# 1-Schematic_miniCoffee.net
KiCad netlist of a schematic drawn in EasyEDA
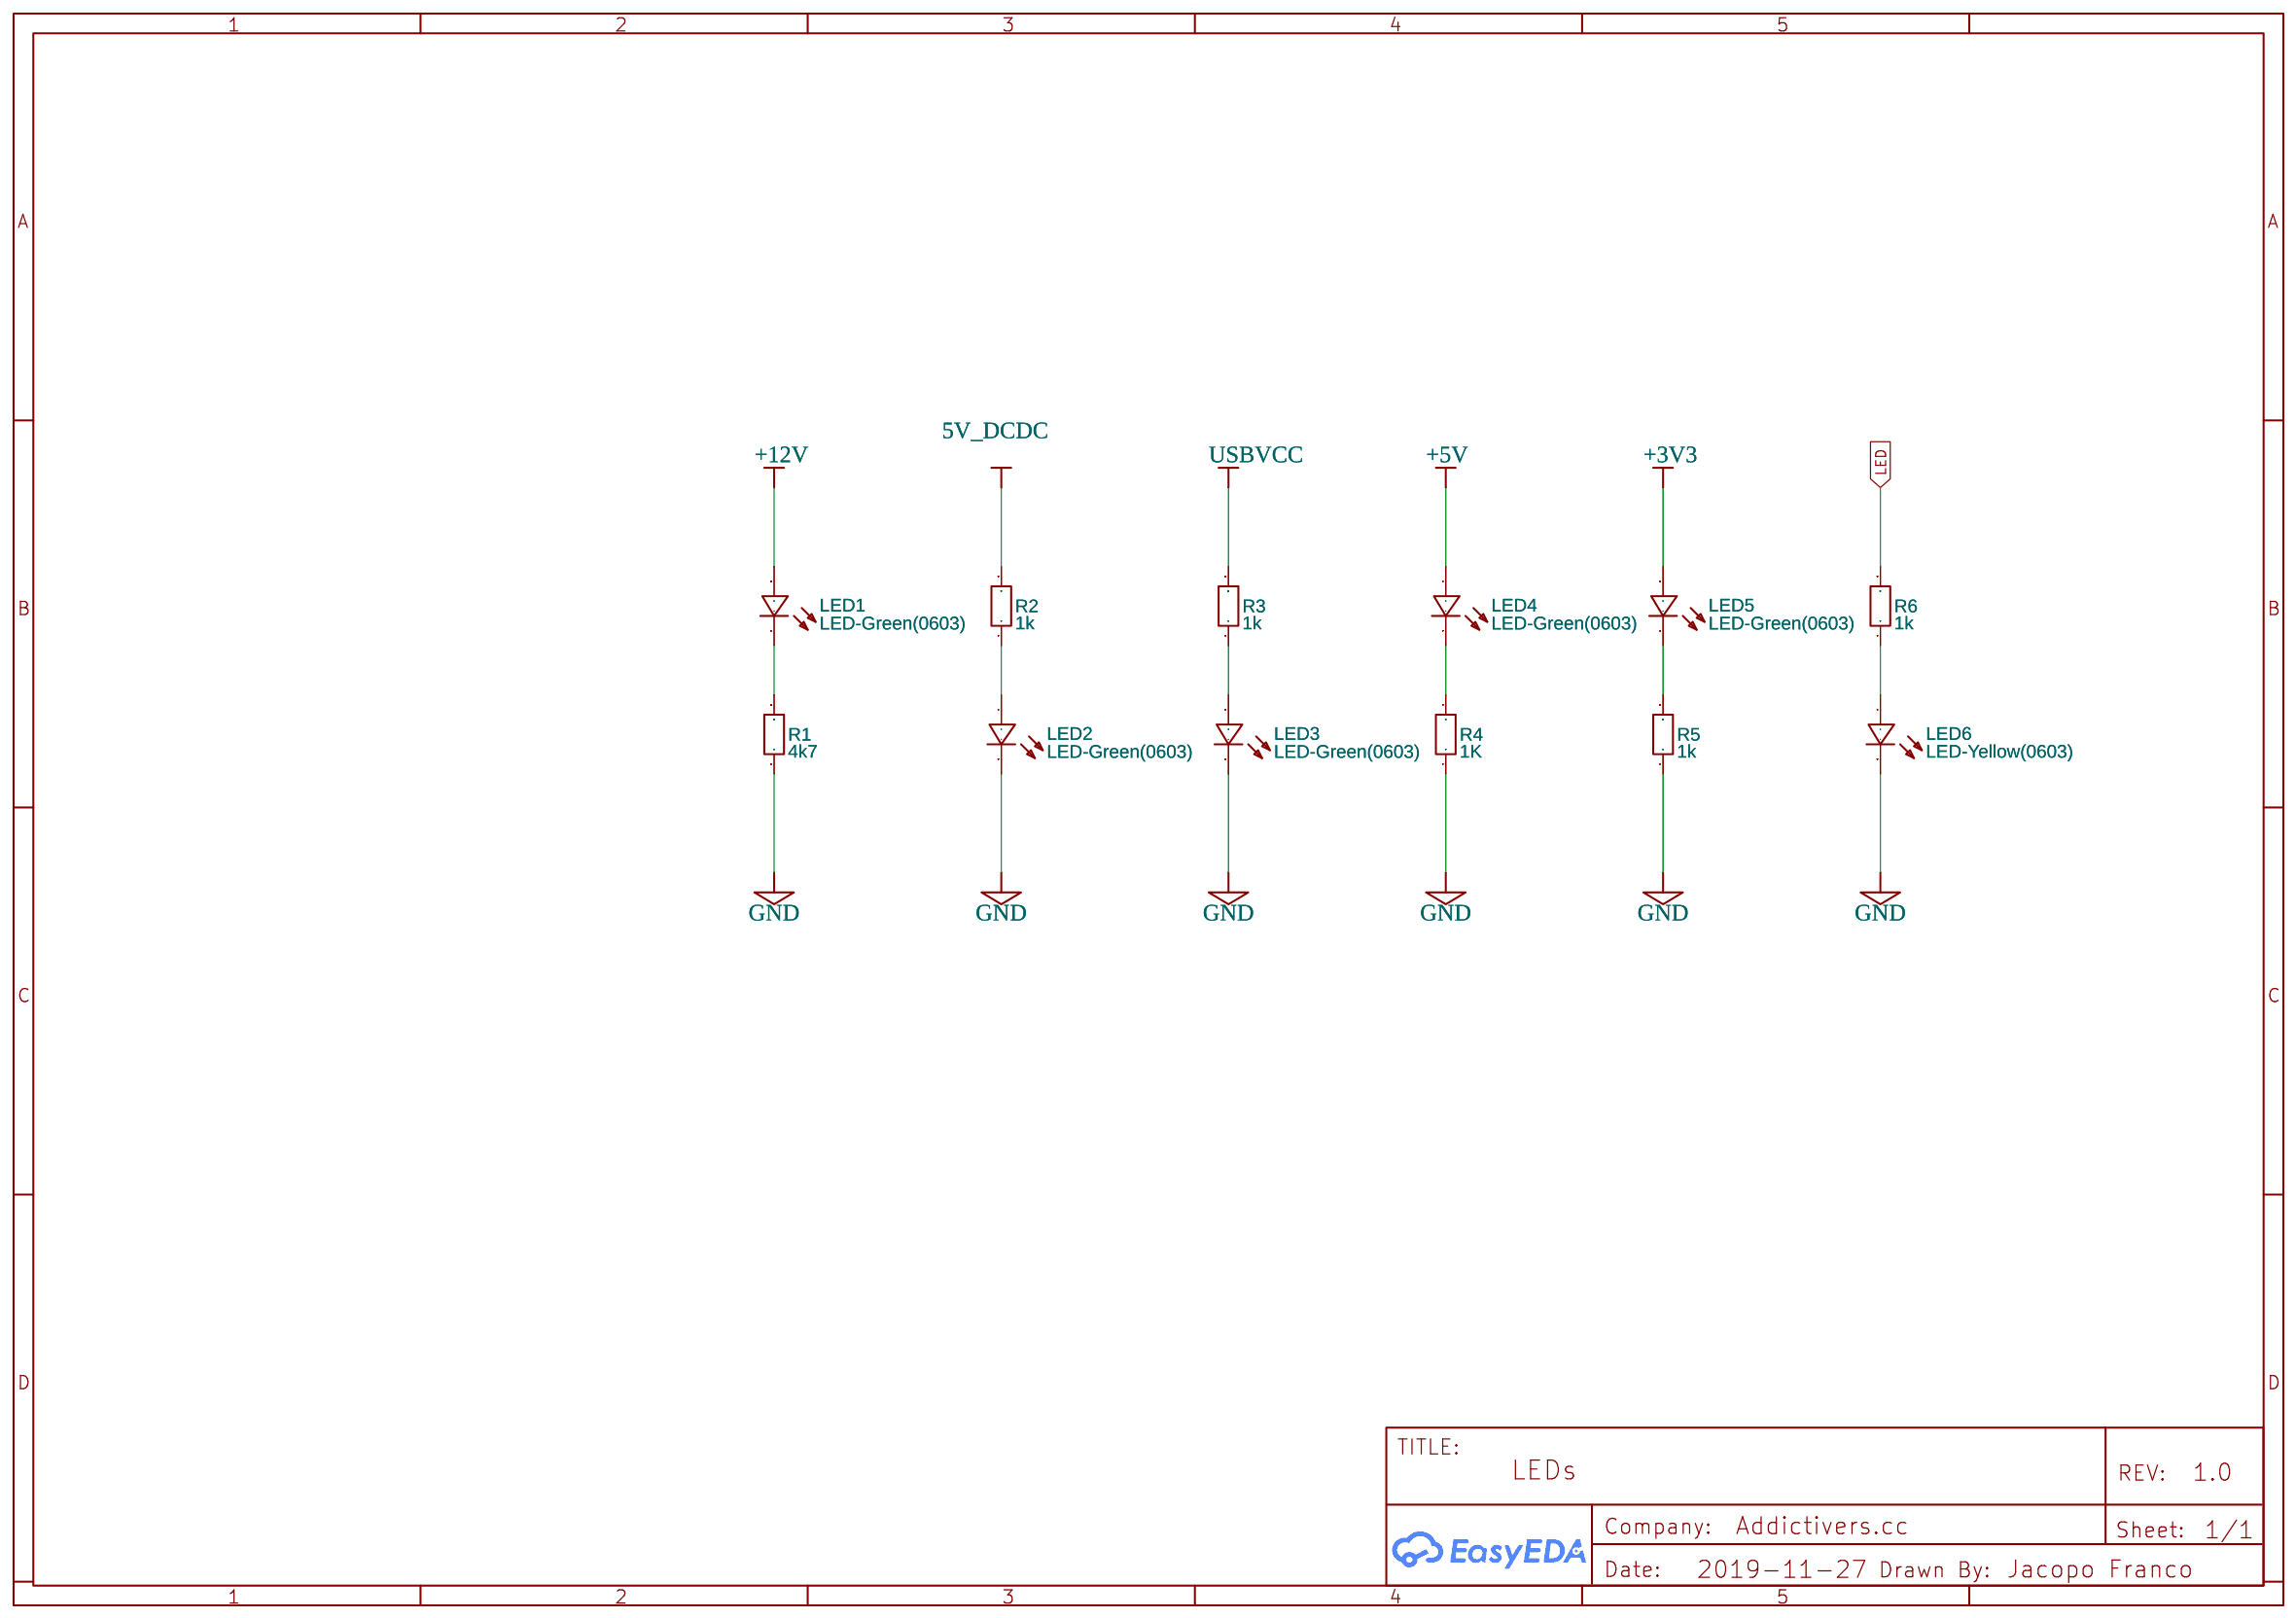
[diagram p0: LEDs]
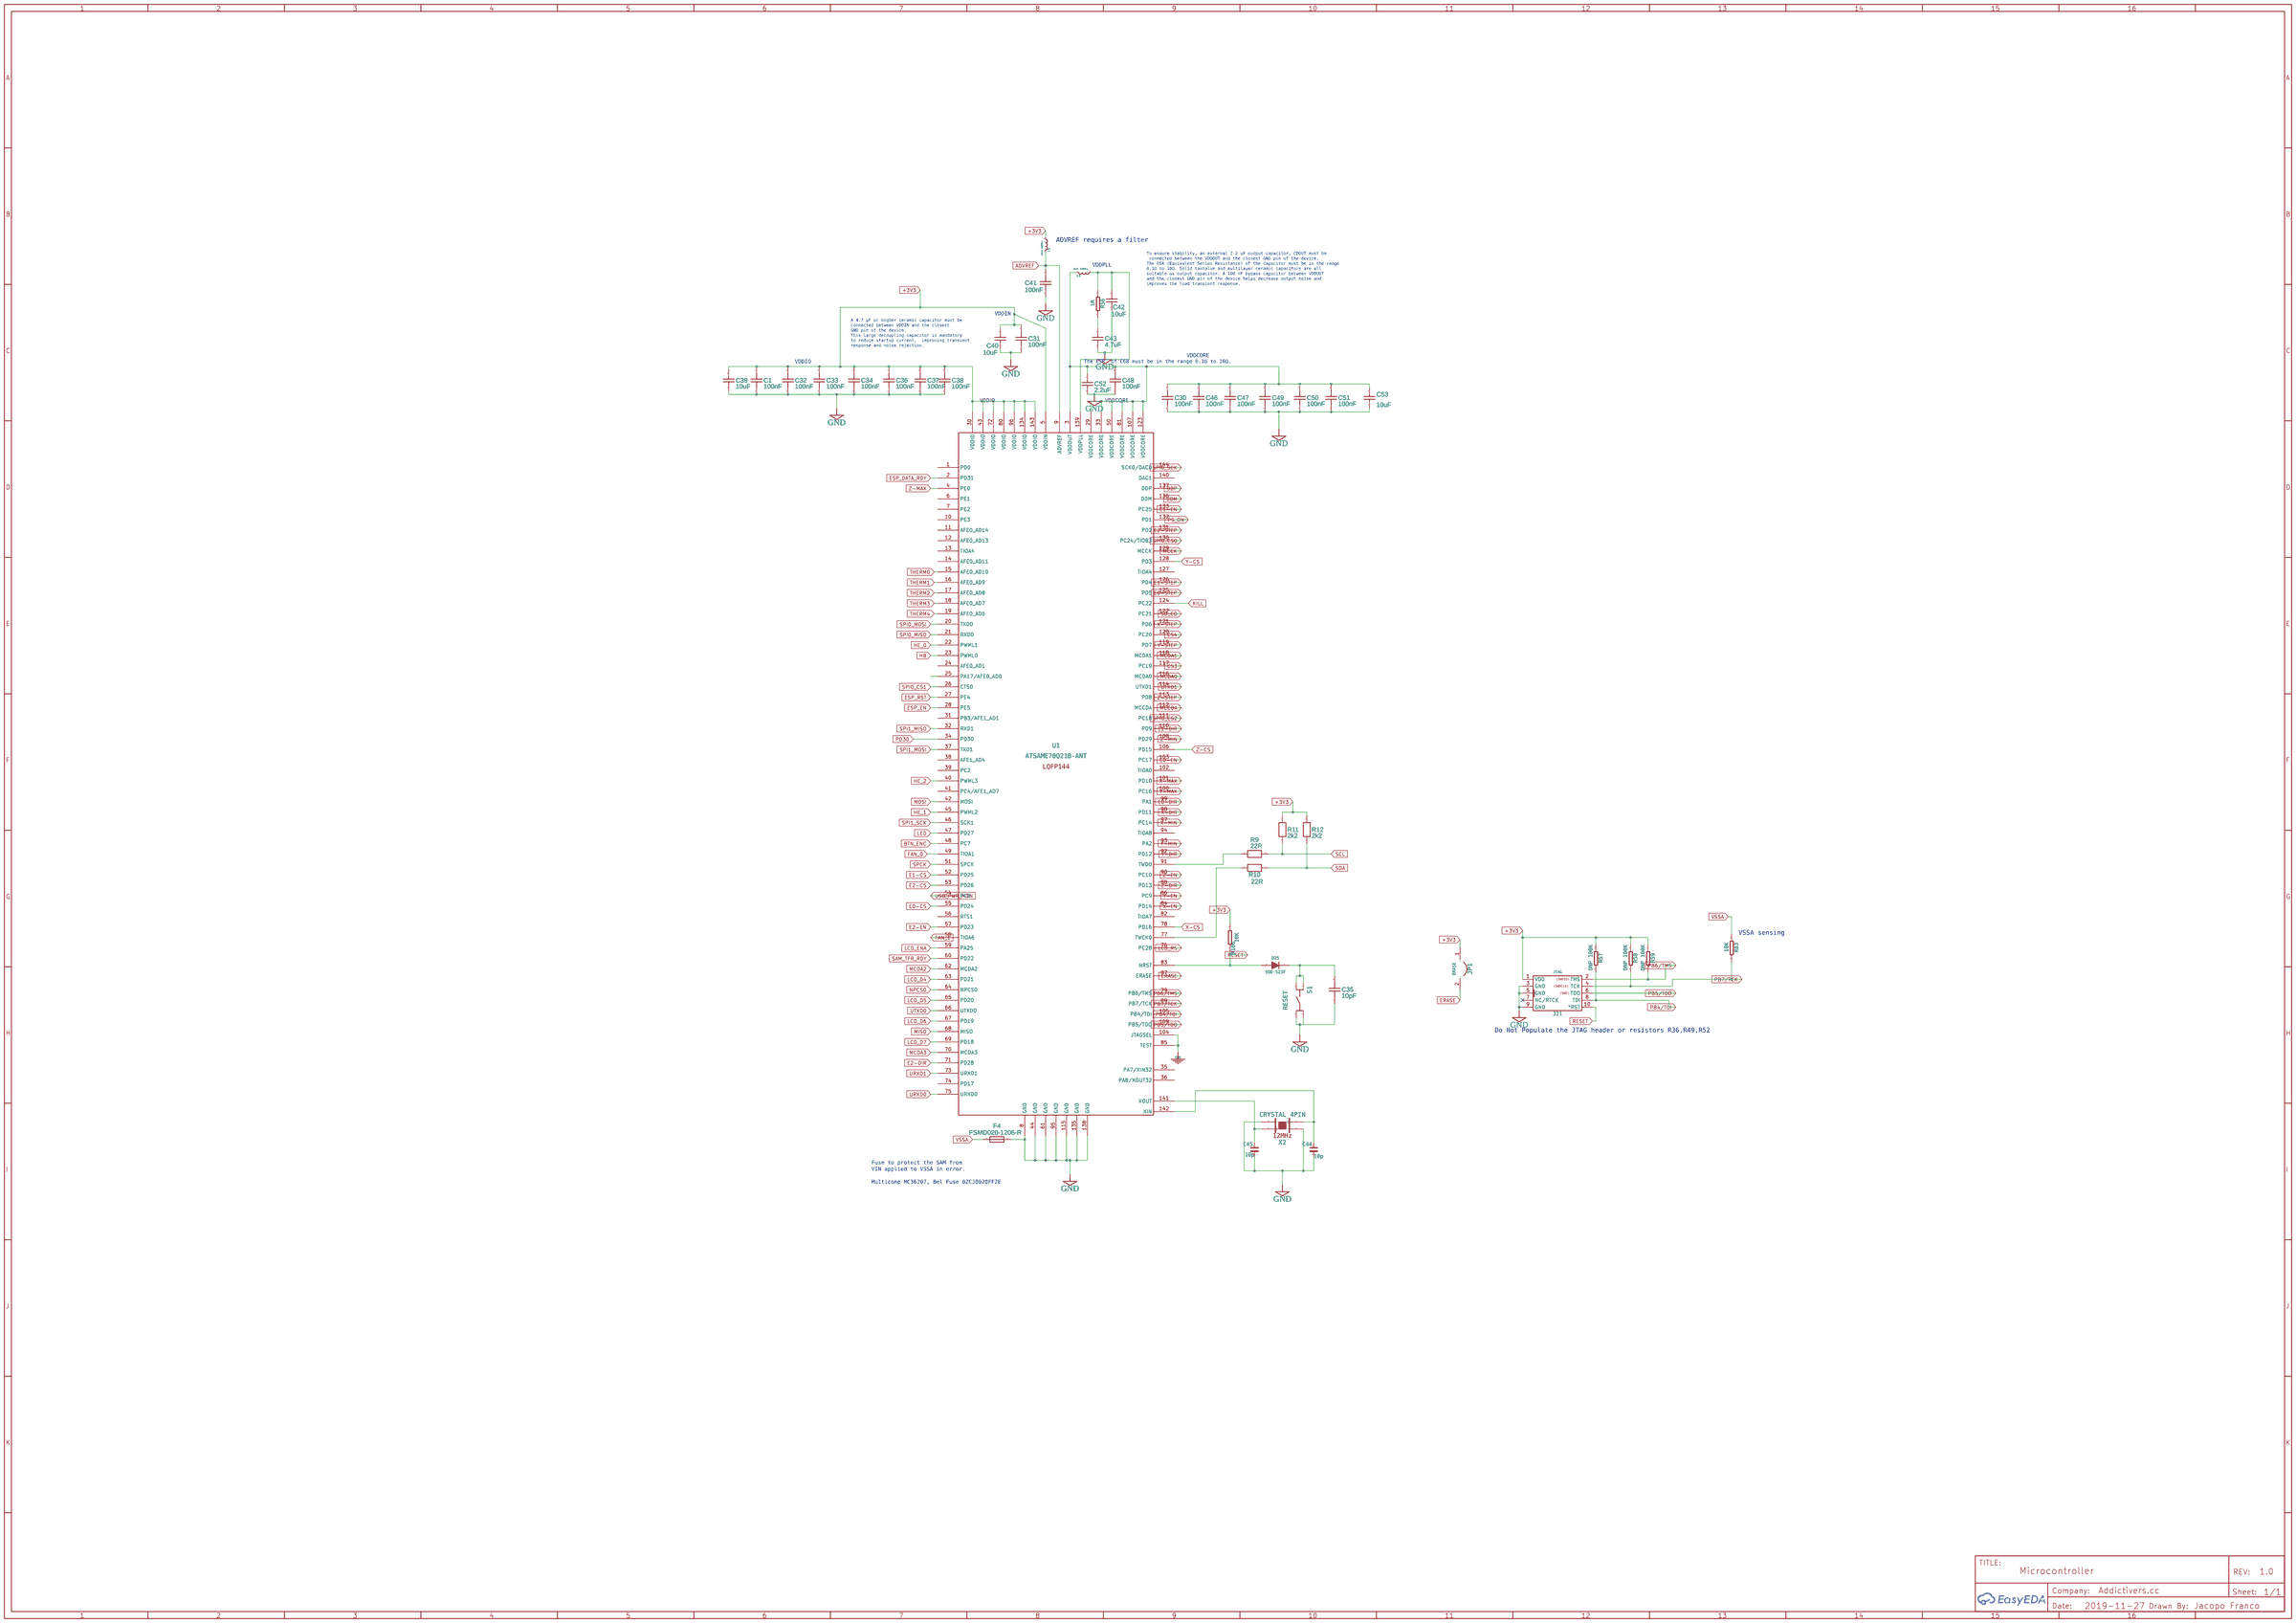
[diagram p1: Microcontroller]
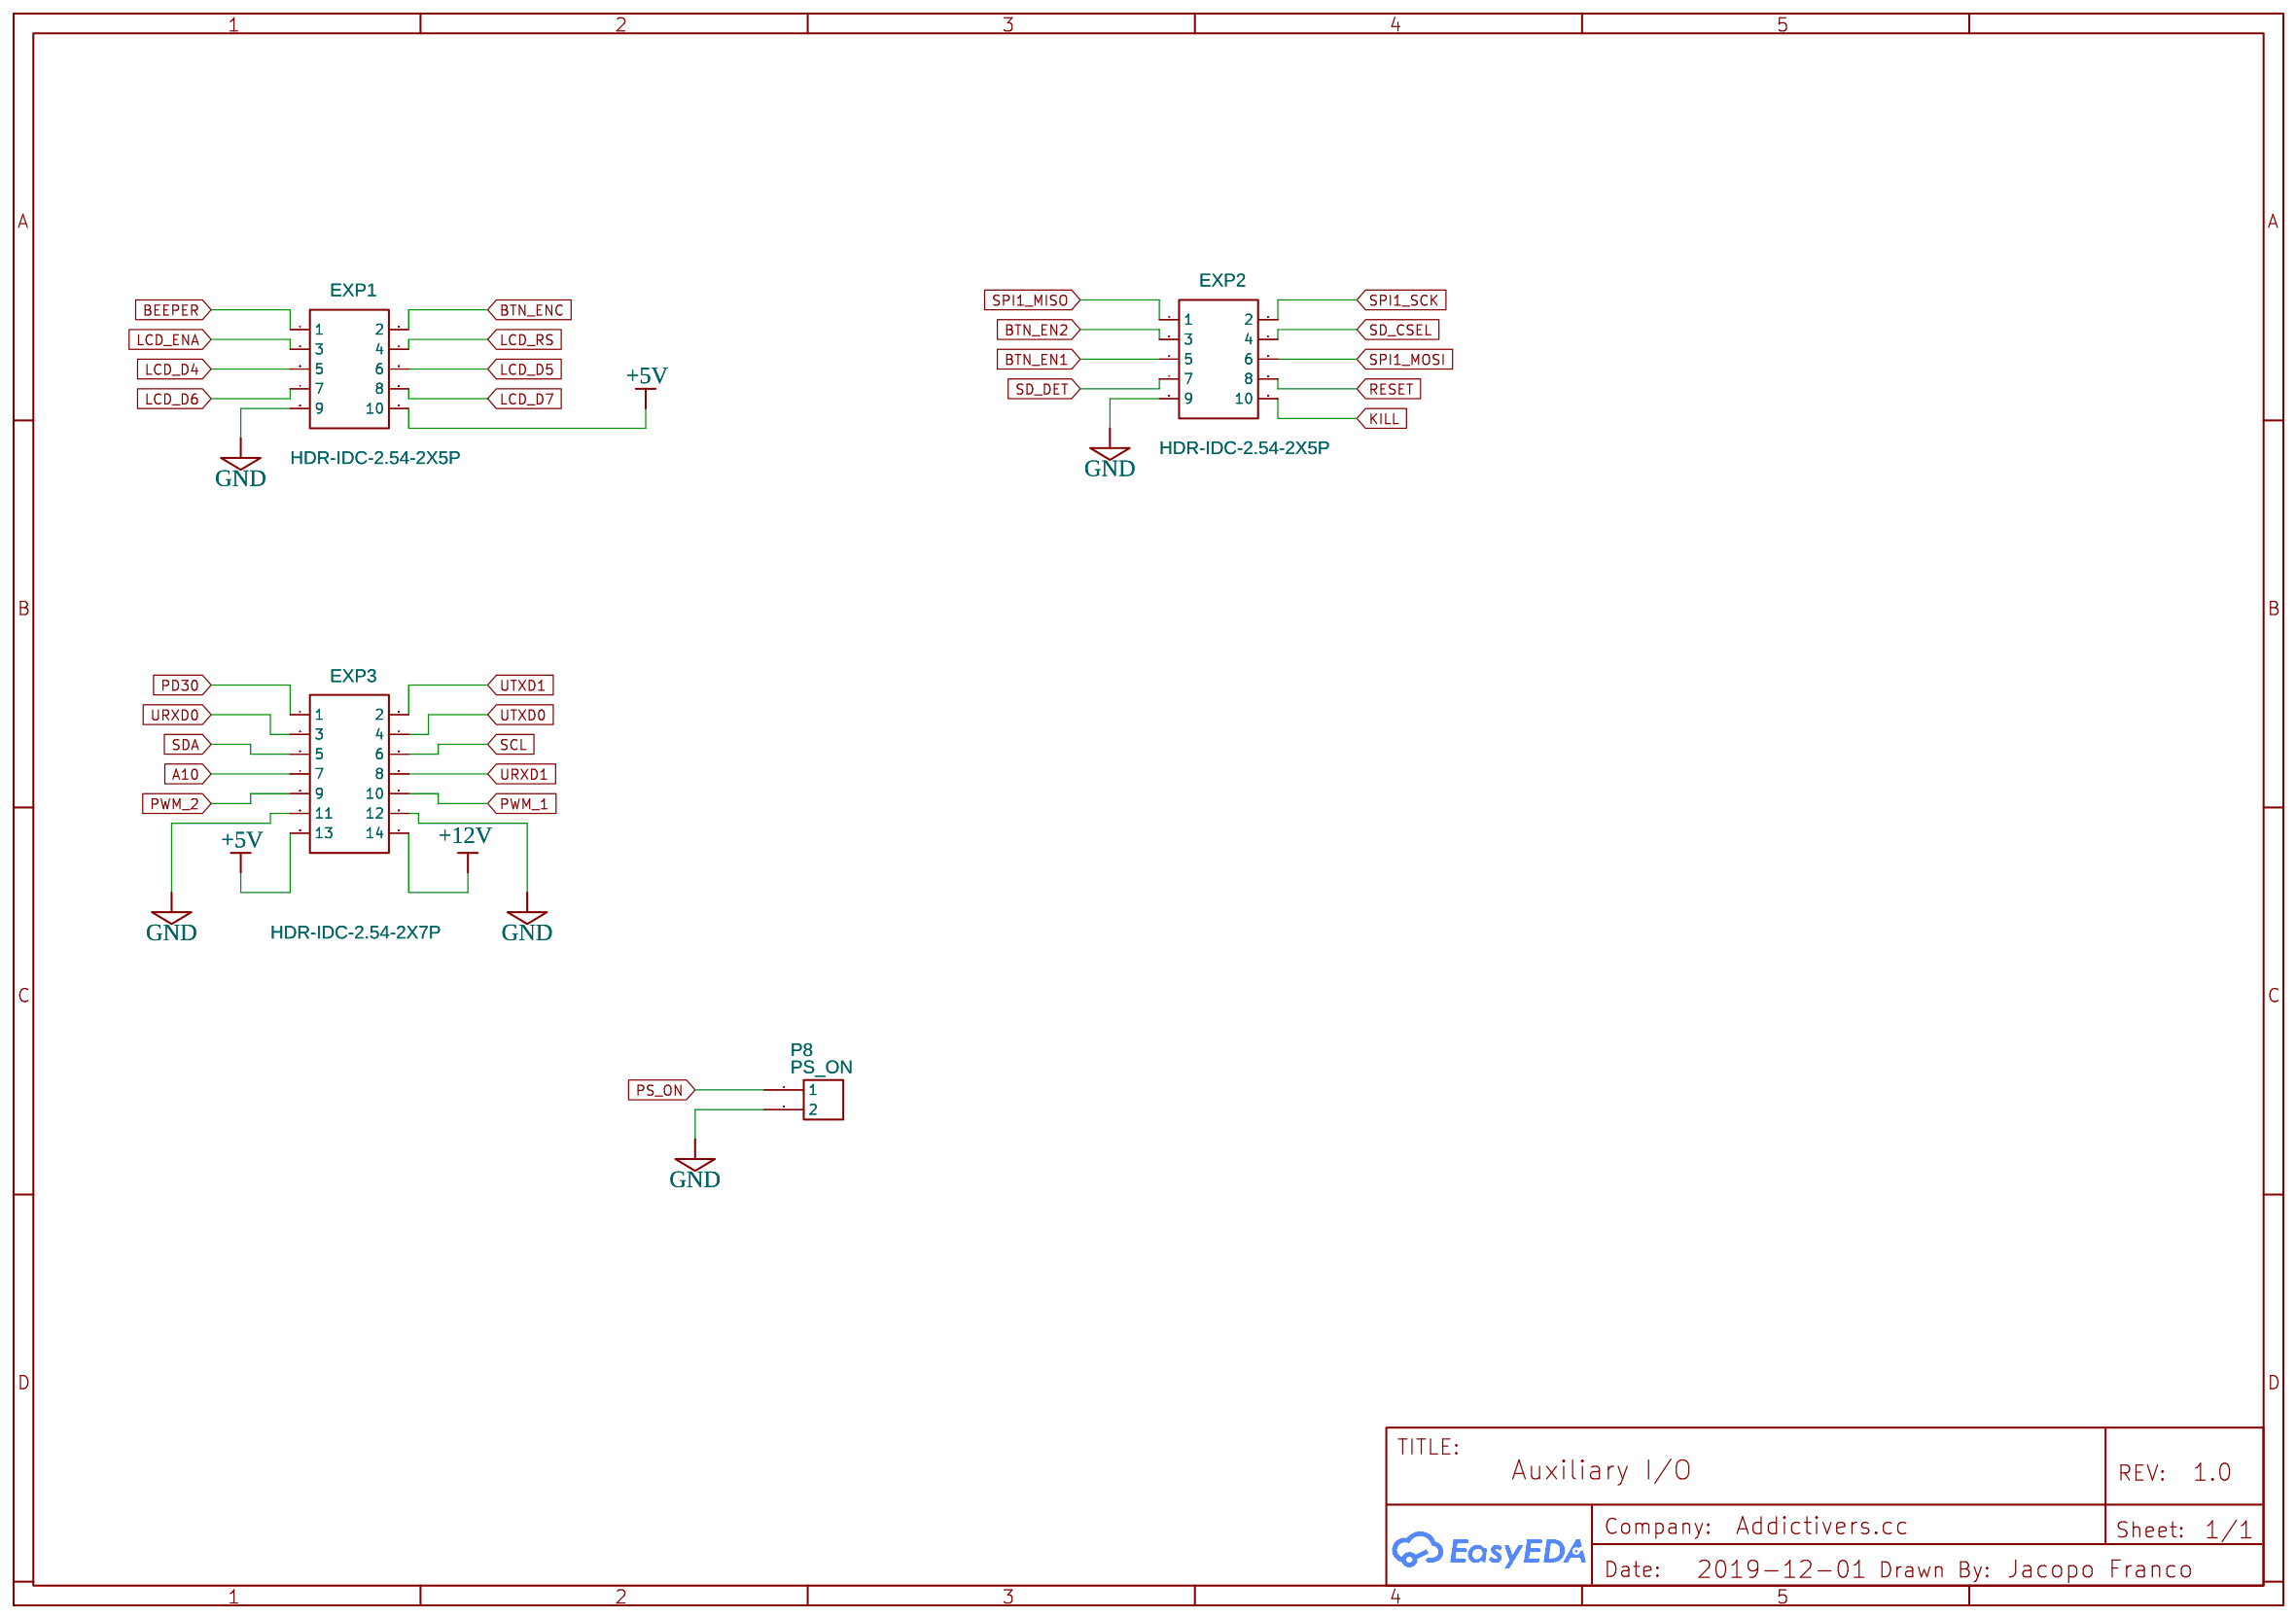
[diagram p2: Auxiliary IO]
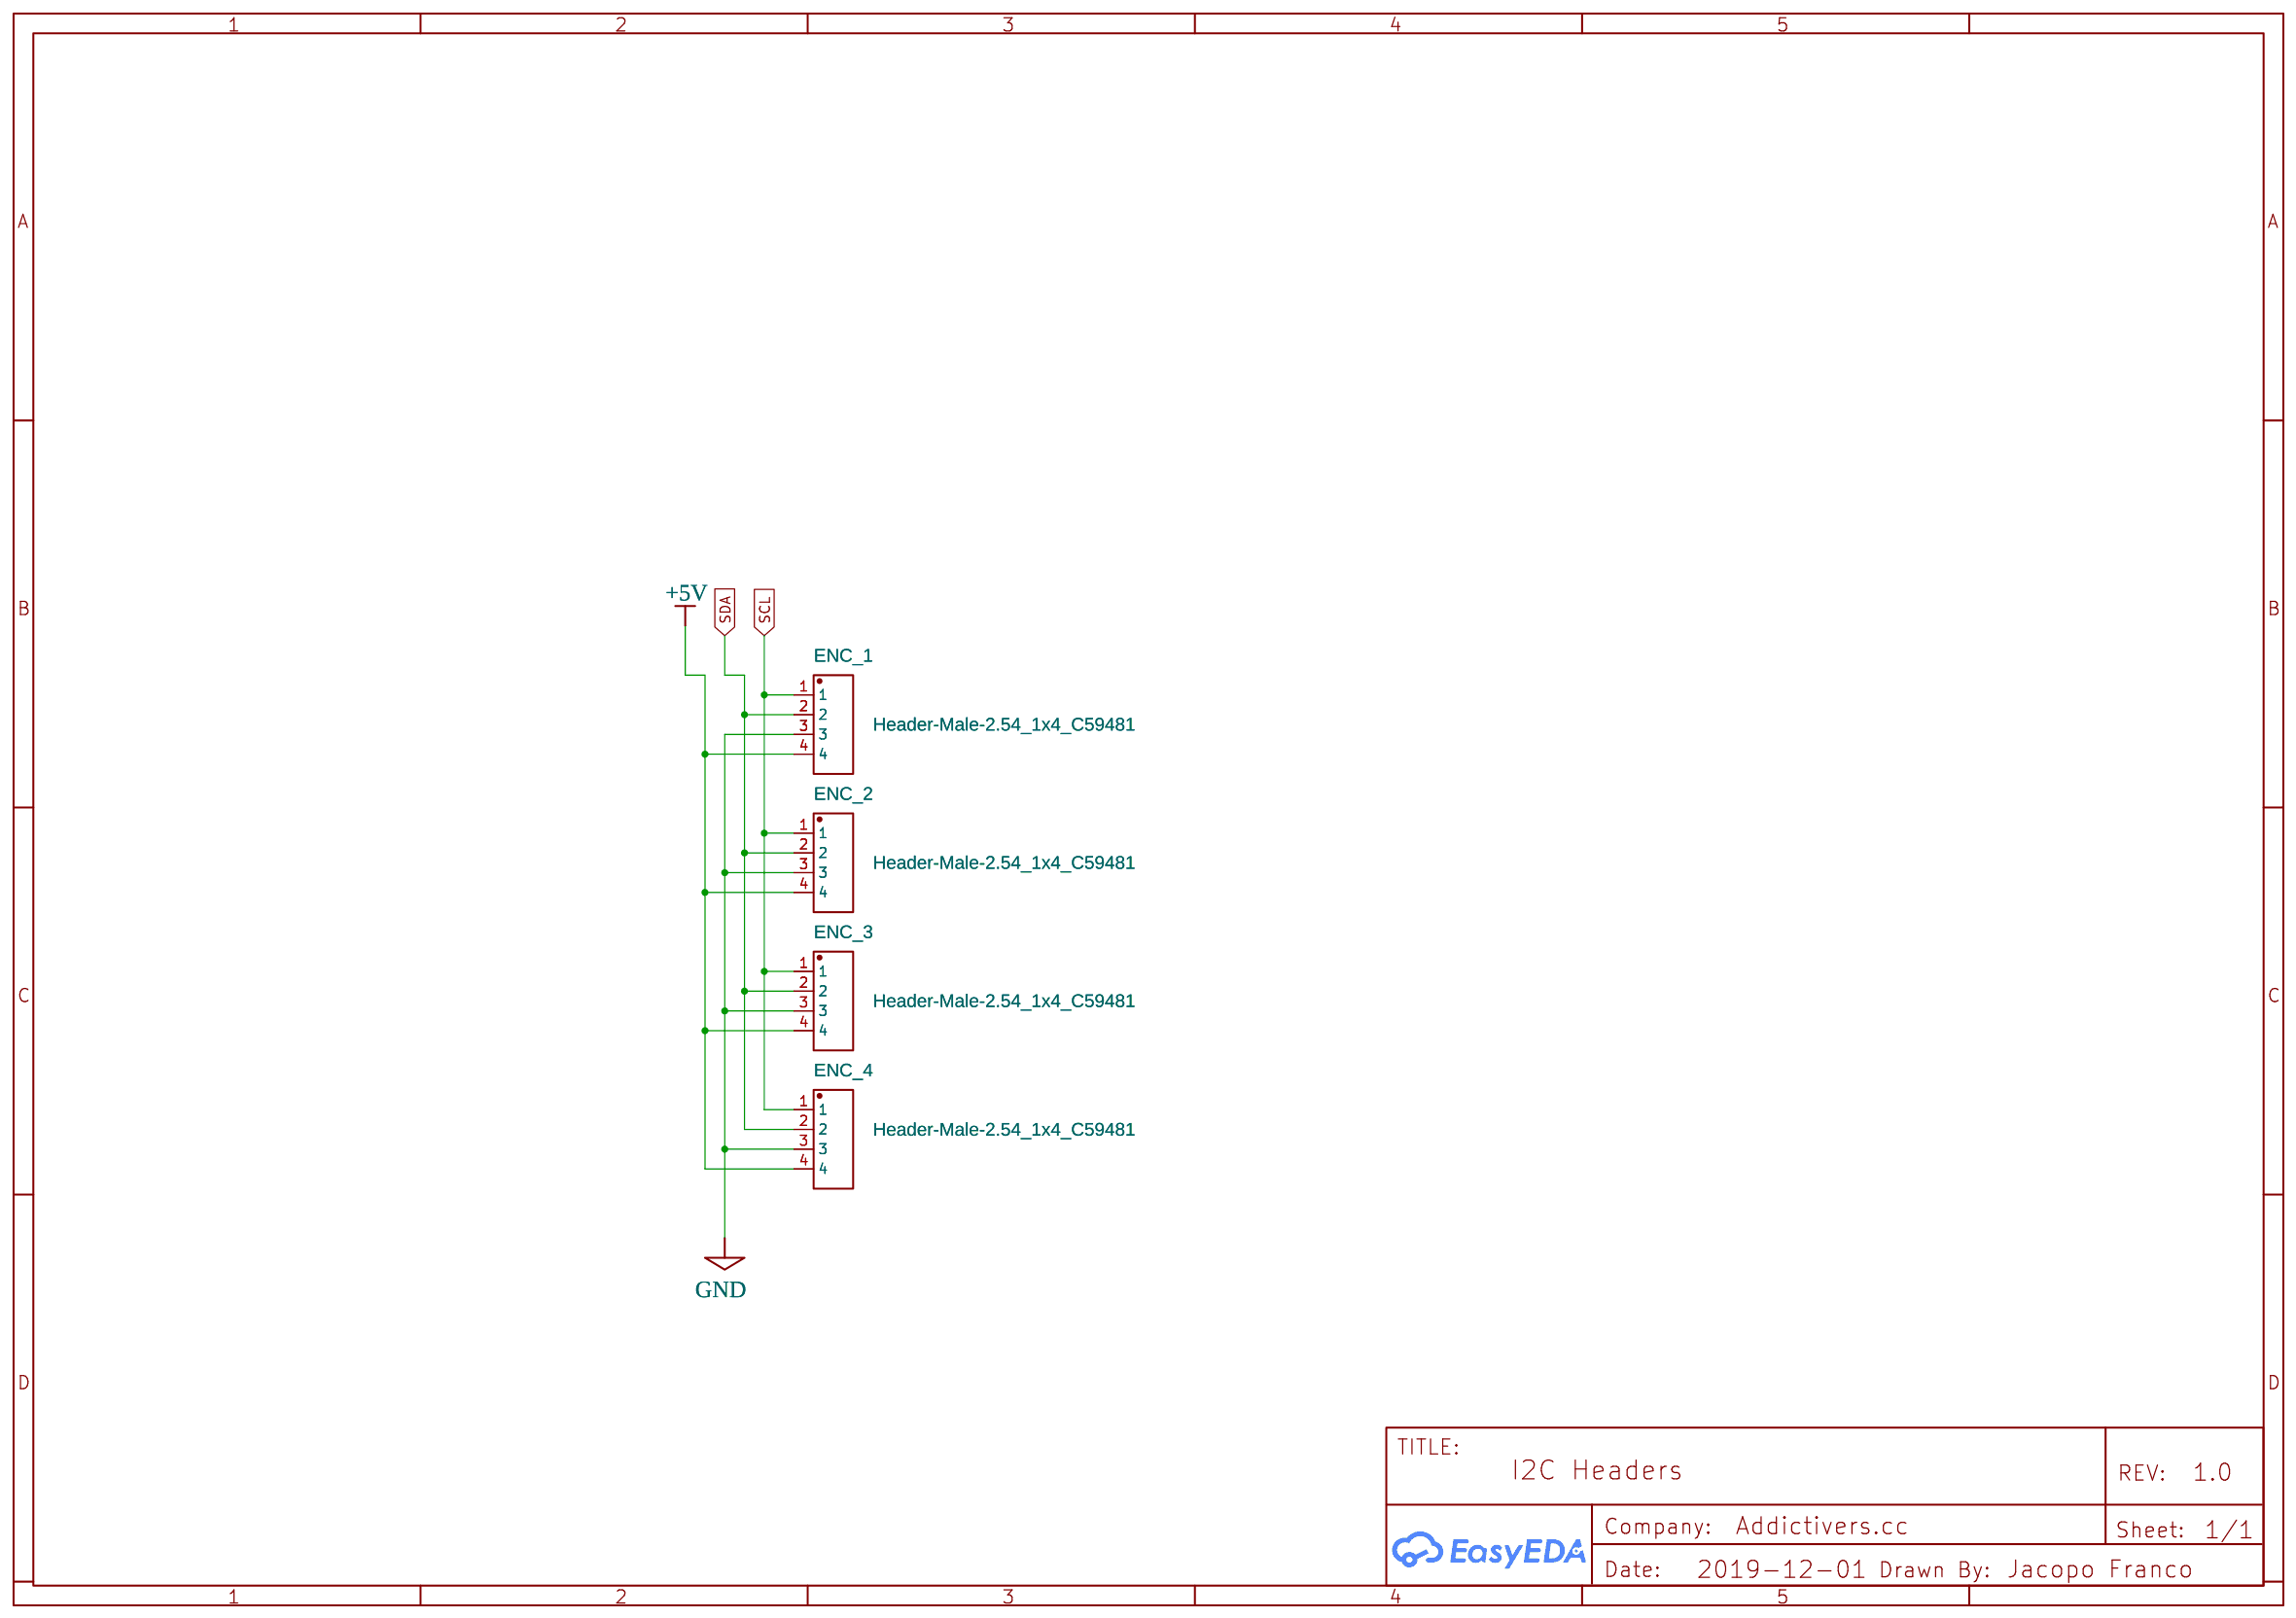
[diagram p3: I2C Headers]
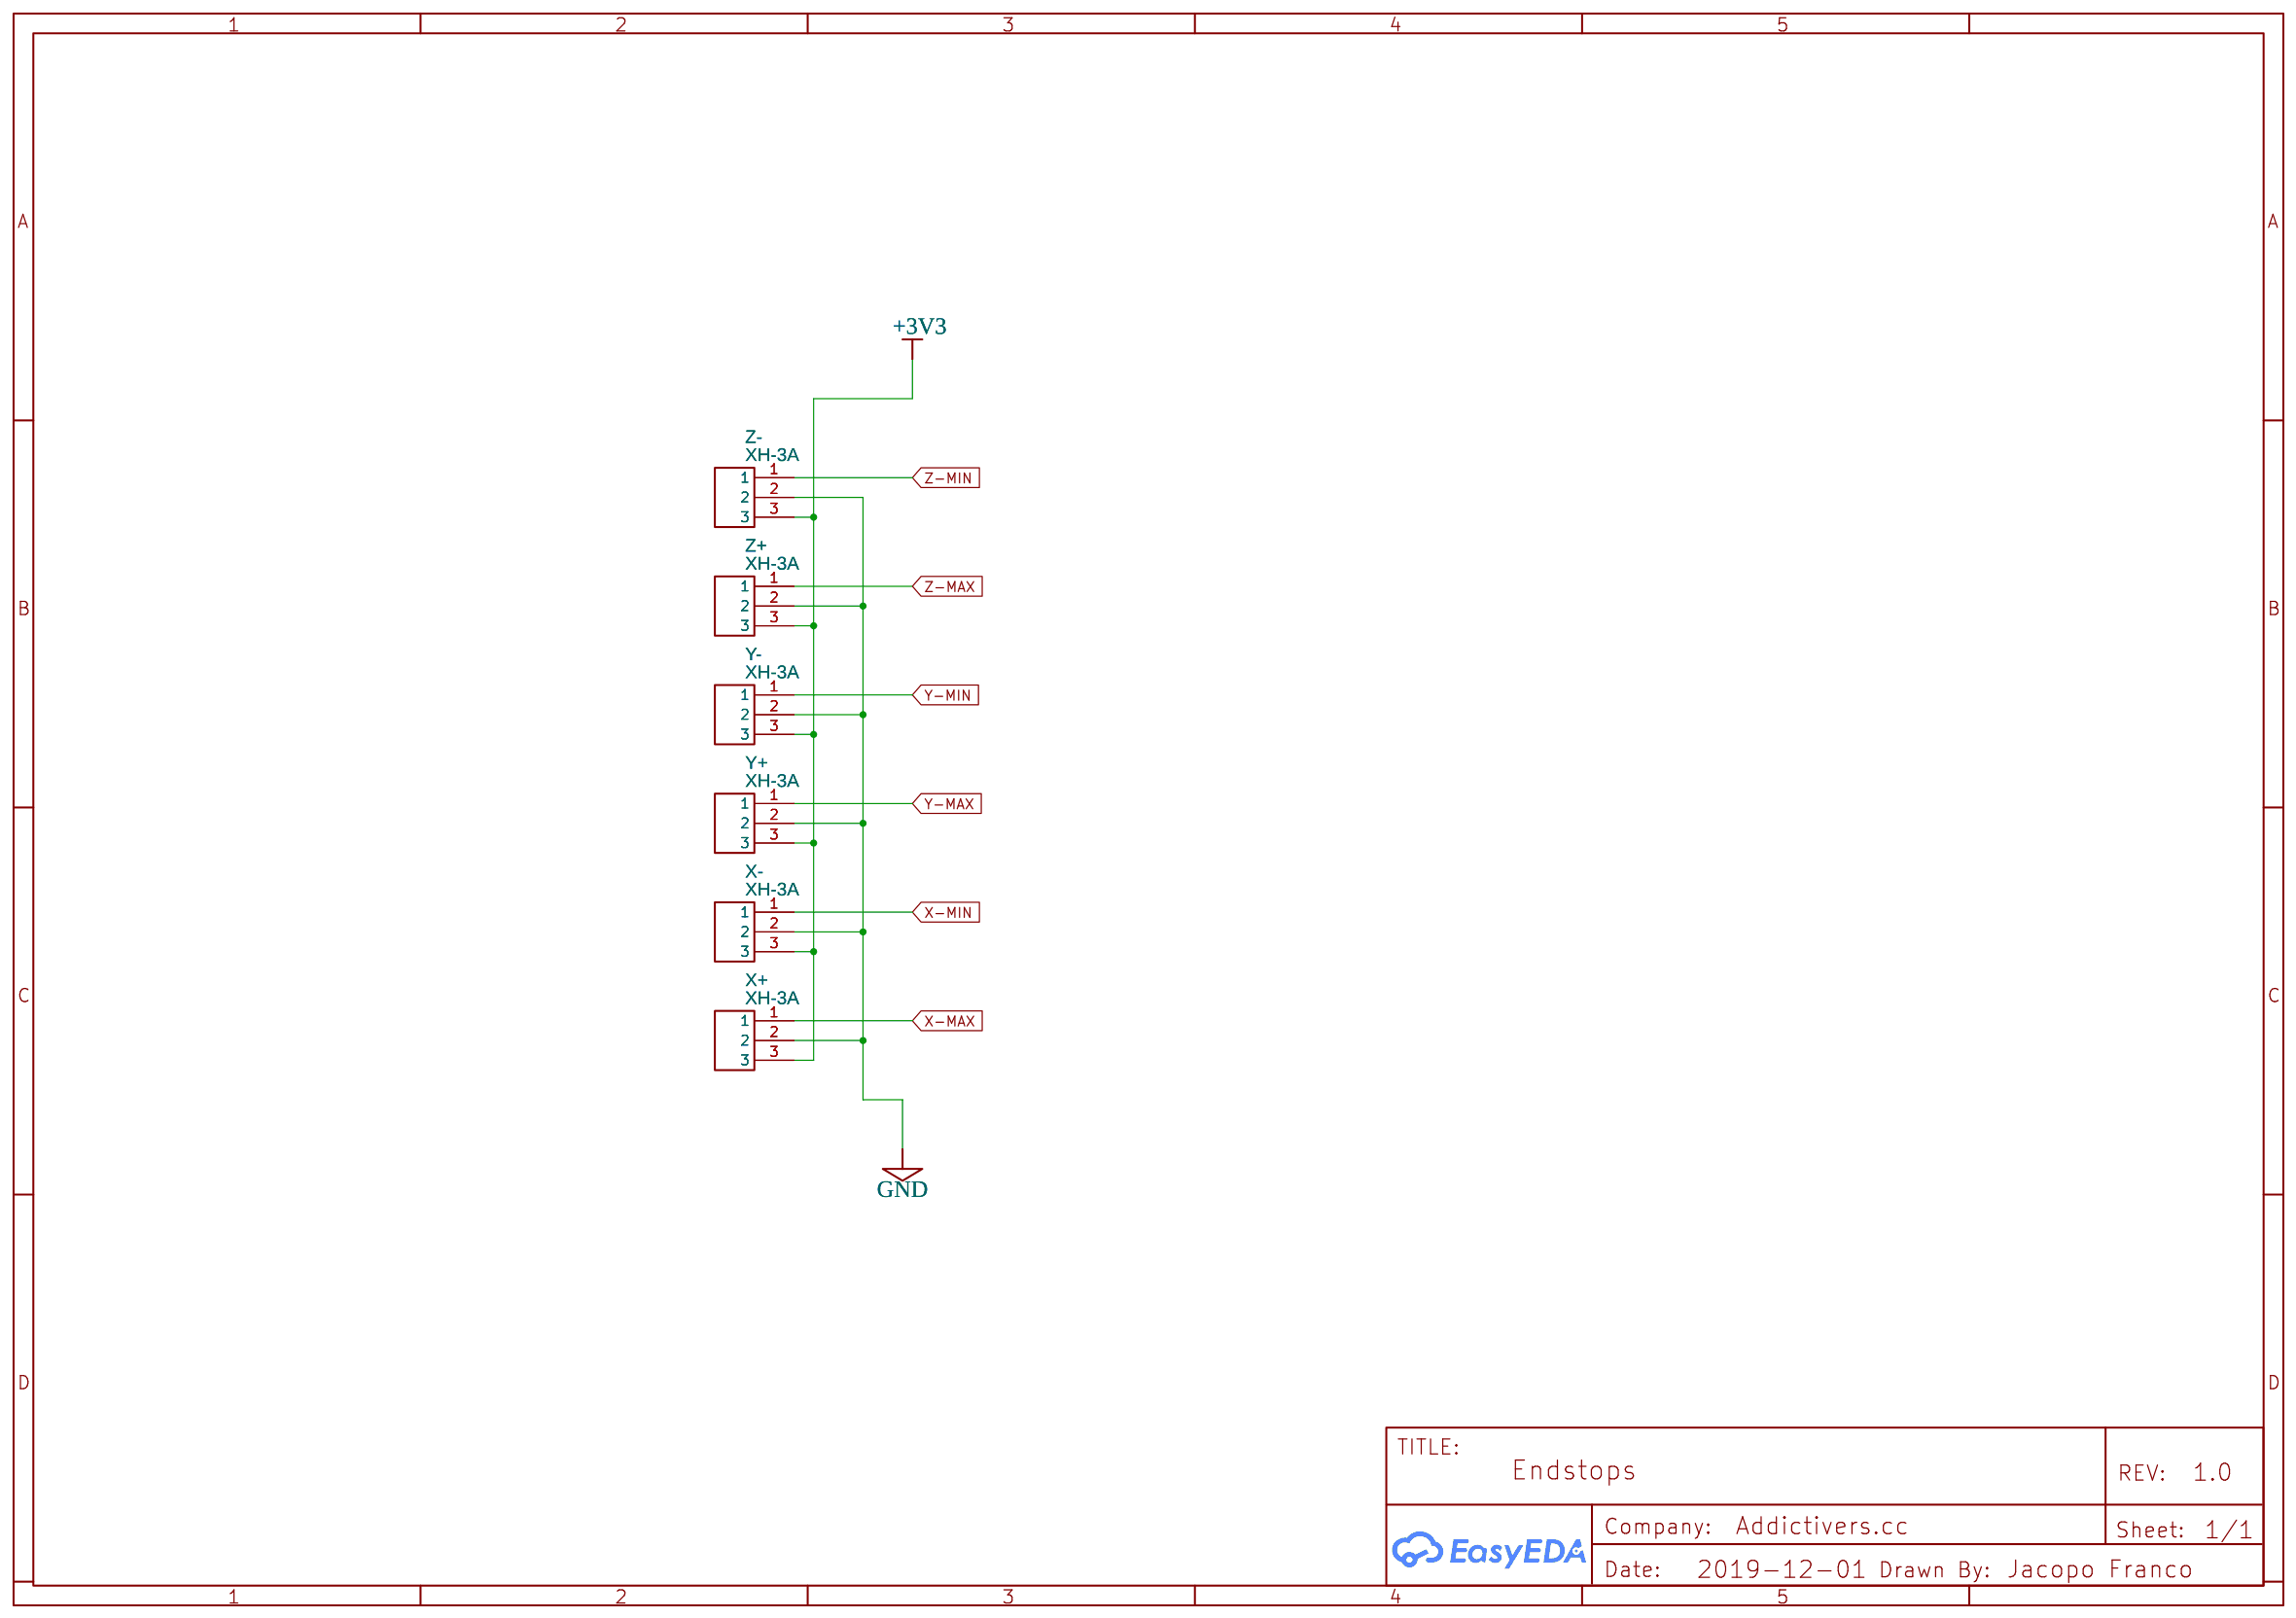
[diagram p4: Endstops]
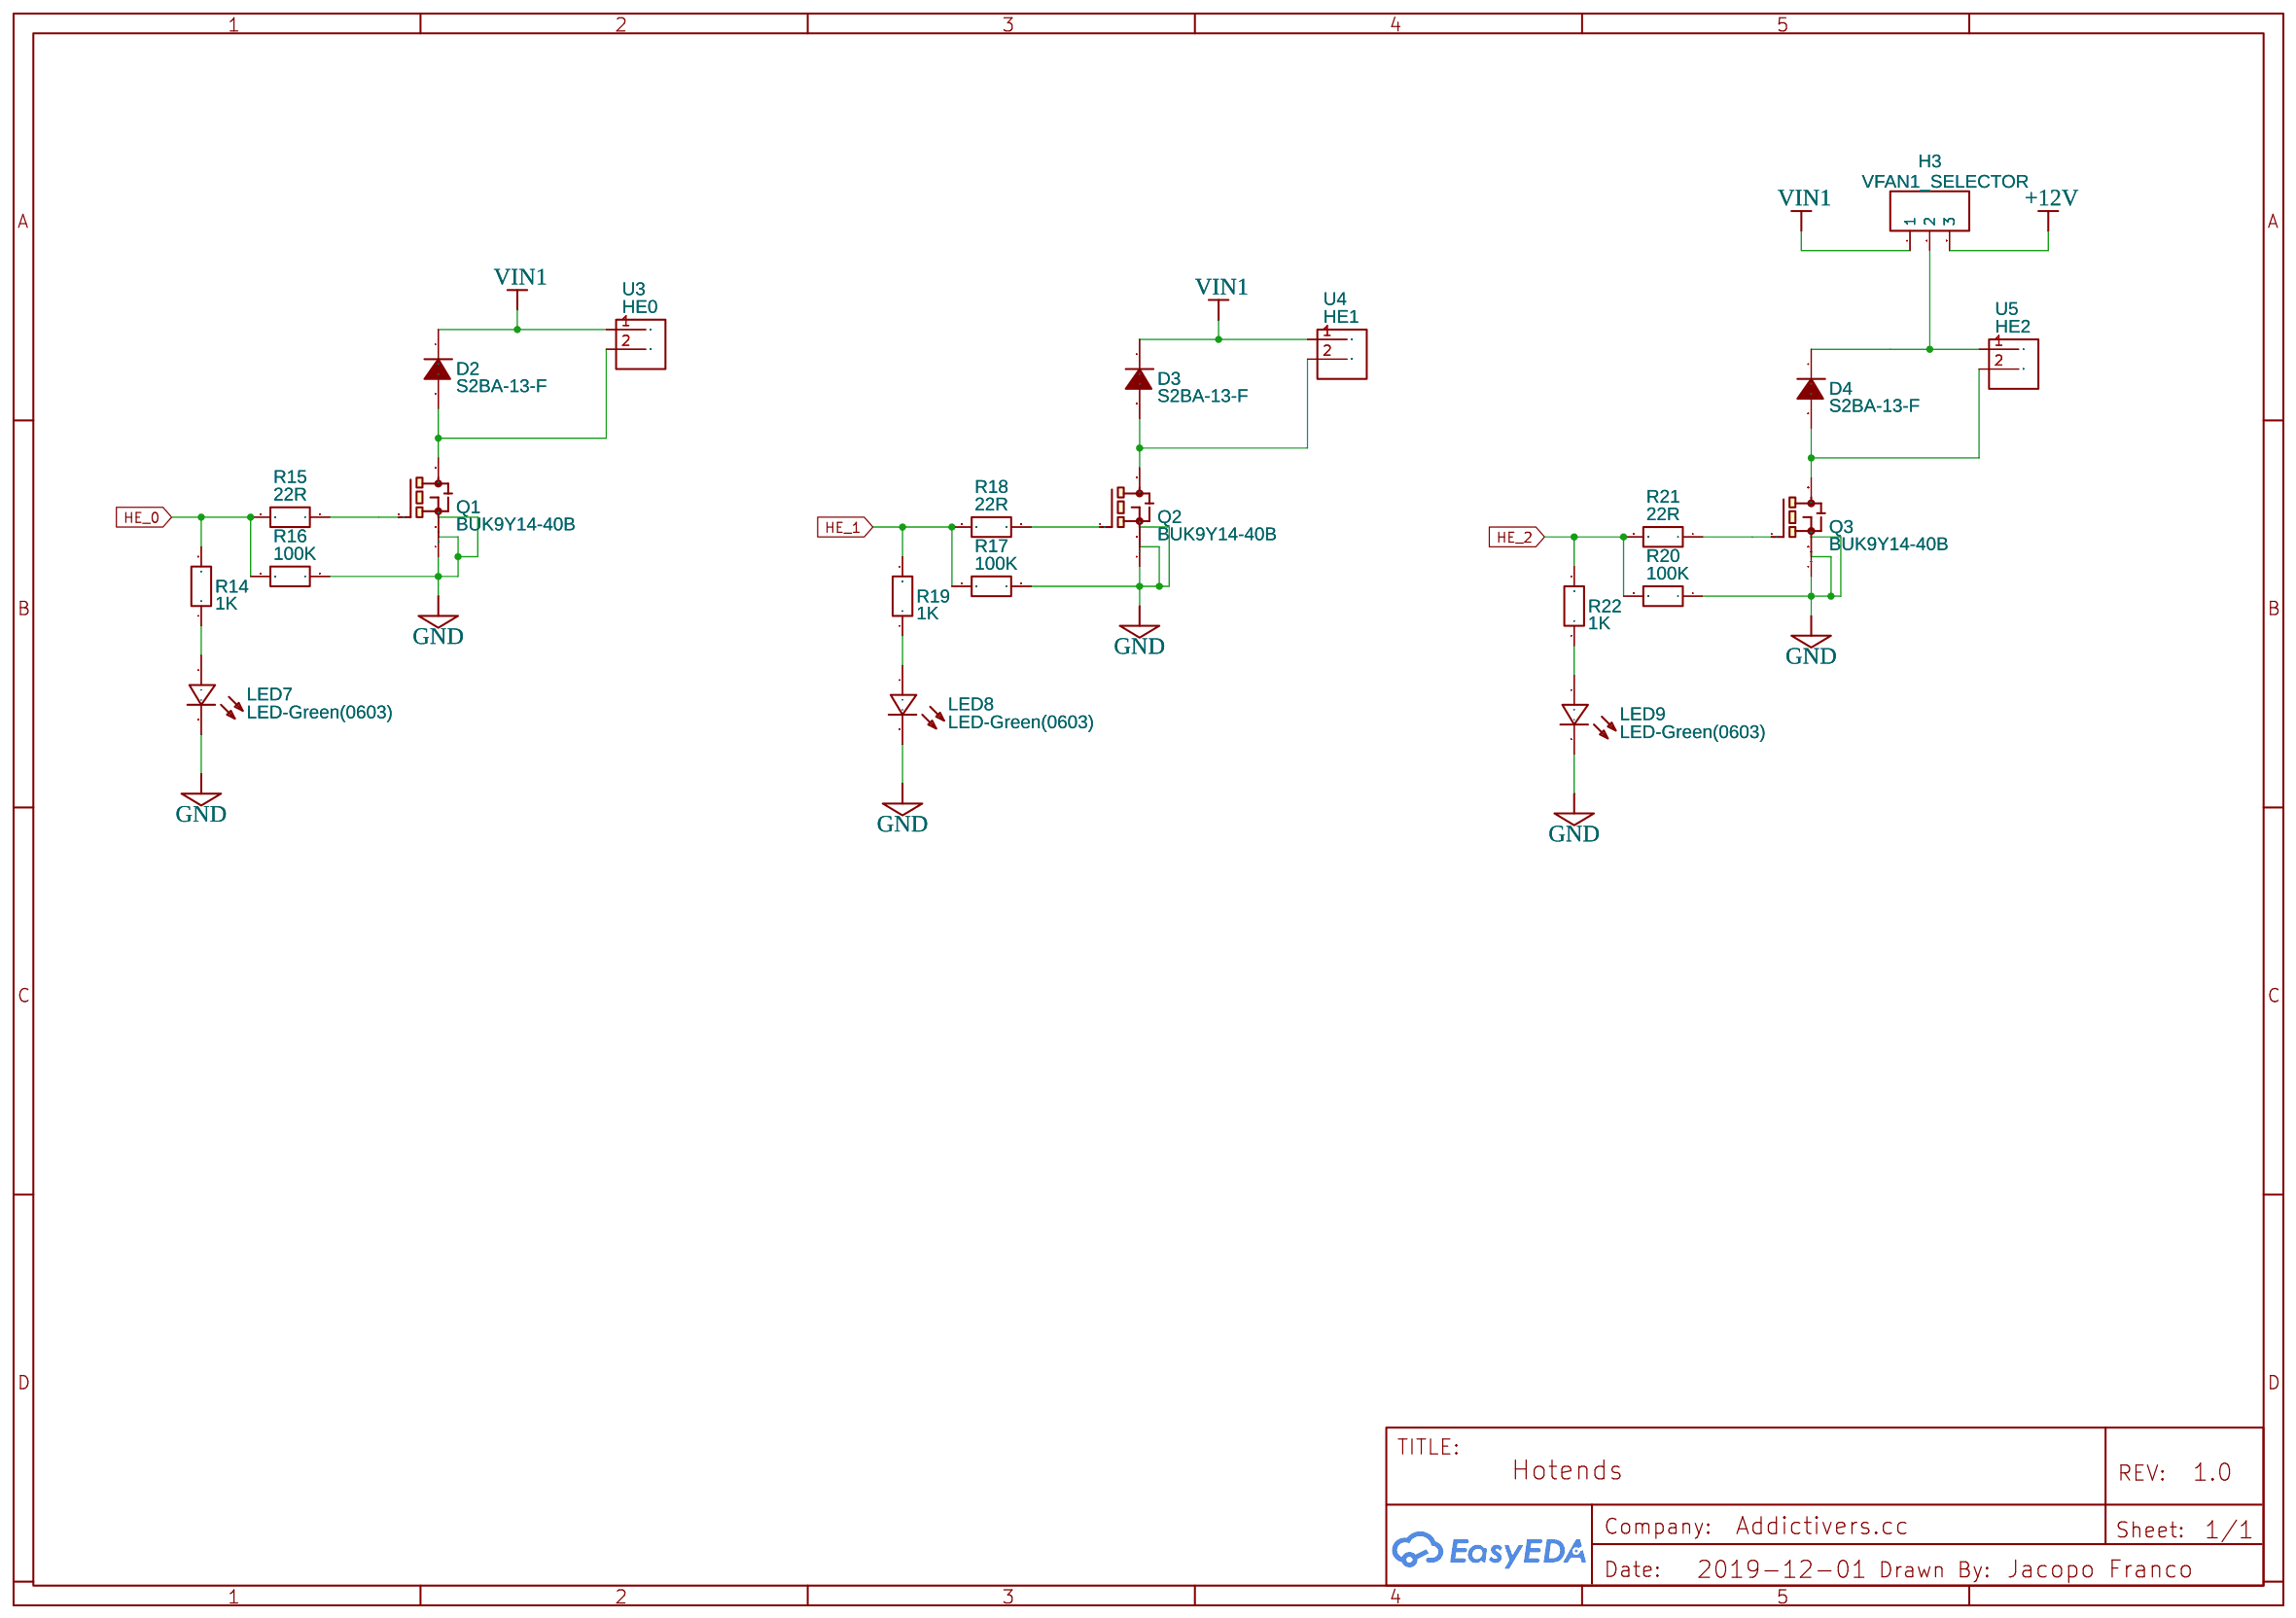
[diagram p5: Hotends]
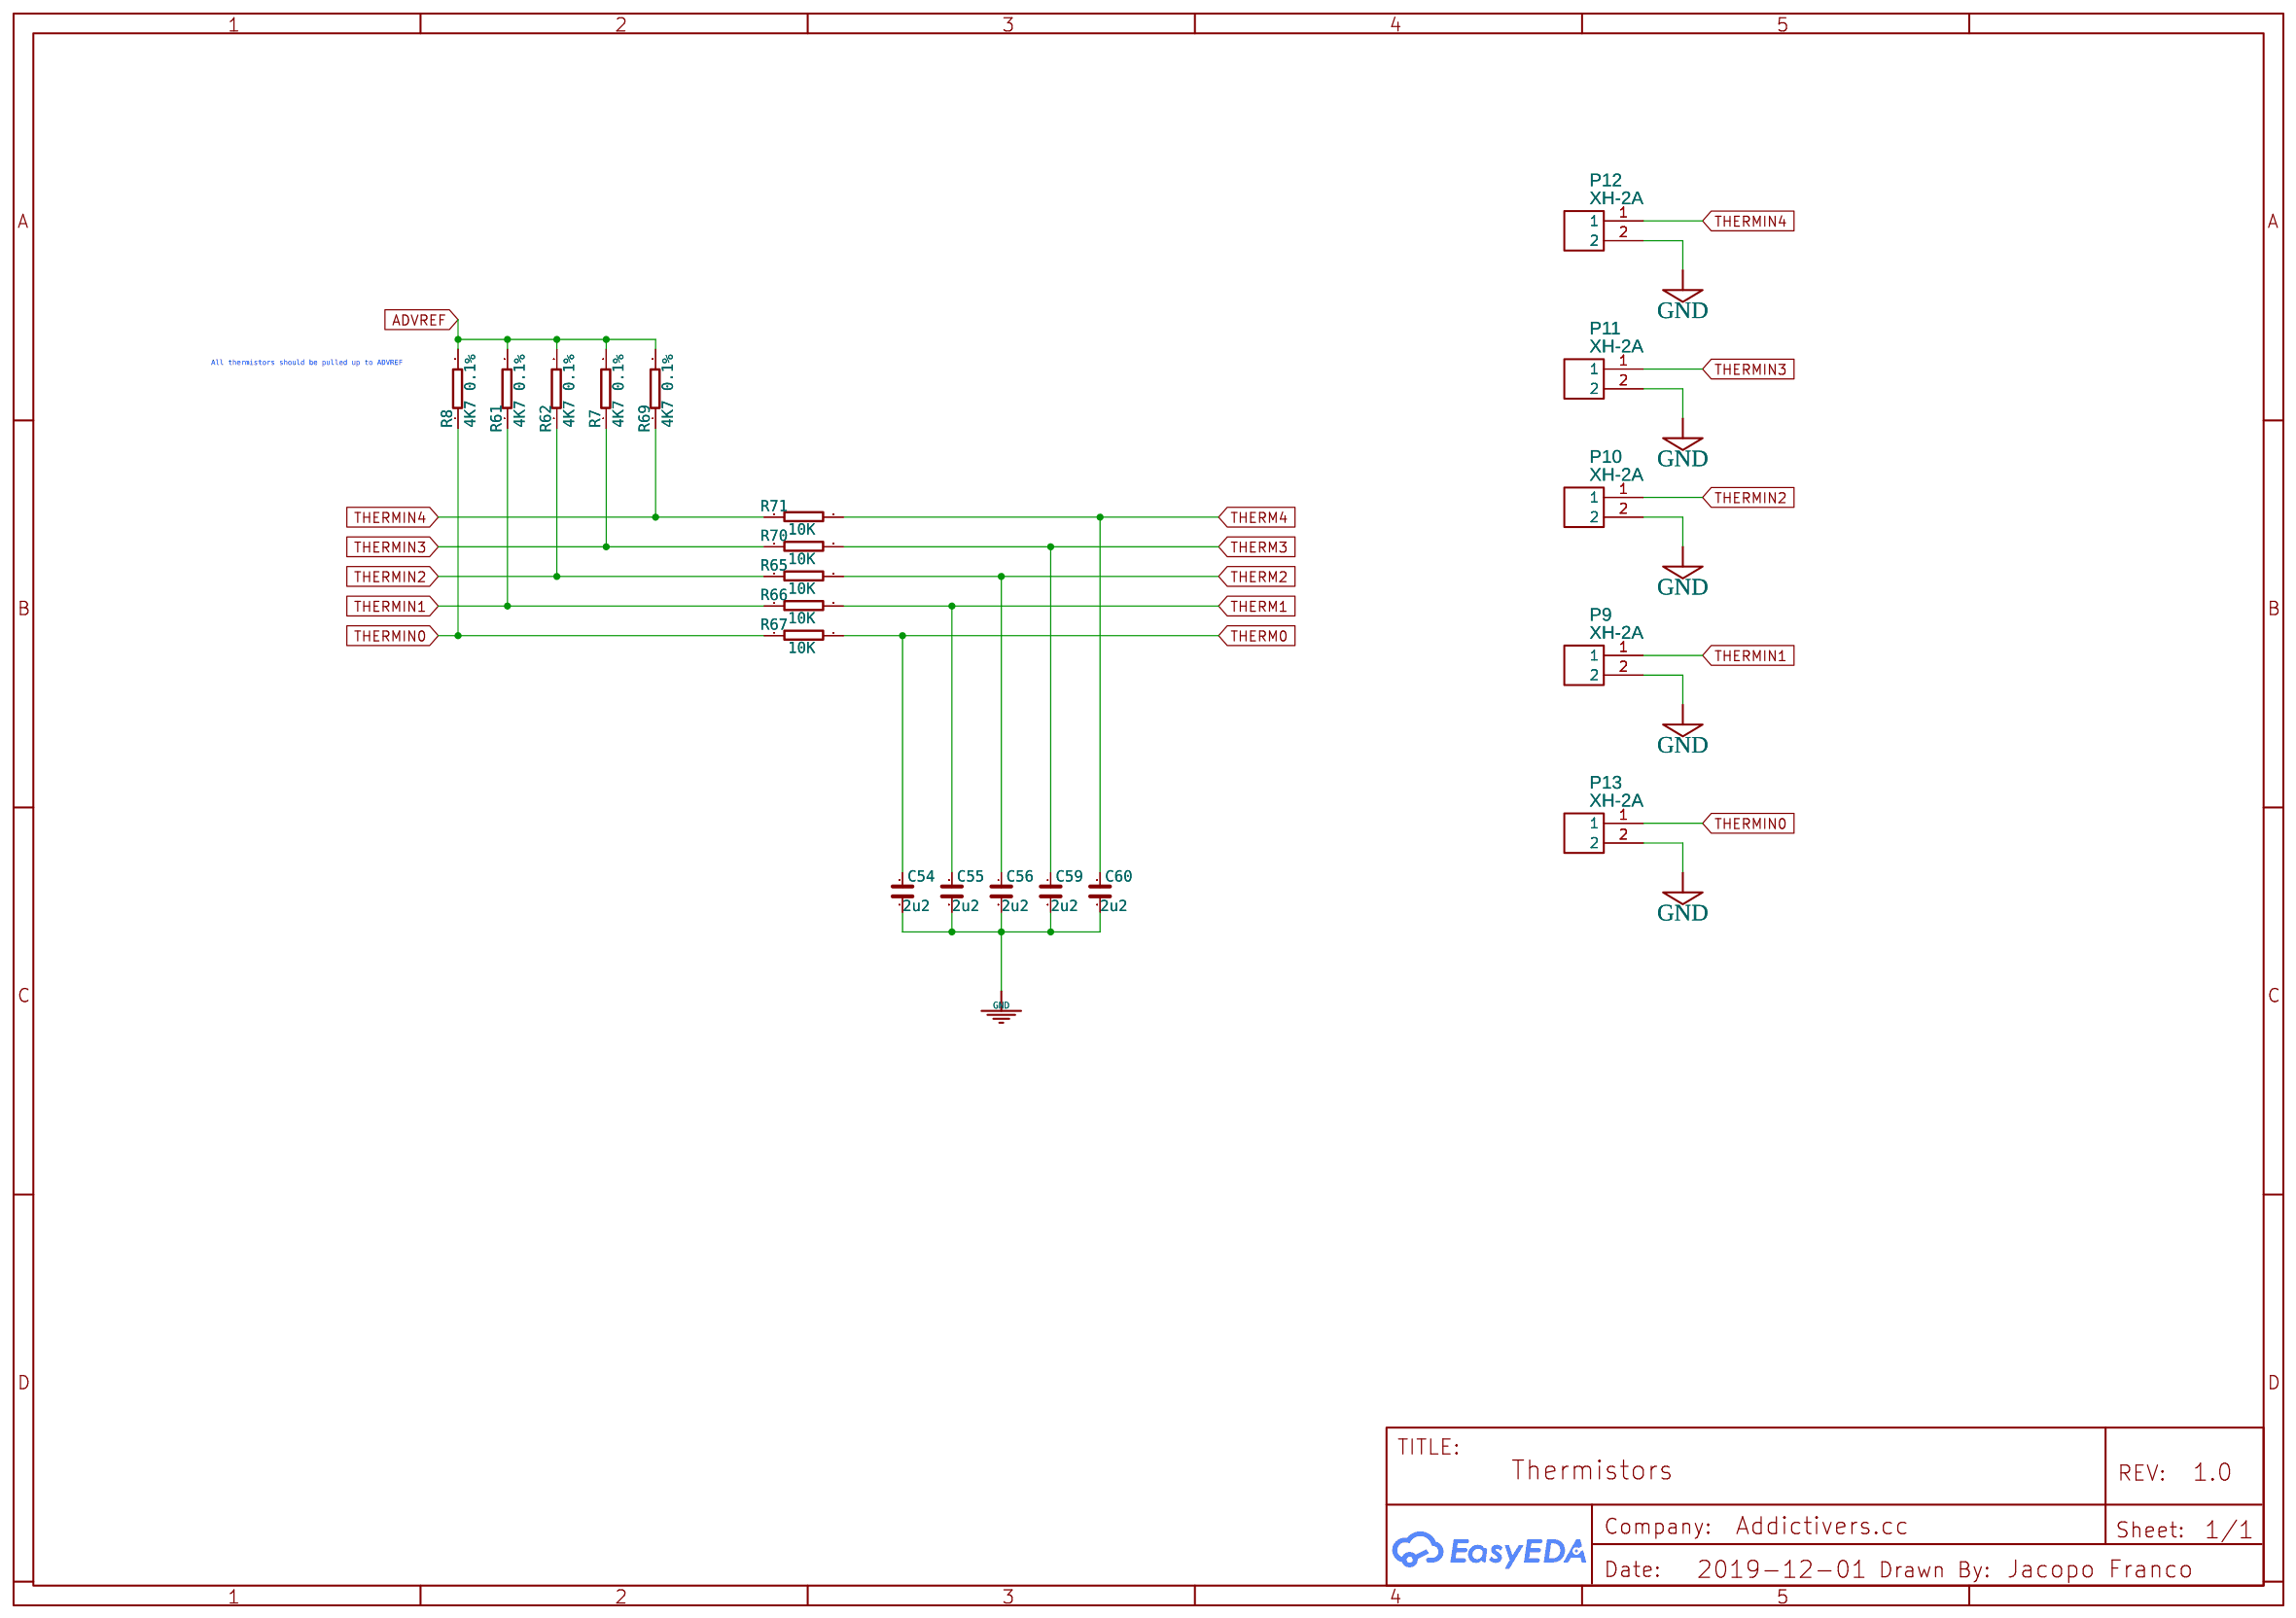
[diagram p6: Thermistors]
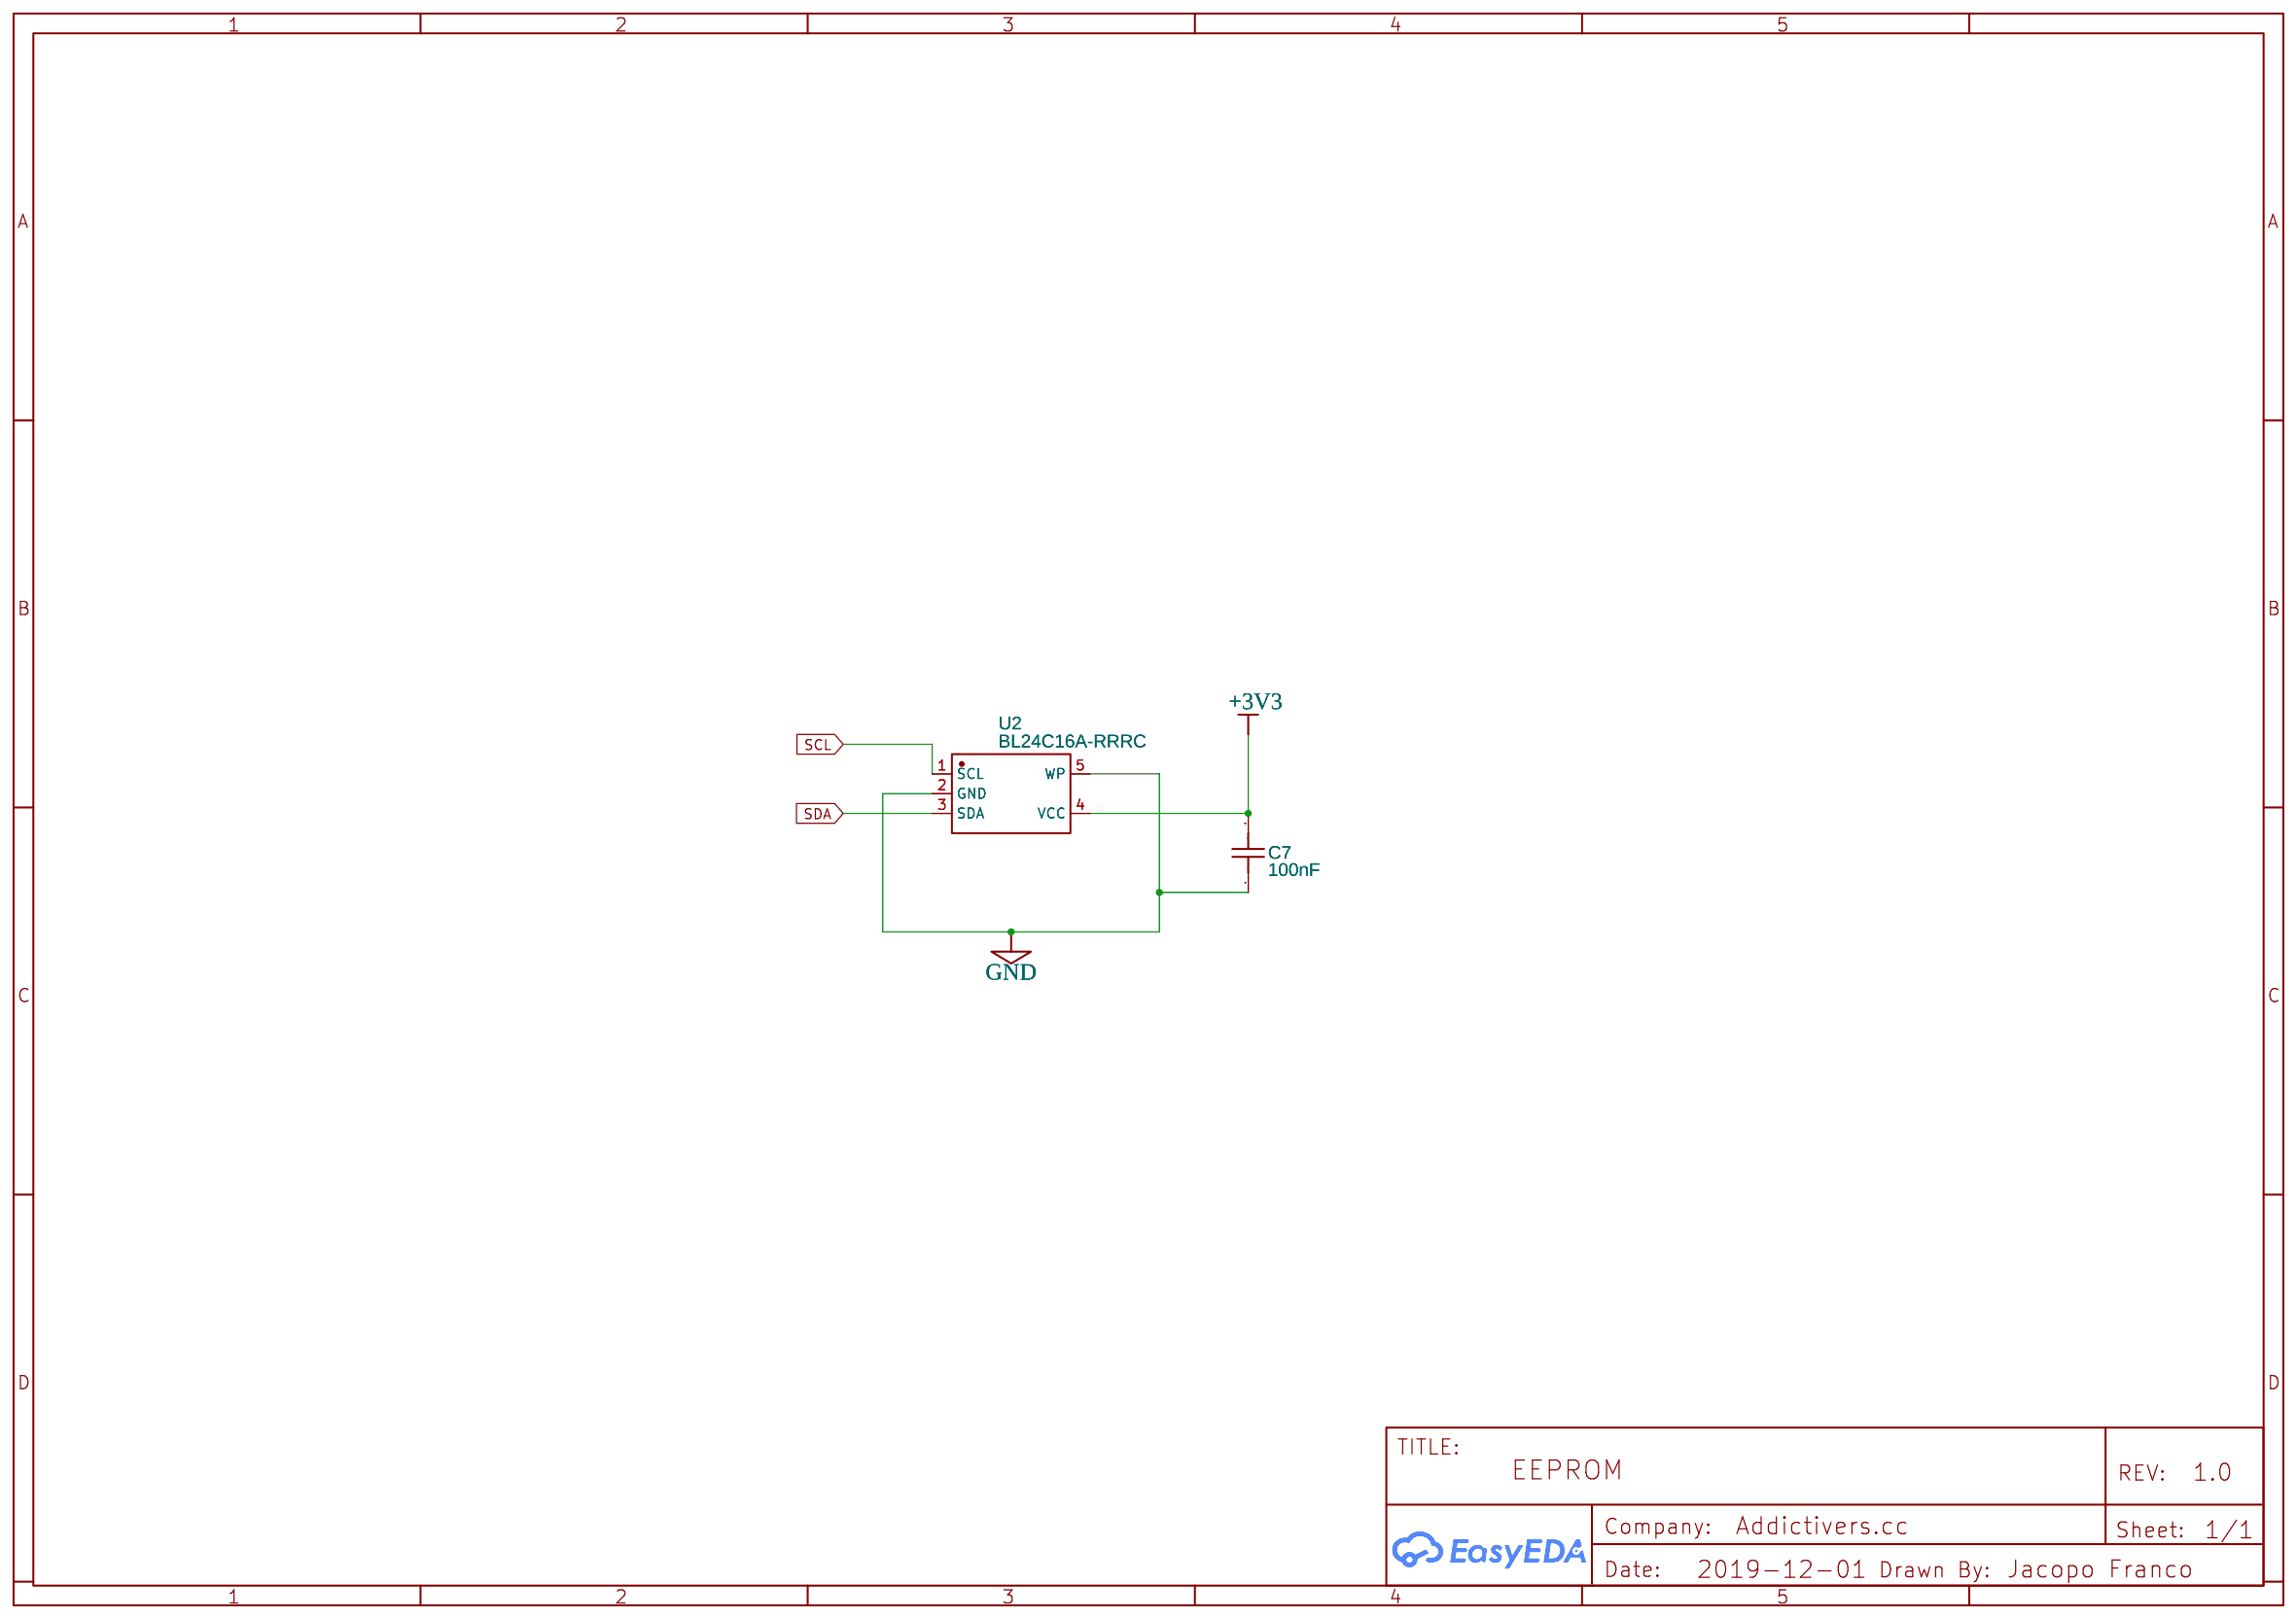
[diagram p7: EEPROM]
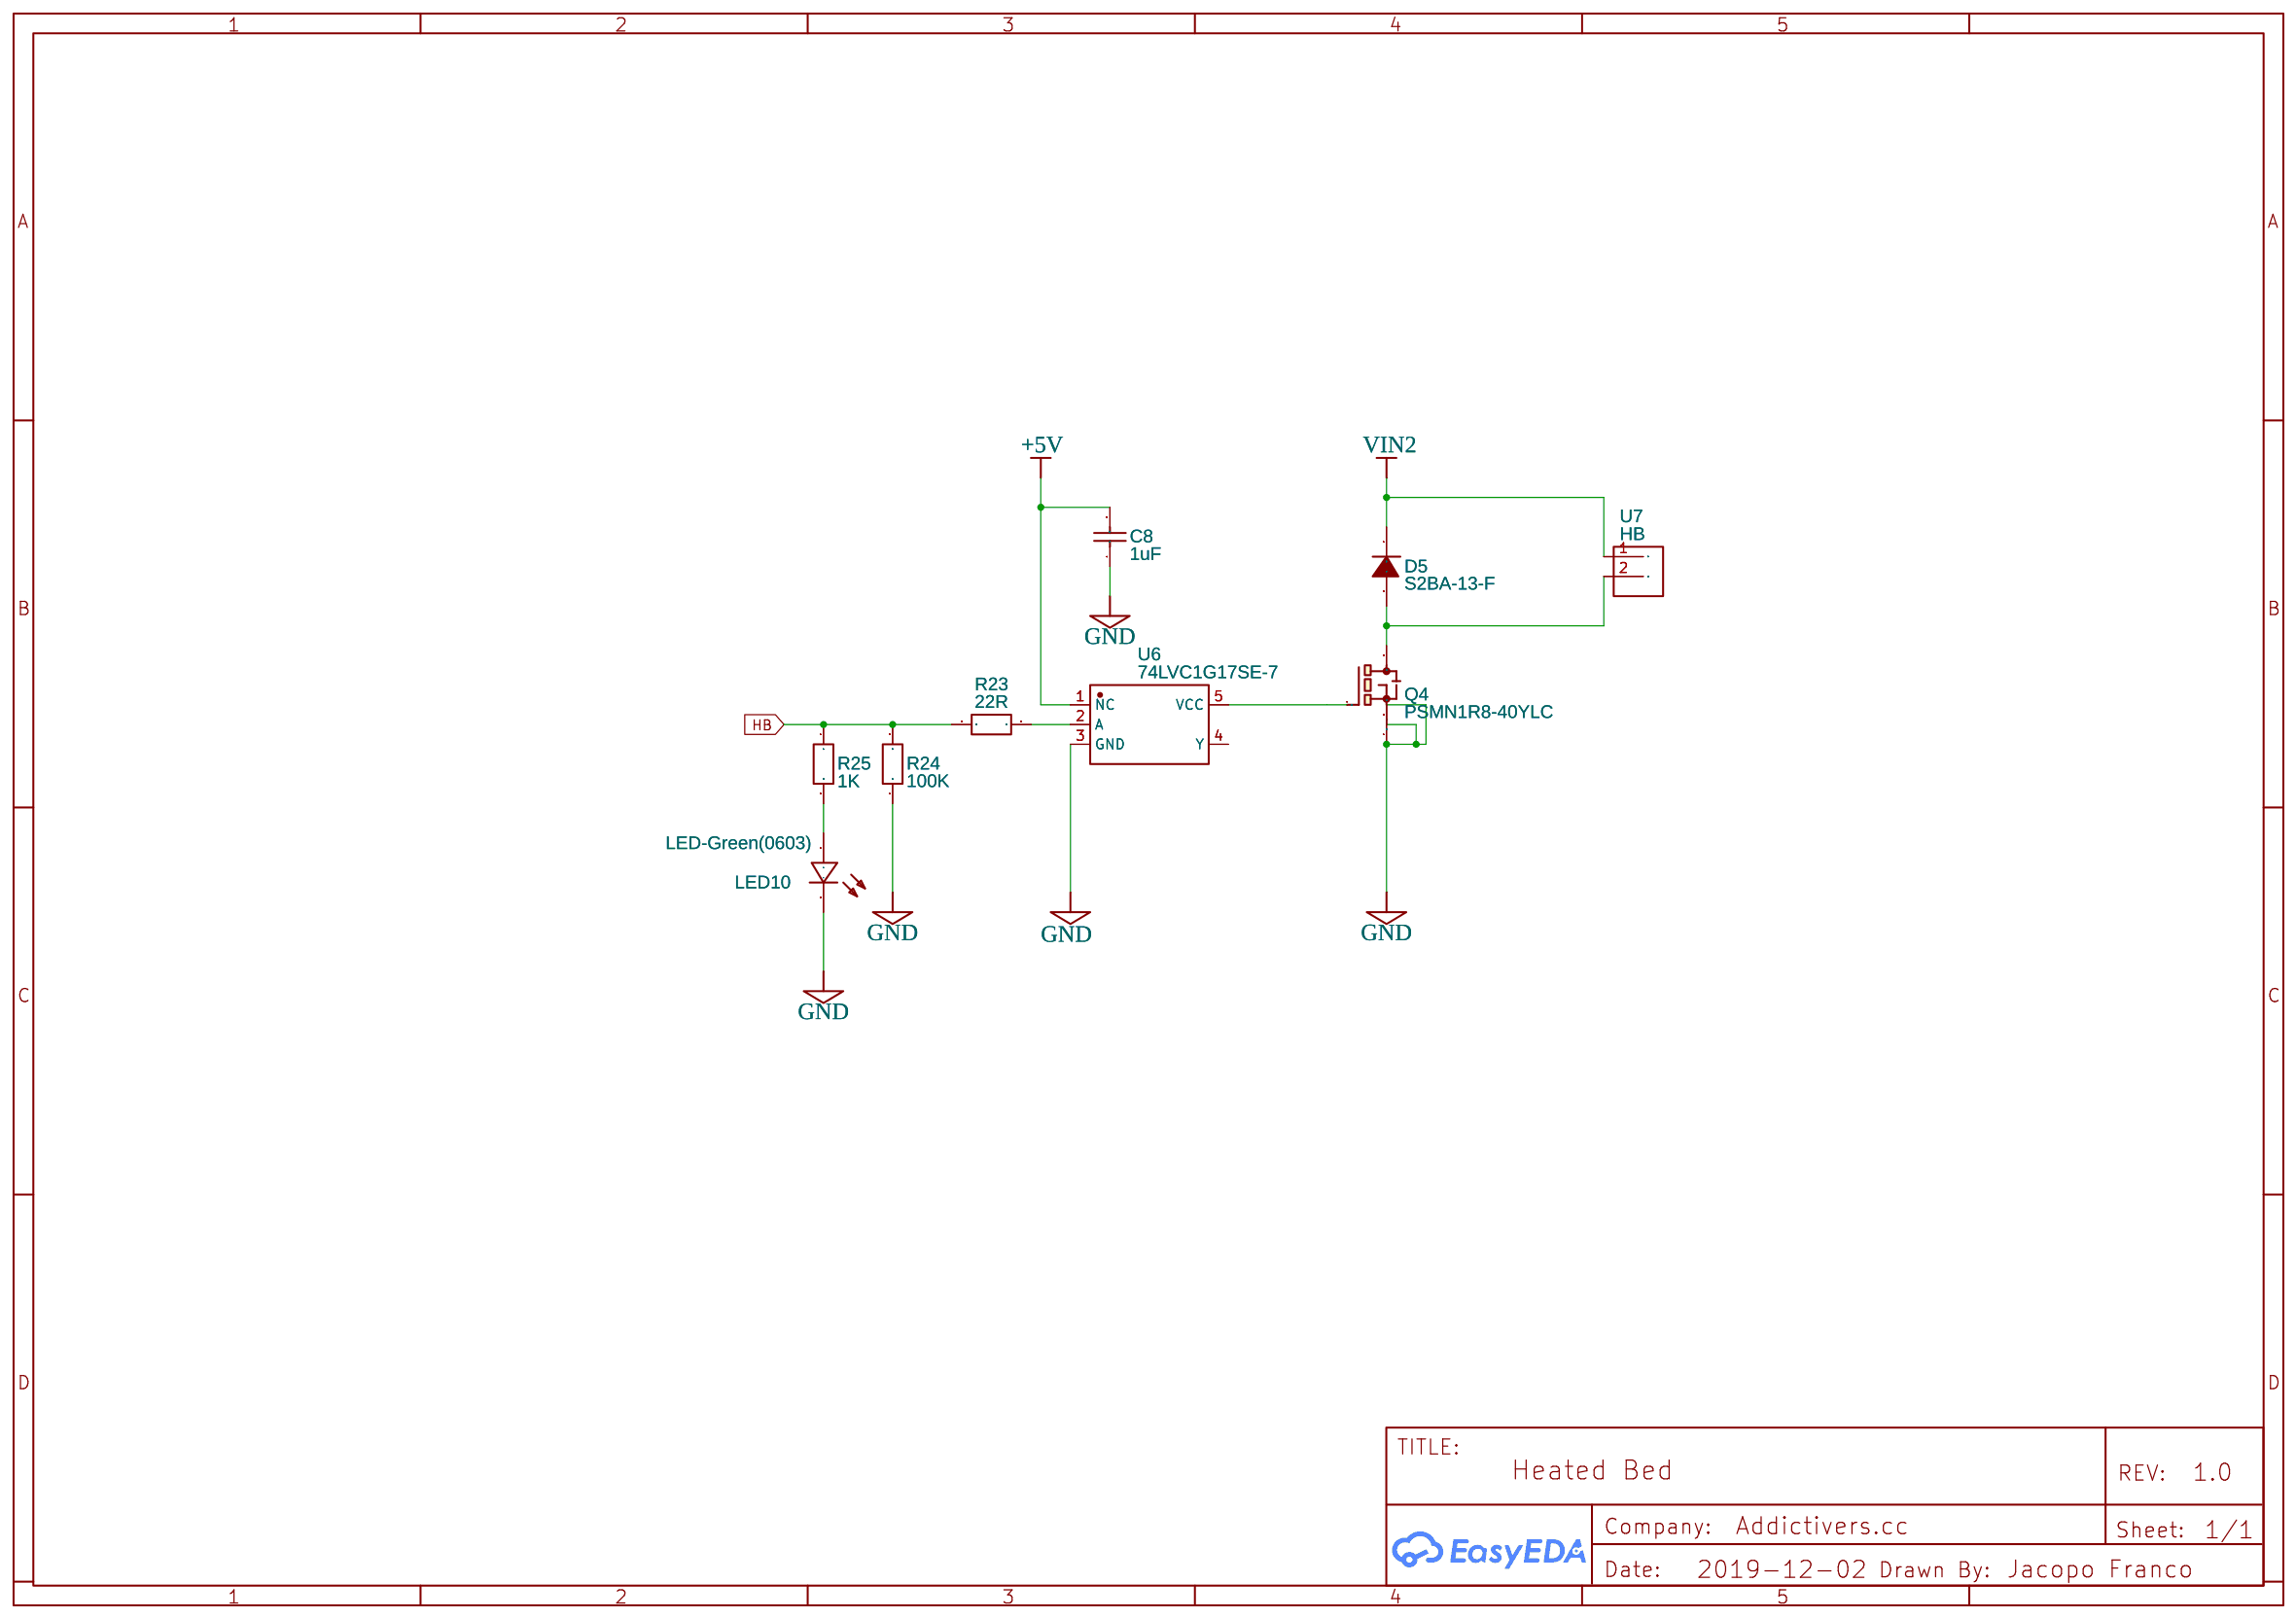
[diagram p8: Heated Bed]
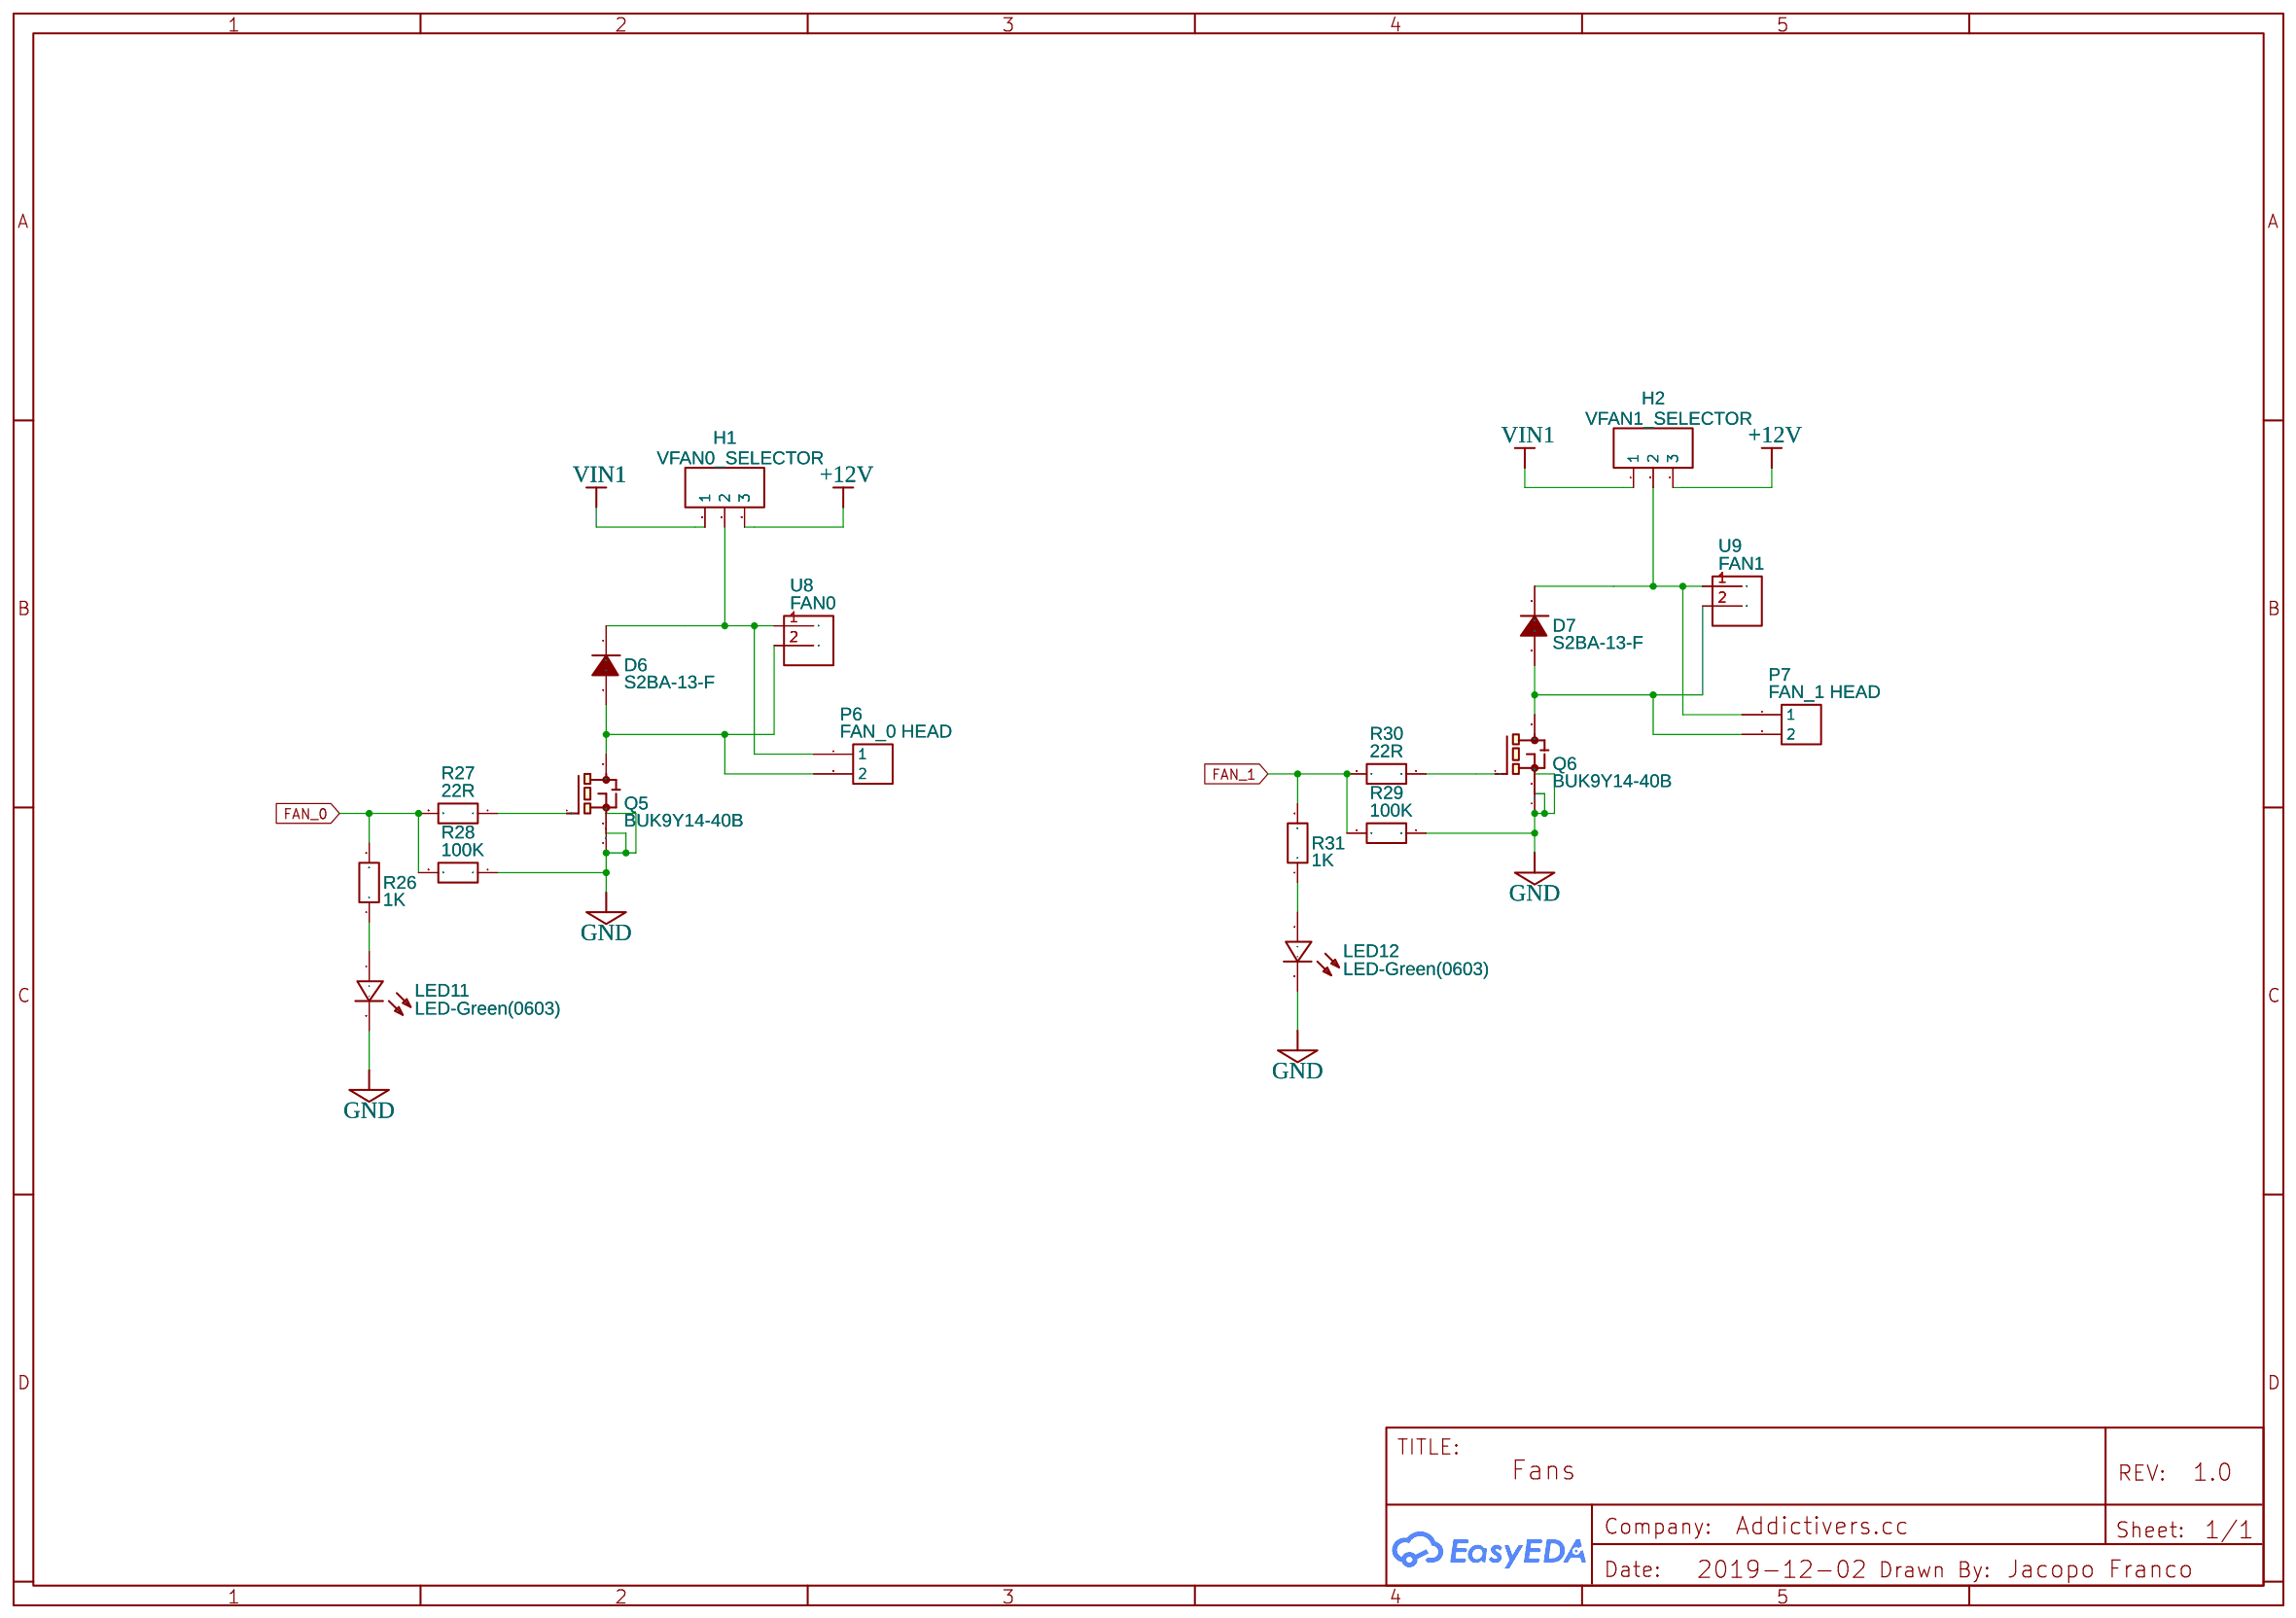
[diagram p9: Fans]
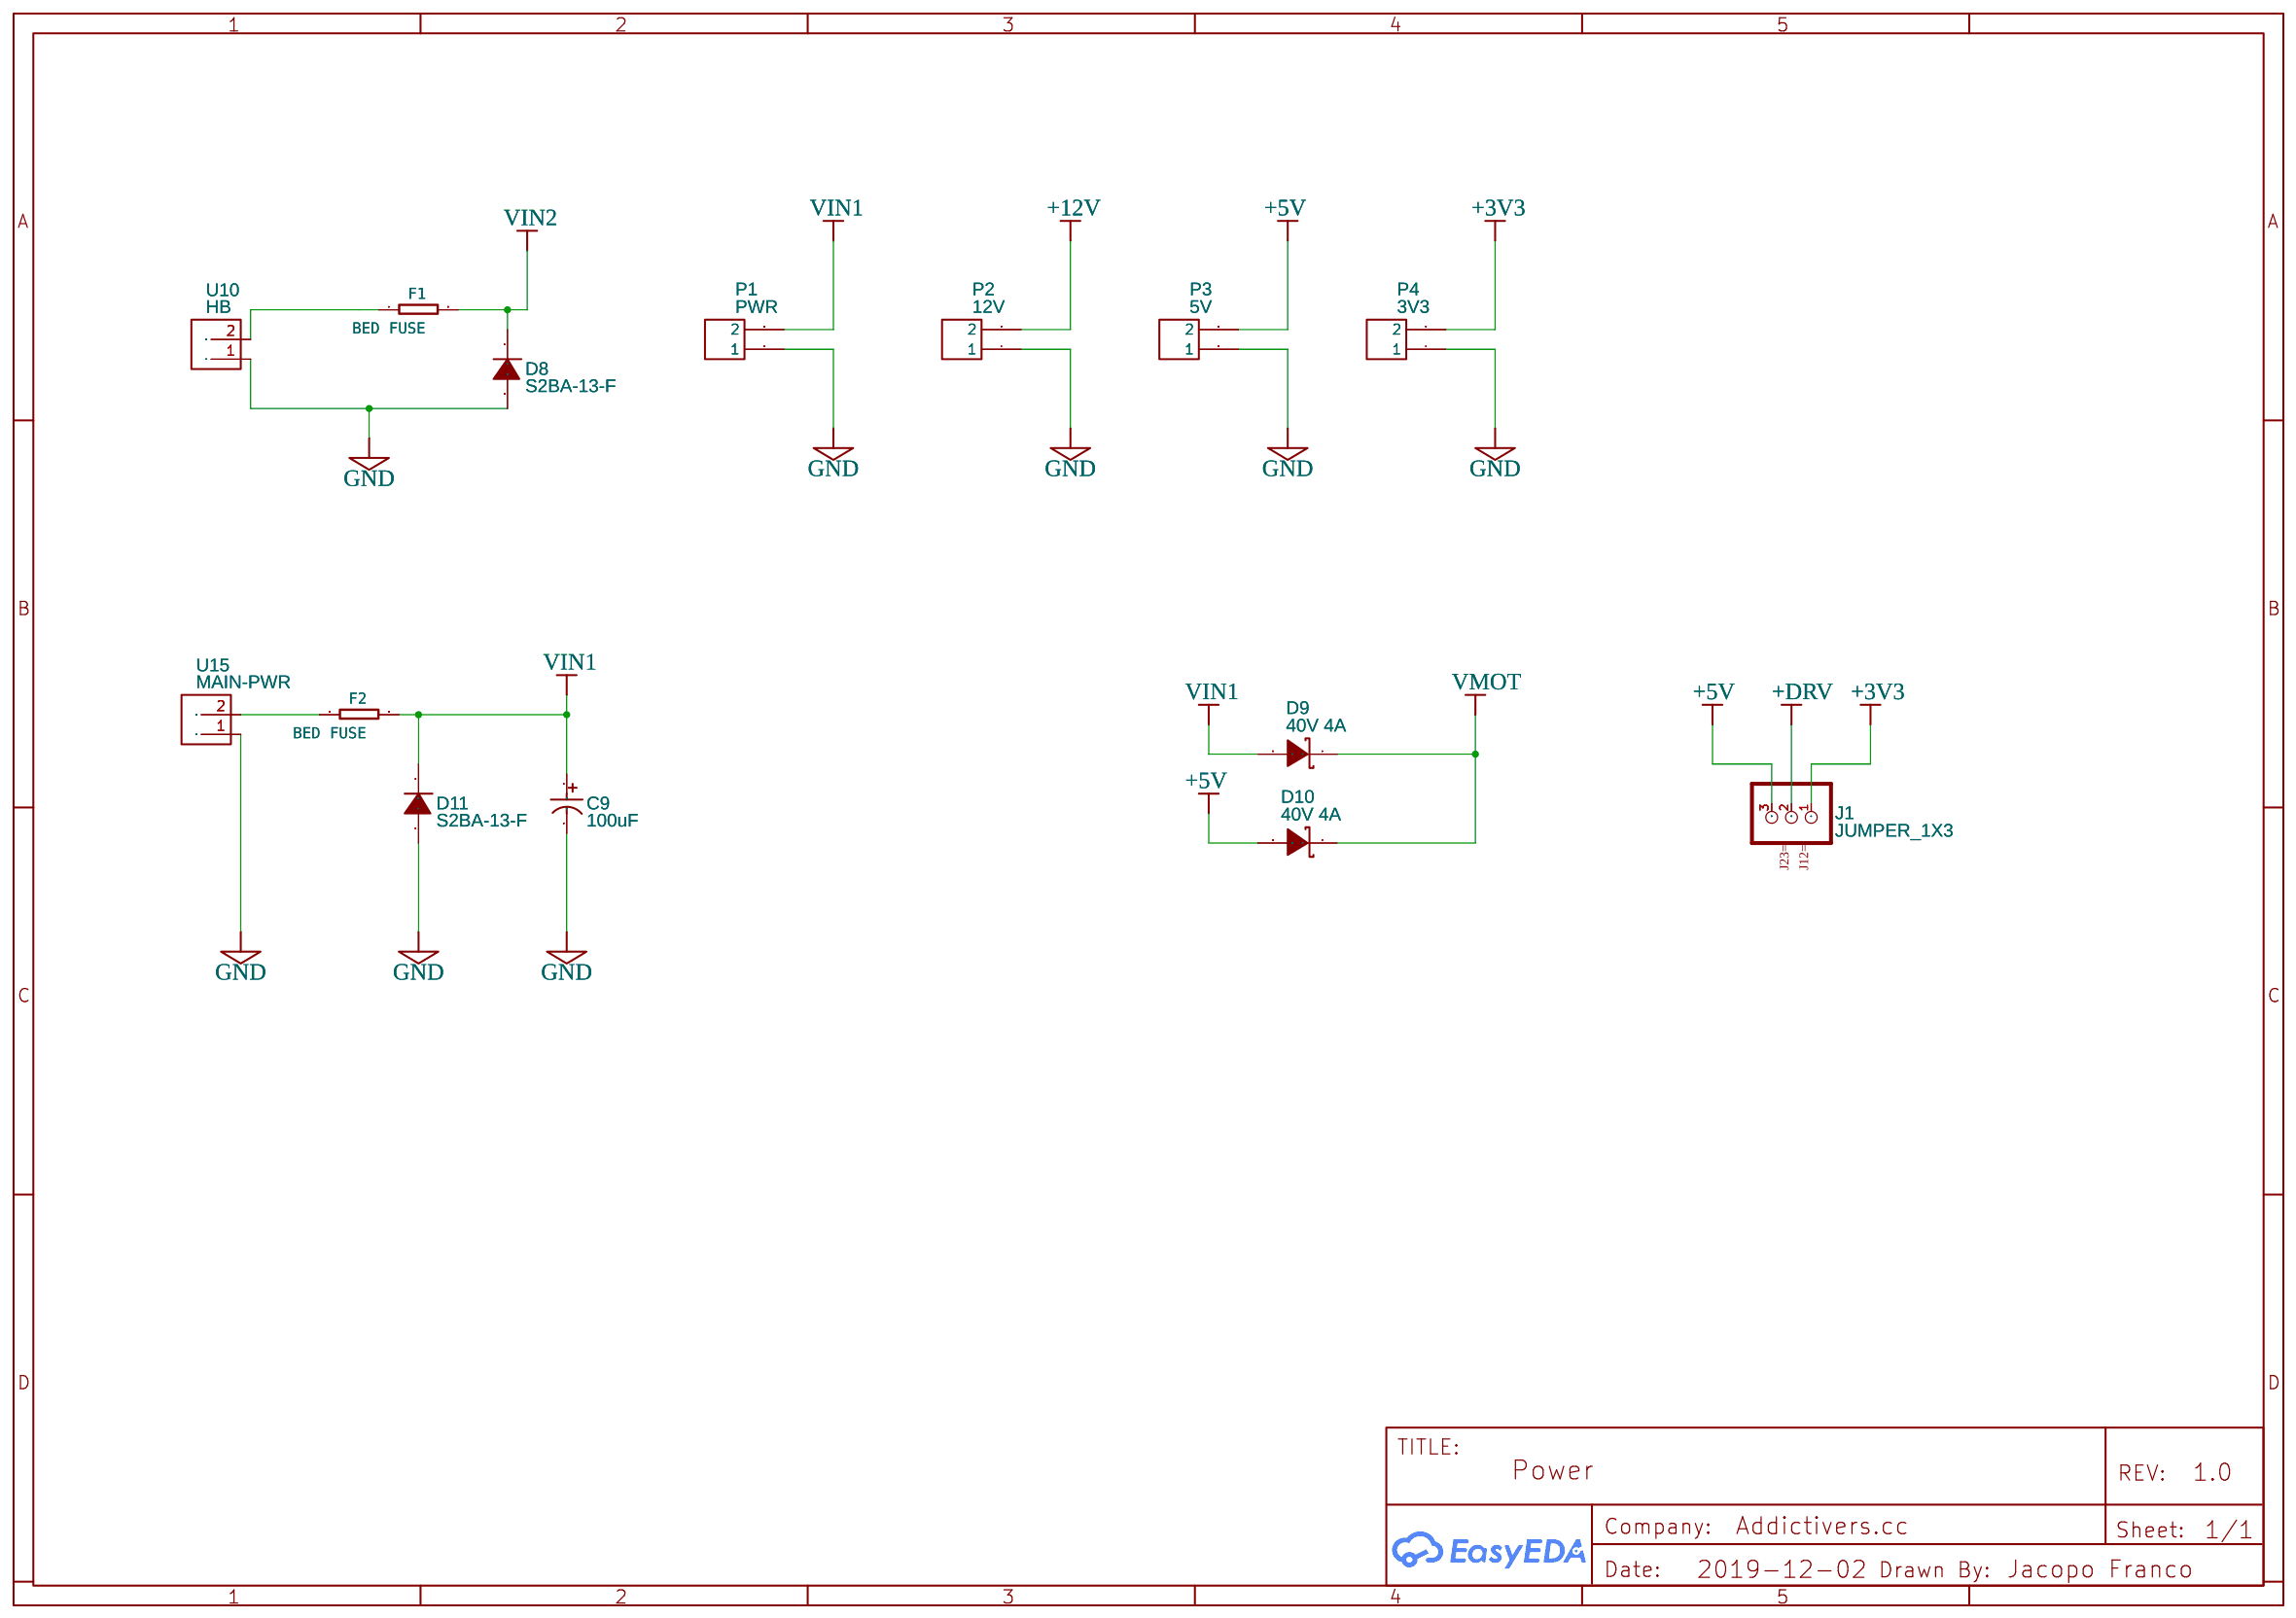
[diagram p10: Power]
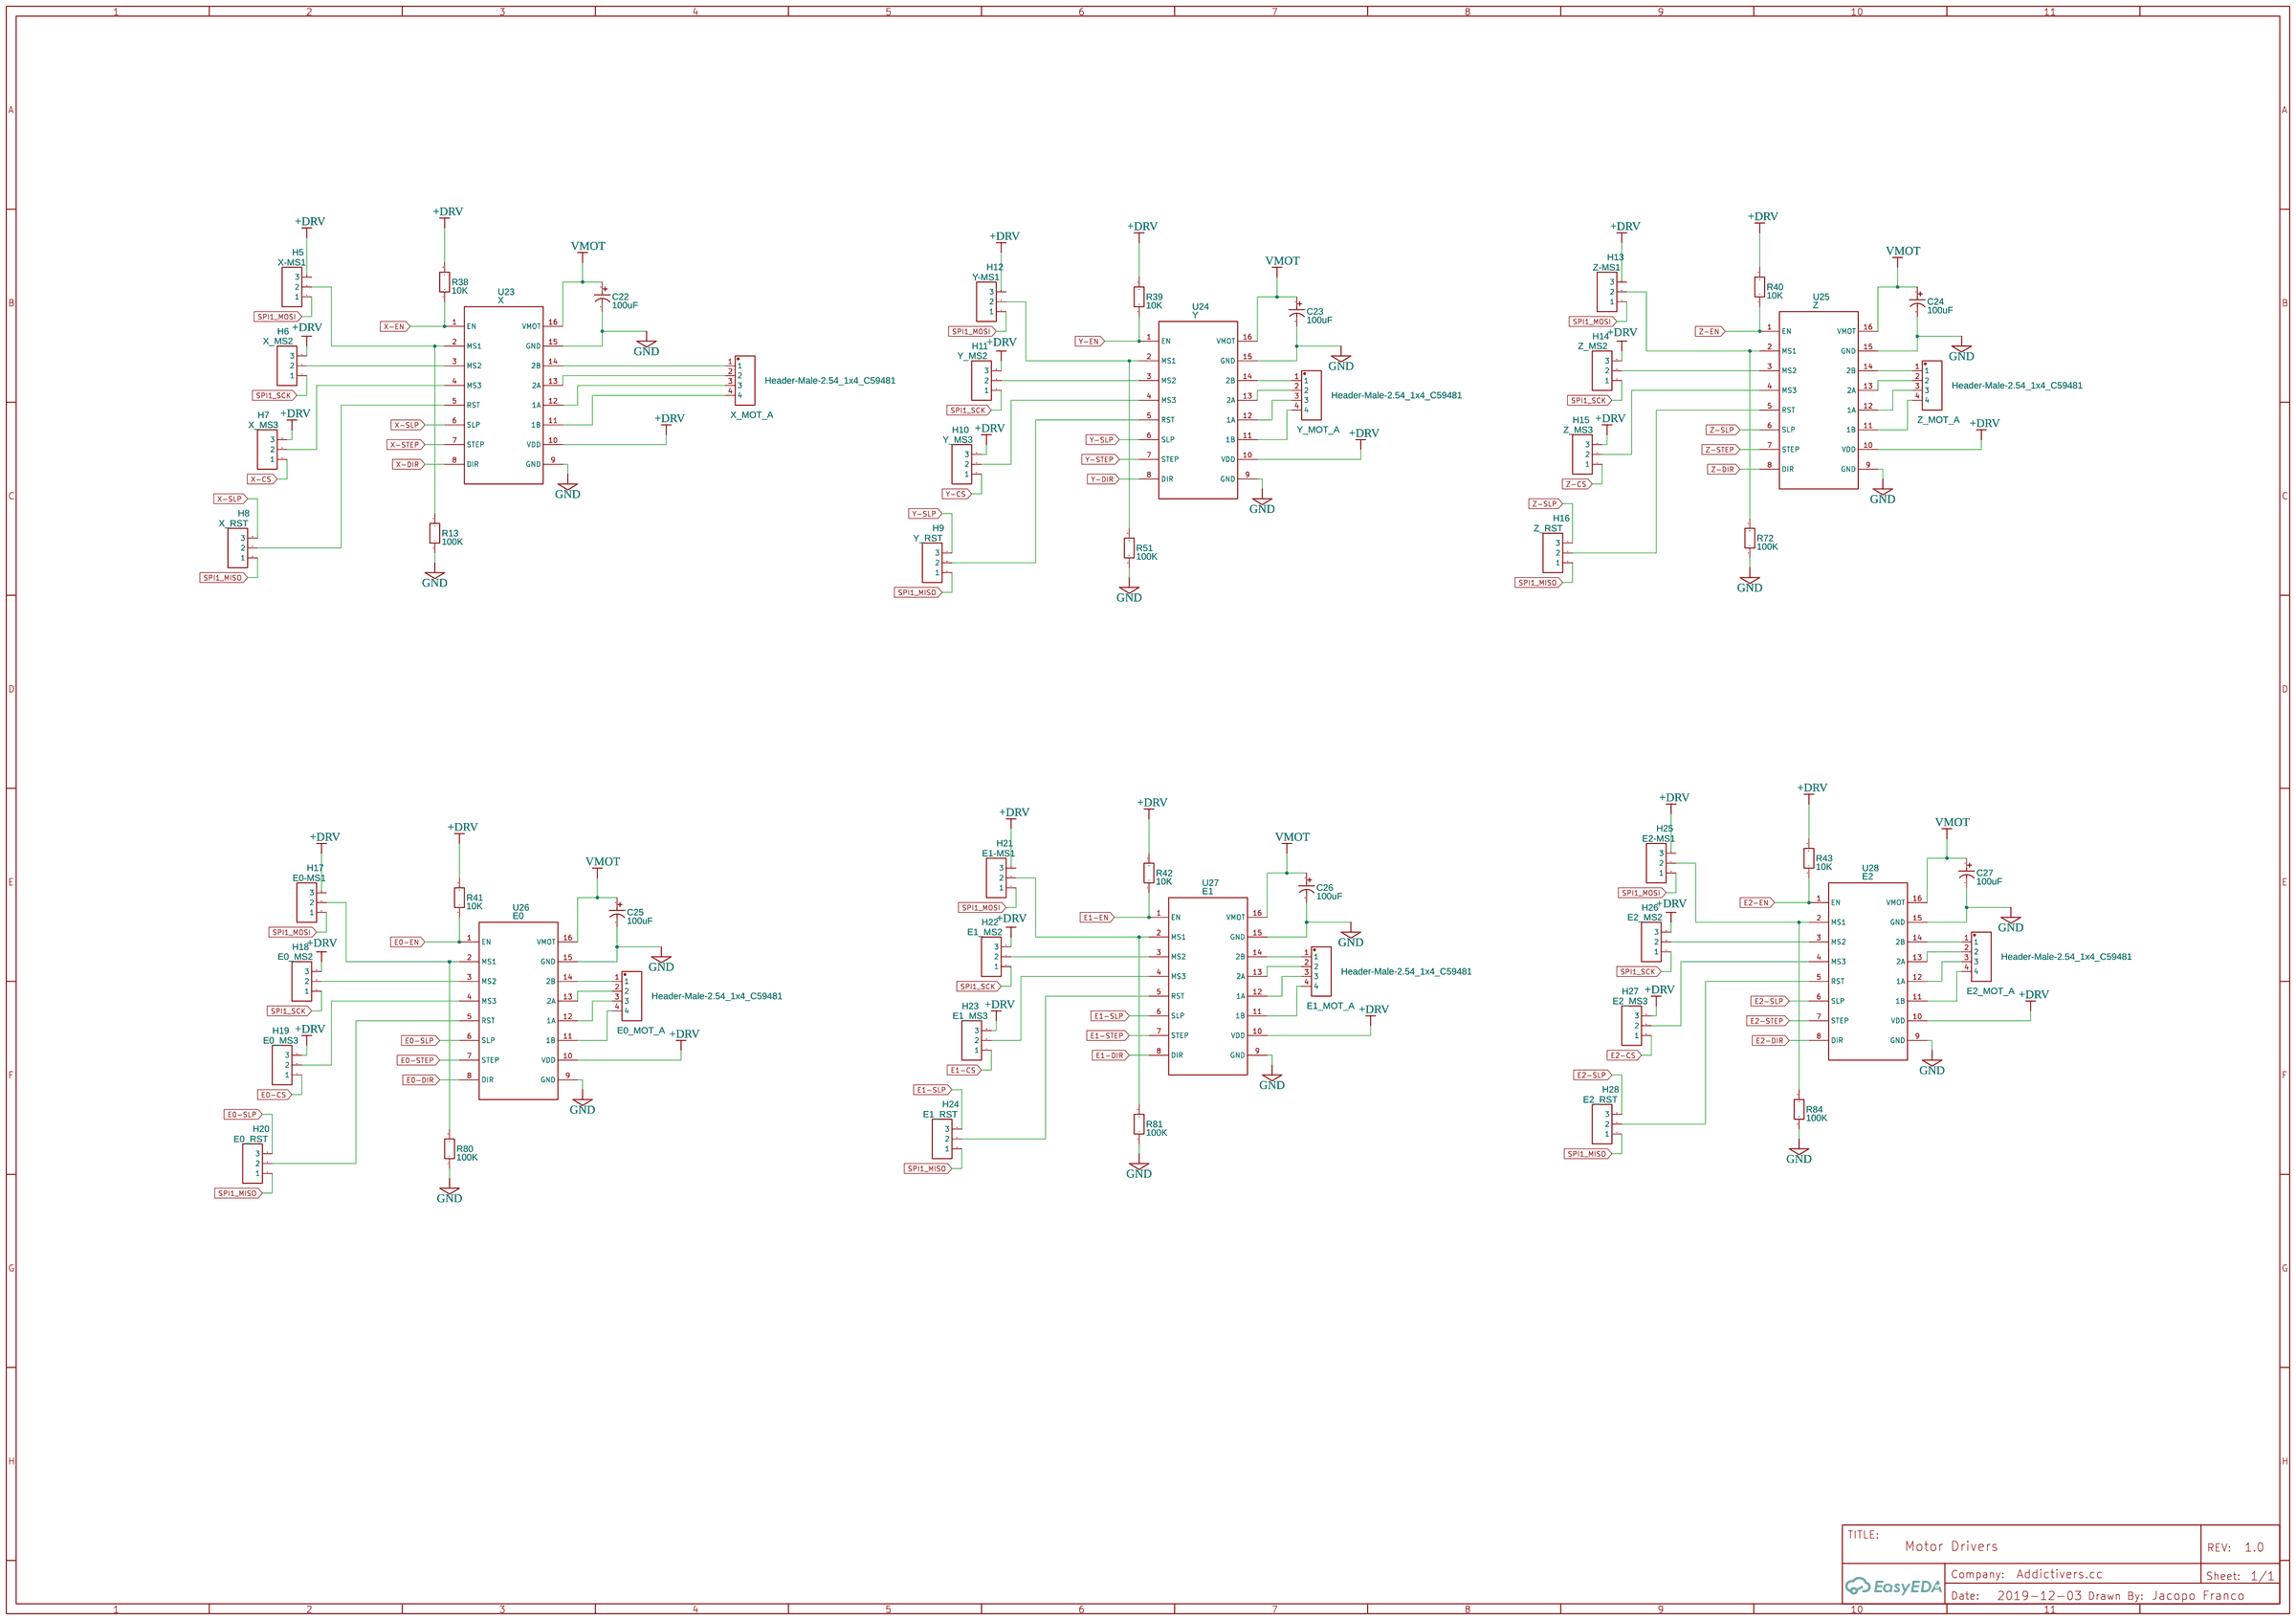
[diagram p11: Motor Drivers]
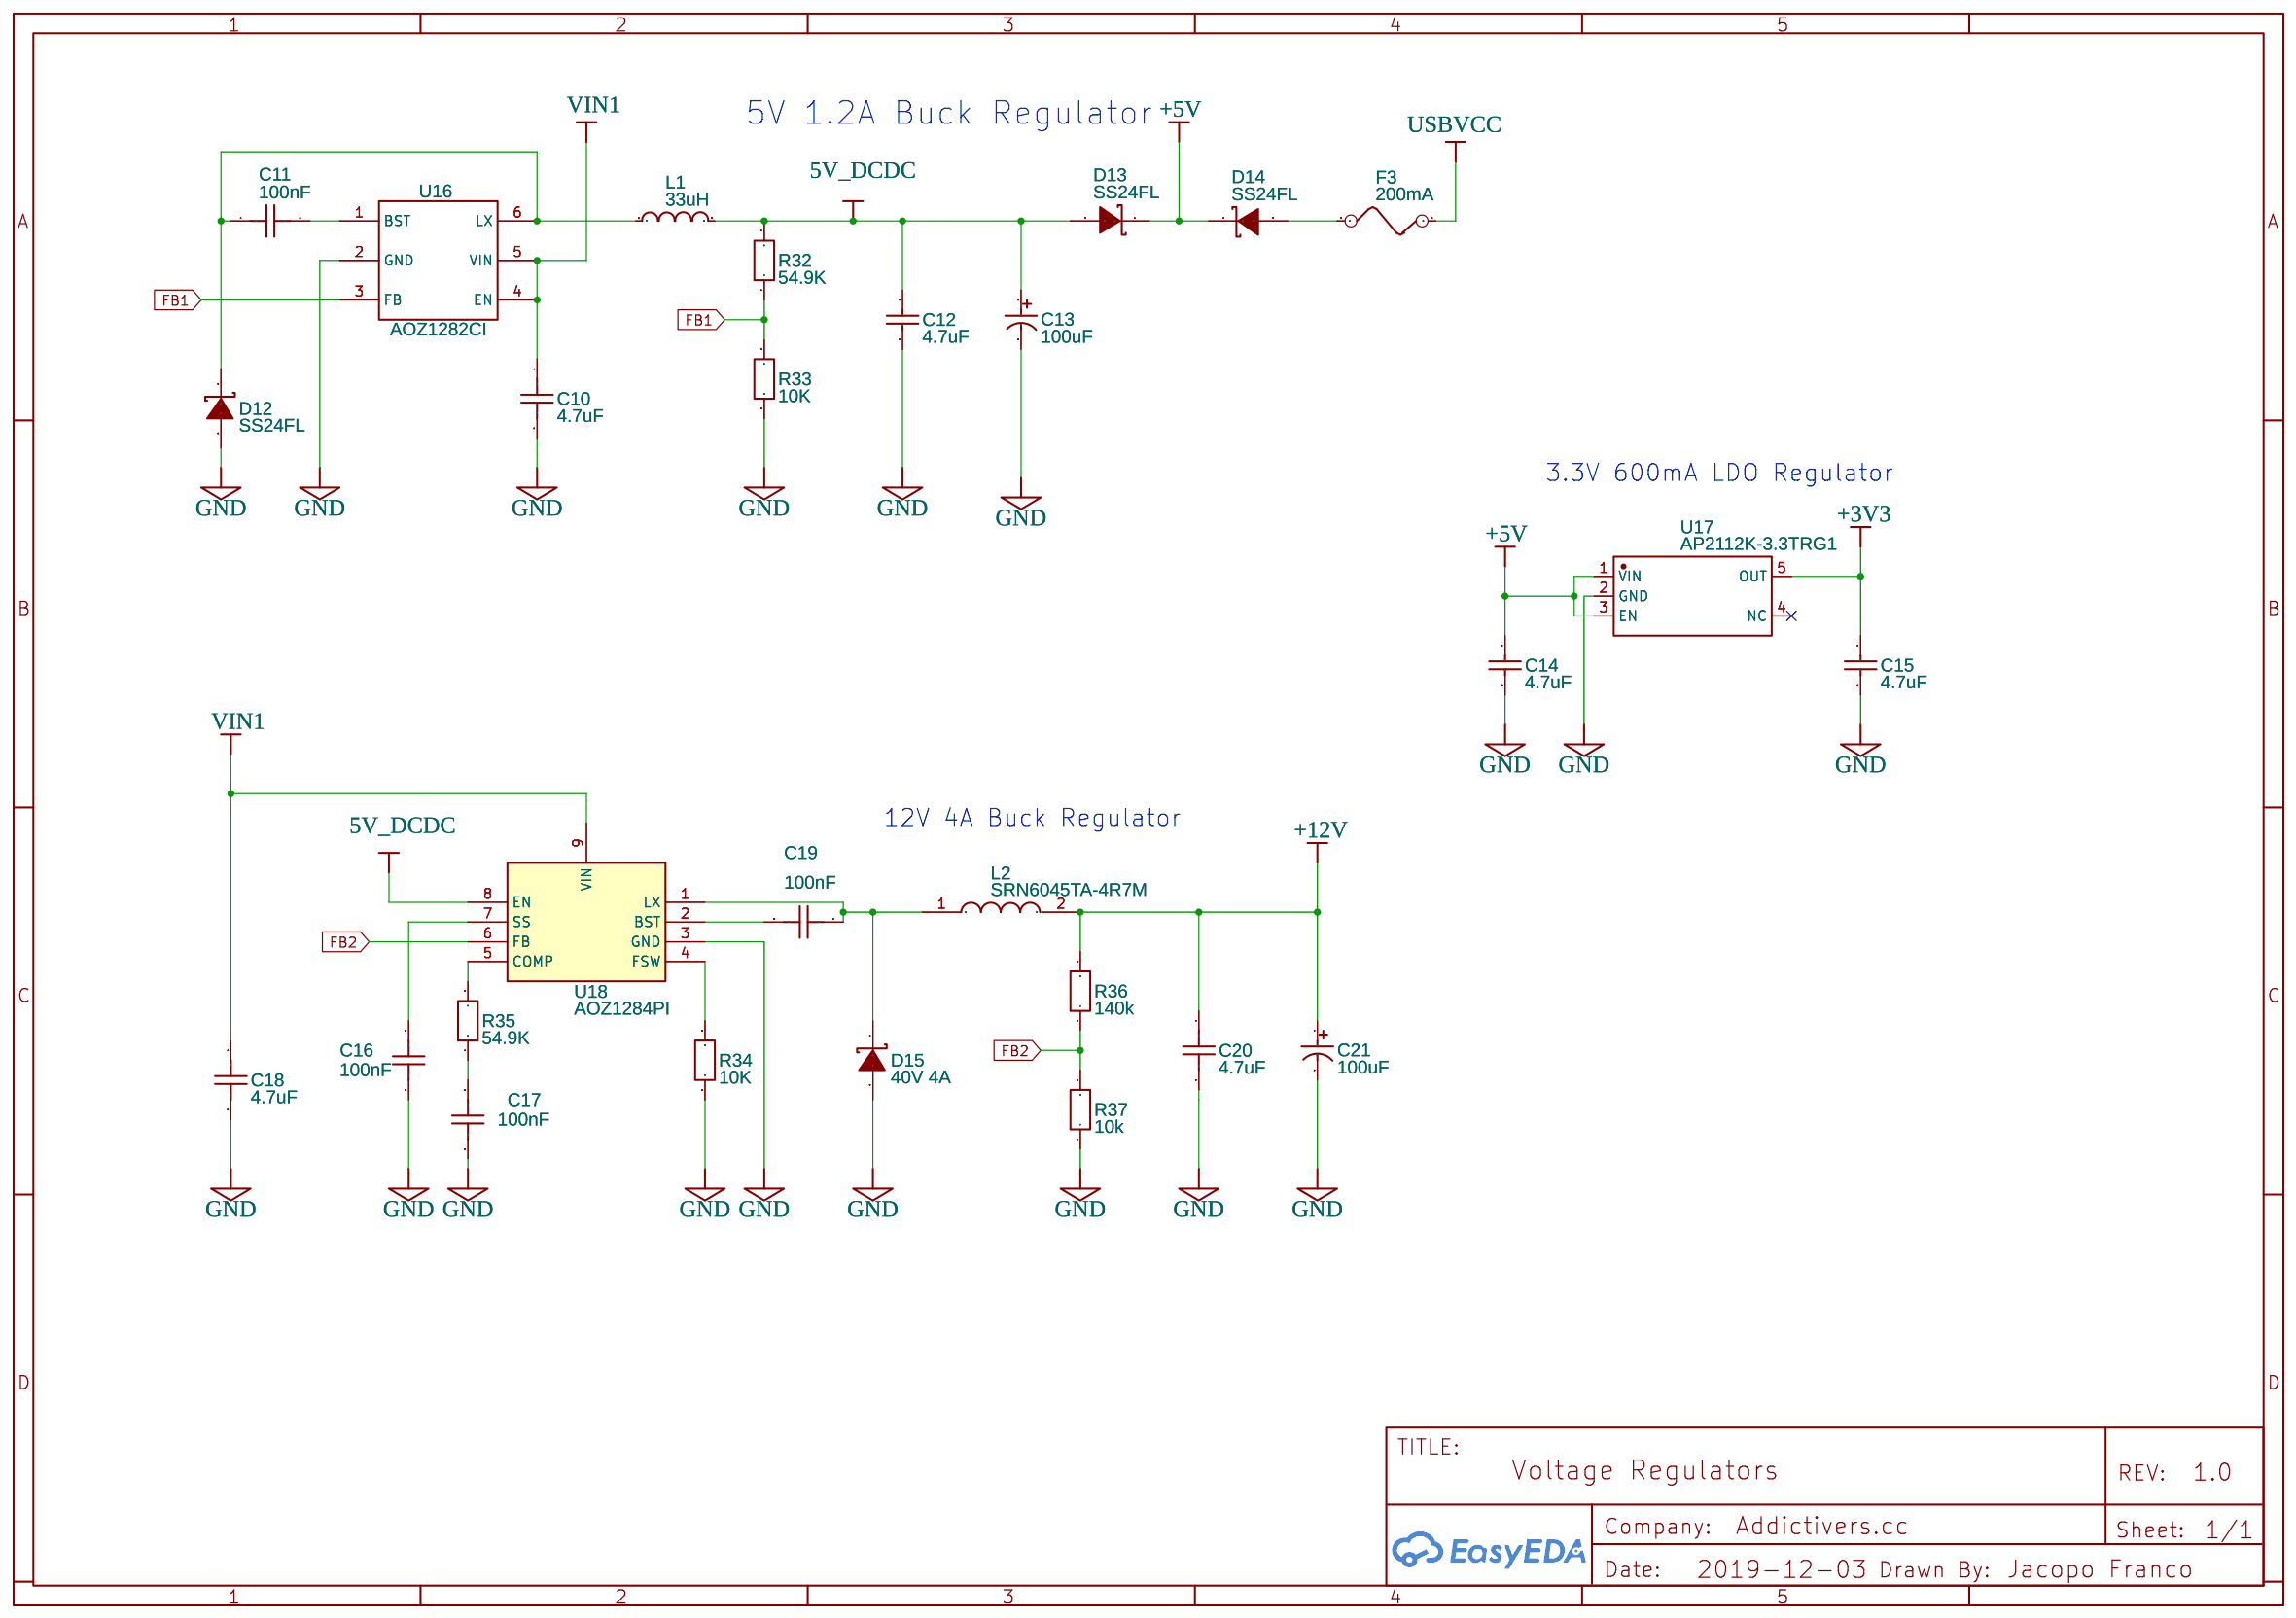
[diagram p12: Voltage regulators]
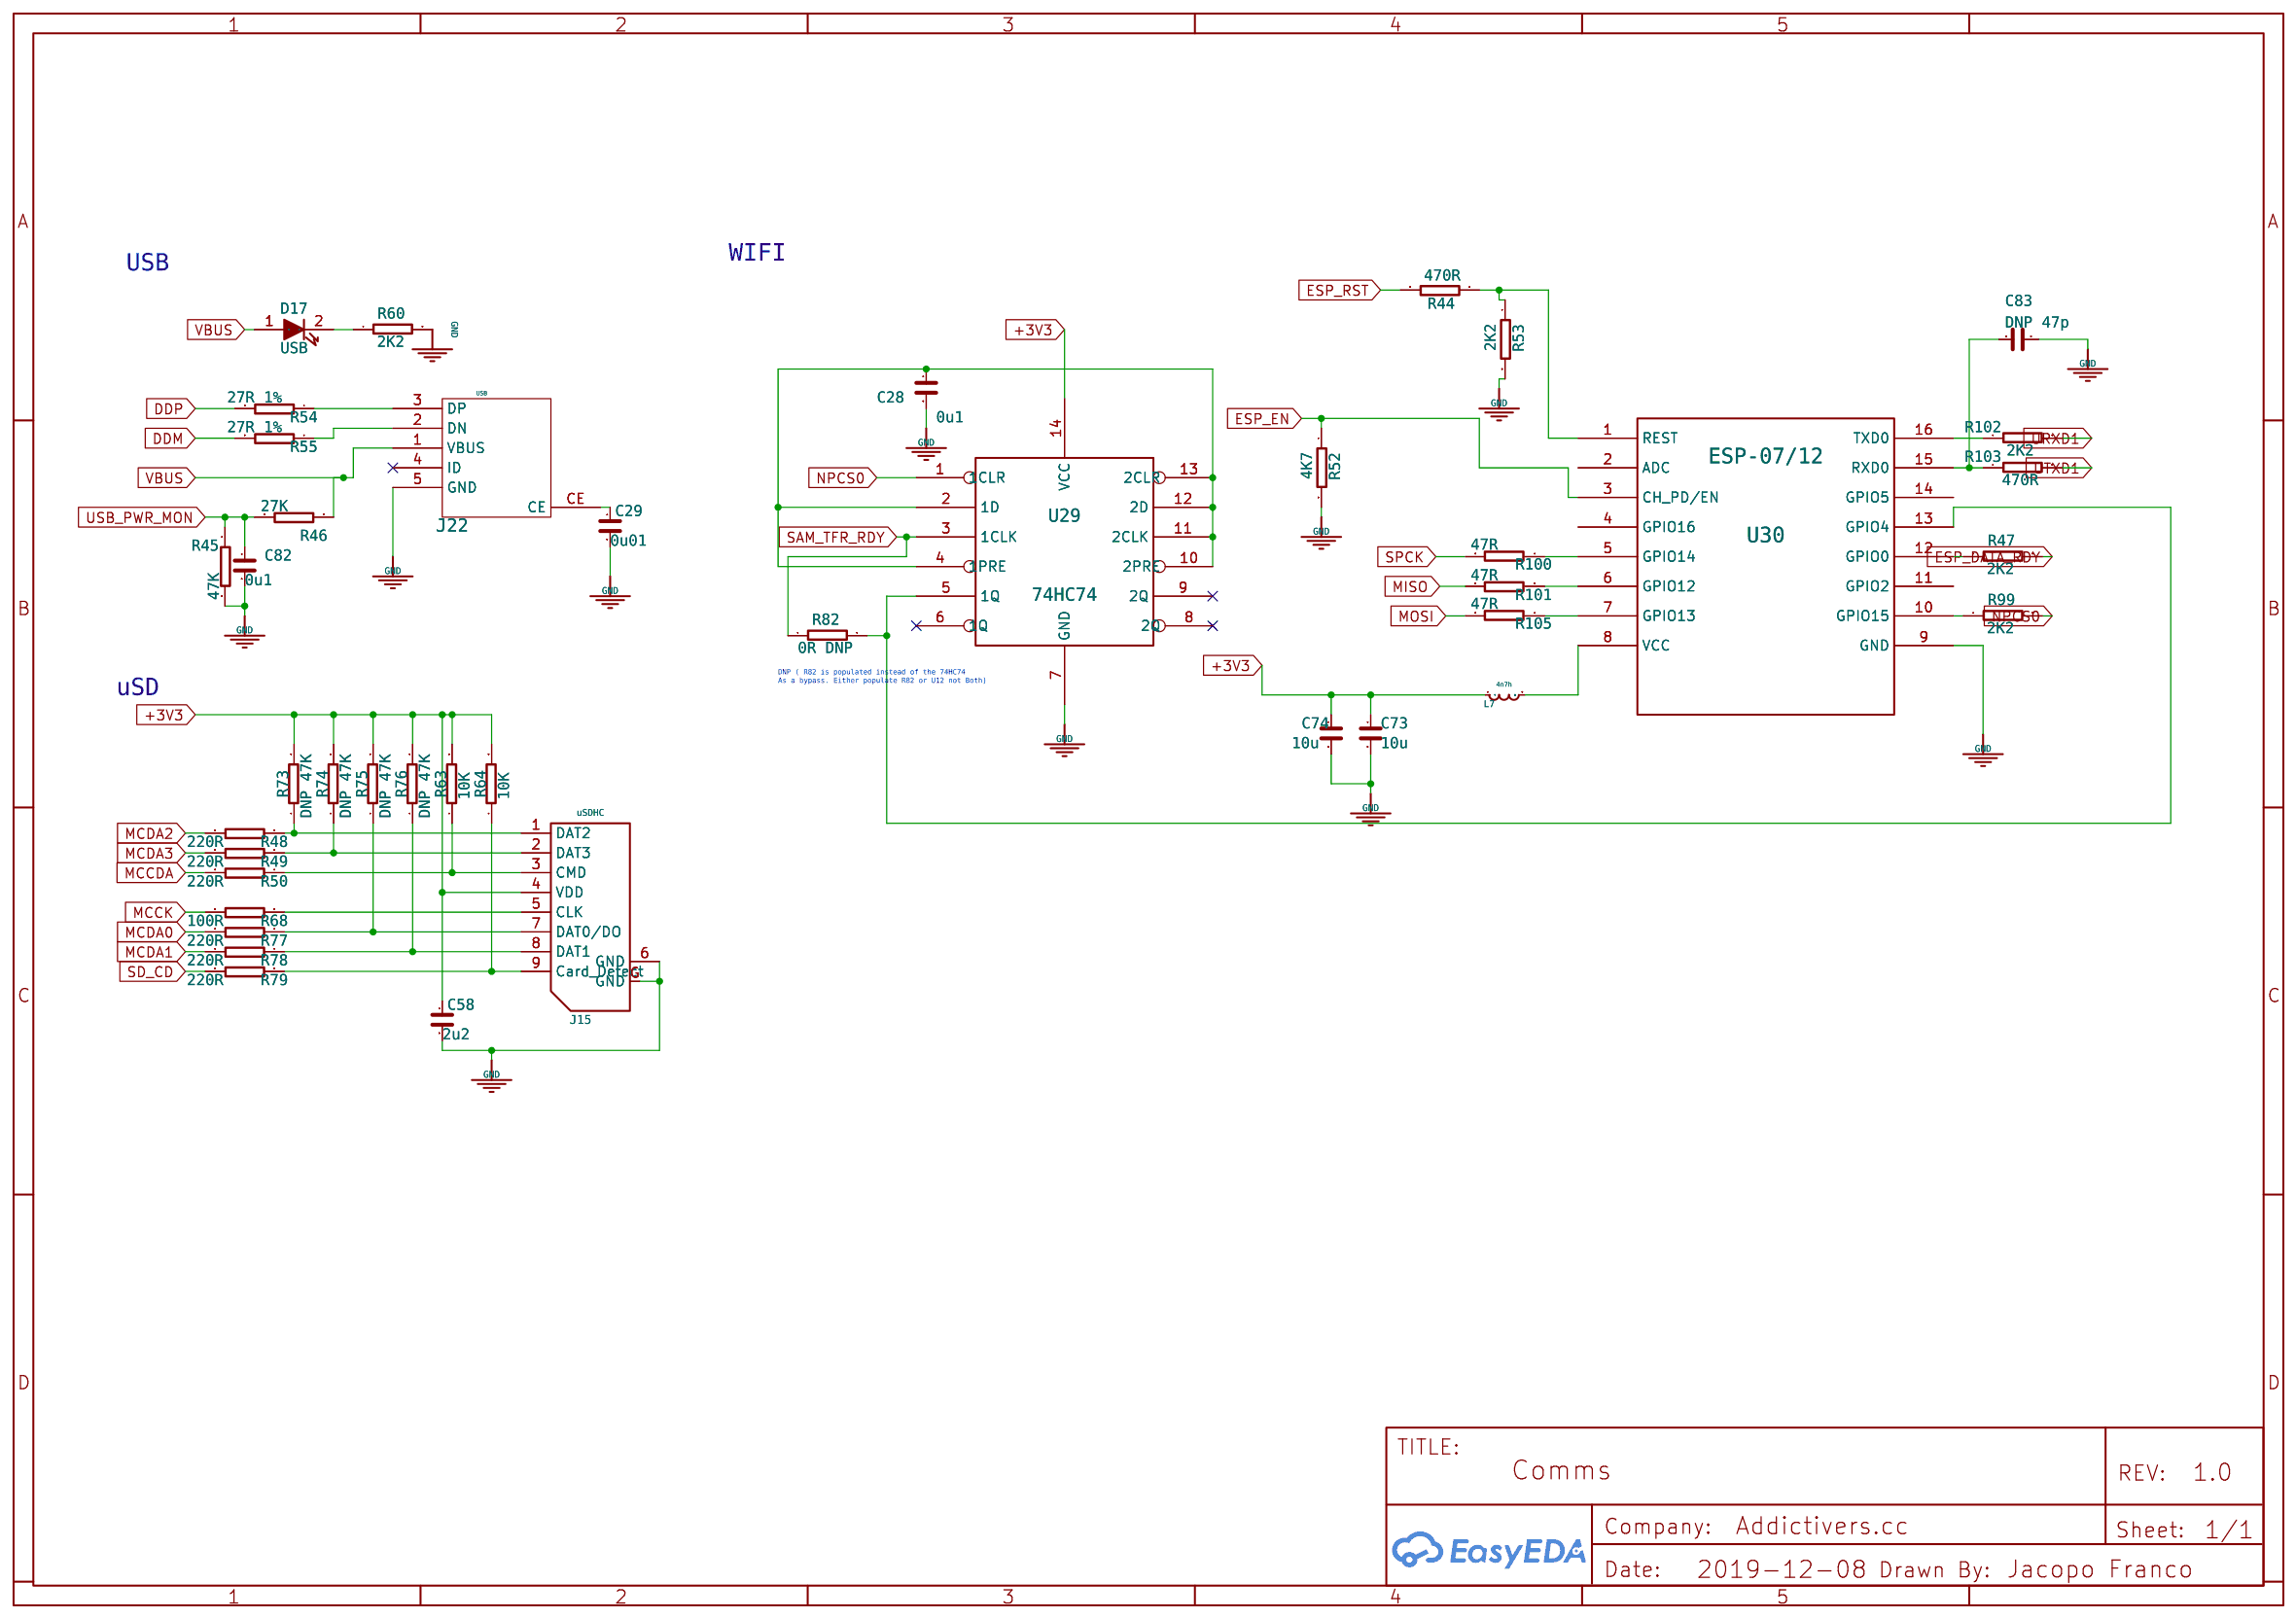
[diagram p13: Comms]

(export (version "E")
  (design (tool "Eeschema 10.0.6"))
  (components
    (comp (ref "LED1")
      (value "LED-Green(0603)")
      (fields
        (field (name "BOM_Manufacturer Part") "FC-DA1608UGK-520D10")
        (field (name "BOM_Supplier Part") "C84267")
      )
      (libsource (lib "") (part "Unknown_390_300"))
    )
    (comp (ref "LED2")
      (value "LED-Green(0603)")
      (fields
        (field (name "BOM_Manufacturer Part") "FC-DA1608UGK-520D10")
        (field (name "BOM_Supplier Part") "C84267")
      )
      (libsource (lib "") (part "Unknown_505_365"))
    )
    (comp (ref "LED3")
      (value "LED-Green(0603)")
      (fields
        (field (name "BOM_Manufacturer Part") "FC-DA1608UGK-520D10")
        (field (name "BOM_Supplier Part") "C84267")
      )
      (libsource (lib "") (part "Unknown_620_365"))
    )
    (comp (ref "LED4")
      (value "LED-Green(0603)")
      (fields
        (field (name "BOM_Manufacturer Part") "FC-DA1608UGK-520D10")
        (field (name "BOM_Supplier Part") "C84267")
      )
      (libsource (lib "") (part "Unknown_730_300"))
    )
    (comp (ref "LED5")
      (value "LED-Green(0603)")
      (fields
        (field (name "BOM_Manufacturer Part") "FC-DA1608UGK-520D10")
        (field (name "BOM_Supplier Part") "C84267")
      )
      (libsource (lib "") (part "Unknown_840_300"))
    )
    (comp (ref "LED6")
      (value "LED-Yellow(0603)")
      (fields
        (field (name "BOM_Manufacturer Part") "19-213/Y2C-CQ2R2L/3T(CY)")
        (field (name "BOM_Supplier Part") "C72038")
      )
      (libsource (lib "") (part "Unknown_950_365"))
    )
    (comp (ref "R1") (value "4k7") (libsource (lib "") (part "Res_0603(1/10W)_EU")))
    (comp (ref "R2") (value "1k") (libsource (lib "") (part "Res_0603(1/10W)_EU")))
    (comp (ref "R3") (value "1k") (libsource (lib "") (part "Res_0603(1/10W)_EU")))
    (comp (ref "R4") (value "1K") (libsource (lib "") (part "Res_0603(1/10W)_EU")))
    (comp (ref "R5") (value "1k") (libsource (lib "") (part "Res_0603(1/10W)_EU")))
    (comp (ref "R6") (value "1k") (libsource (lib "") (part "Res_0603(1/10W)_EU")))
    (comp (ref "C1")
      (value "100nF")
      (fields
        (field (name "BOM_Manufacturer Part") "CGA3E3X8R1H104KT0Y0N")
        (field (name "BOM_Supplier Part") "C342825")
      )
      (libsource (lib "") (part "CGA3E3X8R1H104KT0Y0N"))
    )
    (comp (ref "C30")
      (value "100nF")
      (fields
        (field (name "BOM_Manufacturer Part") "CGA3E3X8R1H104KT0Y0N")
        (field (name "BOM_Supplier Part") "C342825")
      )
      (libsource (lib "") (part "CGA3E3X8R1H104KT0Y0N"))
    )
    (comp (ref "C31")
      (value "100nF")
      (fields
        (field (name "BOM_Manufacturer Part") "CGA3E3X8R1H104KT0Y0N")
        (field (name "BOM_Supplier Part") "C342825")
      )
      (libsource (lib "") (part "CGA3E3X8R1H104KT0Y0N"))
    )
    (comp (ref "C32")
      (value "100nF")
      (fields
        (field (name "BOM_Manufacturer Part") "CGA3E3X8R1H104KT0Y0N")
        (field (name "BOM_Supplier Part") "C342825")
      )
      (libsource (lib "") (part "CGA3E3X8R1H104KT0Y0N"))
    )
    (comp (ref "C33")
      (value "100nF")
      (fields
        (field (name "BOM_Manufacturer Part") "CGA3E3X8R1H104KT0Y0N")
        (field (name "BOM_Supplier Part") "C342825")
      )
      (libsource (lib "") (part "CGA3E3X8R1H104KT0Y0N"))
    )
    (comp (ref "C34")
      (value "100nF")
      (fields
        (field (name "BOM_Manufacturer Part") "CGA3E3X8R1H104KT0Y0N")
        (field (name "BOM_Supplier Part") "C342825")
      )
      (libsource (lib "") (part "CGA3E3X8R1H104KT0Y0N"))
    )
    (comp (ref "C35")
      (value "10pF")
      (fields
        (field (name "BOM_Manufacturer Part") "CC0603GRNPO9BN100")
        (field (name "BOM_Supplier Part") "C325468")
      )
      (libsource (lib "") (part "CC0603GRNPO9BN100"))
    )
    (comp (ref "C36")
      (value "100nF")
      (fields
        (field (name "BOM_Manufacturer Part") "CGA3E3X8R1H104KT0Y0N")
        (field (name "BOM_Supplier Part") "C342825")
      )
      (libsource (lib "") (part "CGA3E3X8R1H104KT0Y0N"))
    )
    (comp (ref "C37")
      (value "100nF")
      (fields
        (field (name "BOM_Manufacturer Part") "CGA3E3X8R1H104KT0Y0N")
        (field (name "BOM_Supplier Part") "C342825")
      )
      (libsource (lib "") (part "CGA3E3X8R1H104KT0Y0N"))
    )
    (comp (ref "C38")
      (value "100nF")
      (fields
        (field (name "BOM_Manufacturer Part") "CGA3E3X8R1H104KT0Y0N")
        (field (name "BOM_Supplier Part") "C342825")
      )
      (libsource (lib "") (part "CGA3E3X8R1H104KT0Y0N"))
    )
    (comp (ref "C39")
      (value "10uF")
      (fields
        (field (name "BOM_Manufacturer Part") "CL21A106KAYNNNE")
        (field (name "BOM_Supplier Part") "C15850")
      )
      (libsource (lib "") (part "CL21A106KAYNNNE"))
    )
    (comp (ref "C40")
      (value "10uF")
      (fields
        (field (name "BOM_Manufacturer Part") "CL21A106KAYNNNE")
        (field (name "BOM_Supplier Part") "C15850")
      )
      (libsource (lib "") (part "CL21A106KAYNNNE"))
    )
    (comp (ref "C41")
      (value "100nF")
      (fields
        (field (name "BOM_Manufacturer Part") "CGA3E3X8R1H104KT0Y0N")
        (field (name "BOM_Supplier Part") "C342825")
      )
      (libsource (lib "") (part "CGA3E3X8R1H104KT0Y0N"))
    )
    (comp (ref "C42")
      (value "10uF")
      (fields
        (field (name "BOM_Manufacturer Part") "CL21A106KAYNNNE")
        (field (name "BOM_Supplier Part") "C15850")
      )
      (libsource (lib "") (part "CL21A106KAYNNNE"))
    )
    (comp (ref "C43")
      (value "4.7uF")
      (fields
        (field (name "BOM_Manufacturer Part") "C2012X7R1E475KT000N")
        (field (name "BOM_Supplier Part") "C76642")
      )
      (libsource (lib "") (part "C2012X7R1E475KT000N"))
    )
    (comp (ref "C44") (value "10p") (libsource (lib "") (part "Unknown_1880_1645")))
    (comp (ref "C45") (value "10p") (libsource (lib "") (part "Unknown_1795_1645")))
    (comp (ref "C46")
      (value "100nF")
      (fields
        (field (name "BOM_Manufacturer Part") "CGA3E3X8R1H104KT0Y0N")
        (field (name "BOM_Supplier Part") "C342825")
      )
      (libsource (lib "") (part "CGA3E3X8R1H104KT0Y0N"))
    )
    (comp (ref "C47")
      (value "100nF")
      (fields
        (field (name "BOM_Manufacturer Part") "CGA3E3X8R1H104KT0Y0N")
        (field (name "BOM_Supplier Part") "C342825")
      )
      (libsource (lib "") (part "CGA3E3X8R1H104KT0Y0N"))
    )
    (comp (ref "C48")
      (value "100nF")
      (fields
        (field (name "BOM_Manufacturer Part") "CGA3E3X8R1H104KT0Y0N")
        (field (name "BOM_Supplier Part") "C342825")
      )
      (libsource (lib "") (part "CGA3E3X8R1H104KT0Y0N"))
    )
    (comp (ref "C49")
      (value "100nF")
      (fields
        (field (name "BOM_Manufacturer Part") "CGA3E3X8R1H104KT0Y0N")
        (field (name "BOM_Supplier Part") "C342825")
      )
      (libsource (lib "") (part "CGA3E3X8R1H104KT0Y0N"))
    )
    (comp (ref "C50")
      (value "100nF")
      (fields
        (field (name "BOM_Manufacturer Part") "CGA3E3X8R1H104KT0Y0N")
        (field (name "BOM_Supplier Part") "C342825")
      )
      (libsource (lib "") (part "CGA3E3X8R1H104KT0Y0N"))
    )
    (comp (ref "C51")
      (value "100nF")
      (fields
        (field (name "BOM_Manufacturer Part") "CGA3E3X8R1H104KT0Y0N")
        (field (name "BOM_Supplier Part") "C342825")
      )
      (libsource (lib "") (part "CGA3E3X8R1H104KT0Y0N"))
    )
    (comp (ref "C52")
      (value "2.2uF")
      (fields
        (field (name "BOM_Manufacturer Part") "CL21B225KAFNFNE")
        (field (name "BOM_Supplier Part") "C364318")
      )
      (libsource (lib "") (part "CL21B225KAFNFNE"))
    )
    (comp (ref "C53")
      (value "10uF")
      (fields
        (field (name "BOM_Manufacturer Part") "CL21A106KAYNNNE")
        (field (name "BOM_Supplier Part") "C15850")
      )
      (libsource (lib "") (part "CL21A106KAYNNNE"))
    )
    (comp (ref "D25") (value "SOD-523F") (libsource (lib "") (part "Unknown_1825_1380")))
    (comp (ref "F4")
      (value "FSMD020-1206-R")
      (fields (field (name "BOM_Supplier Part") "C220145"))
      (libsource (lib "") (part "Unknown_1425_1630"))
    )
    (comp (ref "J21") (value "JTAG") (libsource (lib "") (part "Unknown_2230_1420")))
    (comp (ref "JP1") (value "ERASE") (libsource (lib "") (part "Unknown_2090_1385")))
    (comp (ref "L5") (value "10uH 100Mhz") (libsource (lib "") (part "Unknown_1495_345")))
    (comp (ref "L6") (value "10uH 100Mhz") (libsource (lib "") (part "Unknown_1550_385")))
    (comp (ref "R9") (value "22R") (libsource (lib "") (part "Res_0603(1/10W)_EU")))
    (comp (ref "R10") (value "22R") (libsource (lib "") (part "Res_0603(1/10W)_EU")))
    (comp (ref "R11") (value "2k2") (libsource (lib "") (part "Res_0603(1/10W)_EU_1")))
    (comp (ref "R12") (value "2k2") (libsource (lib "") (part "Res_0603(1/10W)_EU_1")))
    (comp (ref "R56") (value "1R") (libsource (lib "") (part "Unknown_1570_430")))
    (comp (ref "R57") (value "DNP 100K") (libsource (lib "") (part "Unknown_2285_1370")))
    (comp (ref "R58") (value "DNP 100K") (libsource (lib "") (part "Unknown_2335_1370")))
    (comp (ref "R59") (value "DNP 100K") (libsource (lib "") (part "Unknown_2360_1370")))
    (comp (ref "R83") (value "10K") (libsource (lib "") (part "Unknown_2480_1355")))
    (comp (ref "R106") (value "10K") (libsource (lib "") (part "Unknown_1760_1340")))
    (comp (ref "S1") (value "RESET") (libsource (lib "") (part "Unknown_1860_1430")))
    (comp (ref "U1") (value "ATSAME70Q21B-ANT") (libsource (lib "") (part "Unknown_1510_1130")))
    (comp (ref "X2") (value "CRYSTAL_4PIN") (libsource (lib "") (part "Unknown_1835_1610")))
    (comp (ref "EXP1")
      (value "HDR-IDC-2.54-2X5P")
      (fields
        (field (name "BOM_Manufacturer Part") "IDC Box 2.54mm 2X5P")
        (field (name "BOM_Supplier Part") "C5665")
      )
      (libsource (lib "") (part "Unknown_170_180"))
    )
    (comp (ref "EXP2")
      (value "HDR-IDC-2.54-2X5P")
      (fields
        (field (name "BOM_Manufacturer Part") "IDC Box 2.54mm 2X5P")
        (field (name "BOM_Supplier Part") "C5665")
      )
      (libsource (lib "") (part "Unknown_610_175"))
    )
    (comp (ref "EXP3")
      (value "HDR-IDC-2.54-2X7P")
      (fields
        (field (name "BOM_Manufacturer Part") "2X7 2.54mm IDC Box")
        (field (name "BOM_Supplier Part") "C11215")
      )
      (libsource (lib "") (part "Unknown_170_385"))
    )
    (comp (ref "P8")
      (value "PS_ON")
      (fields
        (field (name "BOM_Manufacturer Part") "2.54mm 1*2P")
        (field (name "BOM_Supplier Part") "C36717")
      )
      (libsource (lib "") (part "Unknown_400_550"))
    )
    (comp (ref "ENC_1")
      (value "Header-Male-2.54_1x4_C59481")
      (fields
        (field (name "BOM_Manufacturer Part") "Headers  Pins 1*4P")
        (field (name "BOM_Supplier Part") "C59481")
      )
      (libsource (lib "") (part "Unknown_410_360"))
    )
    (comp (ref "ENC_2")
      (value "Header-Male-2.54_1x4_C59481")
      (fields
        (field (name "BOM_Manufacturer Part") "Headers  Pins 1*4P")
        (field (name "BOM_Supplier Part") "C59481")
      )
      (libsource (lib "") (part "Unknown_410_430"))
    )
    (comp (ref "ENC_3")
      (value "Header-Male-2.54_1x4_C59481")
      (fields
        (field (name "BOM_Manufacturer Part") "Headers  Pins 1*4P")
        (field (name "BOM_Supplier Part") "C59481")
      )
      (libsource (lib "") (part "Unknown_410_500"))
    )
    (comp (ref "ENC_4")
      (value "Header-Male-2.54_1x4_C59481")
      (fields
        (field (name "BOM_Manufacturer Part") "Headers  Pins 1*4P")
        (field (name "BOM_Supplier Part") "C59481")
      )
      (libsource (lib "") (part "Unknown_410_570"))
    )
    (comp (ref "X+")
      (value "XH-3A")
      (fields (field (name "BOM_Supplier Part") "C2316"))
      (libsource (lib "") (part "Unknown_375_520"))
    )
    (comp (ref "X-")
      (value "XH-3A")
      (fields (field (name "BOM_Supplier Part") "C2316"))
      (libsource (lib "") (part "Unknown_375_465"))
    )
    (comp (ref "Y+")
      (value "XH-3A")
      (fields (field (name "BOM_Supplier Part") "C2316"))
      (libsource (lib "") (part "Unknown_375_410"))
    )
    (comp (ref "Y-")
      (value "XH-3A")
      (fields (field (name "BOM_Supplier Part") "C2316"))
      (libsource (lib "") (part "Unknown_375_355"))
    )
    (comp (ref "Z+")
      (value "XH-3A")
      (fields (field (name "BOM_Supplier Part") "C2316"))
      (libsource (lib "") (part "Unknown_375_300"))
    )
    (comp (ref "Z-")
      (value "XH-3A")
      (fields (field (name "BOM_Supplier Part") "C2316"))
      (libsource (lib "") (part "Unknown_375_245"))
    )
    (comp (ref "D2")
      (value "S2BA-13-F")
      (fields (field (name "BOM_Supplier Part") "C150463"))
      (libsource (lib "") (part "Unknown_215_180"))
    )
    (comp (ref "D3")
      (value "S2BA-13-F")
      (fields (field (name "BOM_Supplier Part") "C150463"))
      (libsource (lib "") (part "Unknown_570_185"))
    )
    (comp (ref "D4")
      (value "S2BA-13-F")
      (fields (field (name "BOM_Supplier Part") "C150463"))
      (libsource (lib "") (part "Unknown_910_190"))
    )
    (comp (ref "H3")
      (value "VFAN1_SELECTOR")
      (fields
        (field (name "BOM_Manufacturer Part") "Header2.54mm 1*3P")
        (field (name "BOM_Supplier Part") "C49257")
      )
      (libsource (lib "") (part "Unknown_970_105"))
    )
    (comp (ref "LED7")
      (value "LED-Green(0603)")
      (fields
        (field (name "BOM_Manufacturer Part") "FC-DA1608UGK-520D10")
        (field (name "BOM_Supplier Part") "C84267")
      )
      (libsource (lib "") (part "Unknown_100_345"))
    )
    (comp (ref "LED8")
      (value "LED-Green(0603)")
      (fields
        (field (name "BOM_Manufacturer Part") "FC-DA1608UGK-520D10")
        (field (name "BOM_Supplier Part") "C84267")
      )
      (libsource (lib "") (part "Unknown_455_350"))
    )
    (comp (ref "LED9")
      (value "LED-Green(0603)")
      (fields
        (field (name "BOM_Manufacturer Part") "FC-DA1608UGK-520D10")
        (field (name "BOM_Supplier Part") "C84267")
      )
      (libsource (lib "") (part "Unknown_795_355"))
    )
    (comp (ref "Q1") (value "BUK9Y14-40B") (libsource (lib "") (part "PH7030L")))
    (comp (ref "Q2") (value "BUK9Y14-40B") (libsource (lib "") (part "PH7030L")))
    (comp (ref "Q3") (value "BUK9Y14-40B") (libsource (lib "") (part "PH7030L")))
    (comp (ref "R14") (value "1K") (libsource (lib "") (part "Res_0603(1/10W)_EU")))
    (comp (ref "R15") (value "22R") (libsource (lib "") (part "Res_0603(1/10W)_EU_1")))
    (comp (ref "R16") (value "100K") (libsource (lib "") (part "Res_0603(1/10W)_EU_1")))
    (comp (ref "R17") (value "100K") (libsource (lib "") (part "Res_0603(1/10W)_EU_1")))
    (comp (ref "R18") (value "22R") (libsource (lib "") (part "Res_0603(1/10W)_EU_1")))
    (comp (ref "R19") (value "1K") (libsource (lib "") (part "Res_0603(1/10W)_EU")))
    (comp (ref "R20") (value "100K") (libsource (lib "") (part "Res_0603(1/10W)_EU_1")))
    (comp (ref "R21") (value "22R") (libsource (lib "") (part "Res_0603(1/10W)_EU_1")))
    (comp (ref "R22") (value "1K") (libsource (lib "") (part "Res_0603(1/10W)_EU")))
    (comp (ref "U3")
      (value "HE0")
      (fields (field (name "BOM_Manufacturer Part") "2-pin terminal"))
      (libsource (lib "") (part "Unknown_300_160"))
    )
    (comp (ref "U4")
      (value "HE1")
      (fields (field (name "BOM_Manufacturer Part") "2-pin terminal"))
      (libsource (lib "") (part "Unknown_655_165"))
    )
    (comp (ref "U5")
      (value "HE2")
      (fields (field (name "BOM_Manufacturer Part") "2-pin terminal"))
      (libsource (lib "") (part "Unknown_995_170"))
    )
    (comp (ref "C54") (value "2u2") (libsource (lib "") (part "Unknown_450_445")))
    (comp (ref "C55") (value "2u2") (libsource (lib "") (part "Unknown_475_445")))
    (comp (ref "C56") (value "2u2") (libsource (lib "") (part "Unknown_500_445")))
    (comp (ref "C59") (value "2u2") (libsource (lib "") (part "Unknown_525_445")))
    (comp (ref "C60") (value "2u2") (libsource (lib "") (part "Unknown_550_445")))
    (comp (ref "P9")
      (value "XH-2A")
      (fields (field (name "BOM_Supplier Part") "C20079"))
      (libsource (lib "") (part "Unknown_805_330"))
    )
    (comp (ref "P10")
      (value "XH-2A")
      (fields (field (name "BOM_Supplier Part") "C20079"))
      (libsource (lib "") (part "Unknown_805_250"))
    )
    (comp (ref "P11")
      (value "XH-2A")
      (fields (field (name "BOM_Supplier Part") "C20079"))
      (libsource (lib "") (part "Unknown_805_185"))
    )
    (comp (ref "P12")
      (value "XH-2A")
      (fields (field (name "BOM_Supplier Part") "C20079"))
      (libsource (lib "") (part "Unknown_805_110"))
    )
    (comp (ref "P13")
      (value "XH-2A")
      (fields (field (name "BOM_Supplier Part") "C20079"))
      (libsource (lib "") (part "Unknown_805_415"))
    )
    (comp (ref "R7") (value "4K7 0.1%") (libsource (lib "") (part "Unknown_300_190")))
    (comp (ref "R8") (value "4K7 0.1%") (libsource (lib "") (part "Unknown_225_190")))
    (comp (ref "R61") (value "4K7 0.1%") (libsource (lib "") (part "Unknown_250_190")))
    (comp (ref "R62") (value "4K7 0.1%") (libsource (lib "") (part "Unknown_275_190")))
    (comp (ref "R65") (value "10K") (libsource (lib "") (part "Unknown_400_285")))
    (comp (ref "R66") (value "10K") (libsource (lib "") (part "Unknown_400_300")))
    (comp (ref "R67") (value "10K") (libsource (lib "") (part "Unknown_400_315")))
    (comp (ref "R69") (value "4K7 0.1%") (libsource (lib "") (part "Unknown_325_190")))
    (comp (ref "R70") (value "10K") (libsource (lib "") (part "Unknown_400_270")))
    (comp (ref "R71") (value "10K") (libsource (lib "") (part "Unknown_400_255")))
    (comp (ref "C7")
      (value "100nF")
      (fields
        (field (name "BOM_Manufacturer Part") "CGA3E3X8R1H104KT0Y0N")
        (field (name "BOM_Supplier Part") "C342825")
      )
      (libsource (lib "") (part "CGA3E3X8R1H104KT0Y0N"))
    )
    (comp (ref "U2")
      (value "BL24C16A-RRRC")
      (fields (field (name "BOM_Supplier Part") "C191945"))
      (libsource (lib "") (part "Unknown_505_395"))
    )
    (comp (ref "C8")
      (value "1uF")
      (fields
        (field (name "BOM_Manufacturer Part") "CL10B105KO8NNNC")
        (field (name "BOM_Supplier Part") "C59782")
      )
      (libsource (lib "") (part "CL10B105KO8NNNC"))
    )
    (comp (ref "D5")
      (value "S2BA-13-F")
      (fields (field (name "BOM_Supplier Part") "C150463"))
      (libsource (lib "") (part "Unknown_695_280"))
    )
    (comp (ref "LED10")
      (value "LED-Green(0603)")
      (fields
        (field (name "BOM_Manufacturer Part") "FC-DA1608UGK-520D10")
        (field (name "BOM_Supplier Part") "C84267")
      )
      (libsource (lib "") (part "Unknown_415_435"))
    )
    (comp (ref "Q4") (value "PSMN1R8-40YLC") (libsource (lib "") (part "PH7030L")))
    (comp (ref "R23") (value "22R") (libsource (lib "") (part "Res_0603(1/10W)_EU")))
    (comp (ref "R24") (value "100K") (libsource (lib "") (part "Res_0603(1/10W)_EU_2")))
    (comp (ref "R25") (value "1K") (libsource (lib "") (part "Res_0603(1/10W)_EU_1")))
    (comp (ref "U6")
      (value "74LVC1G17SE-7")
      (fields (field (name "BOM_Supplier Part") "C212314"))
      (libsource (lib "") (part "Unknown_575_360"))
    )
    (comp (ref "U7")
      (value "HB")
      (fields (field (name "BOM_Manufacturer Part") "2-pin terminal"))
      (libsource (lib "") (part "Unknown_805_275"))
    )
    (comp (ref "D6")
      (value "S2BA-13-F")
      (fields (field (name "BOM_Supplier Part") "C150463"))
      (libsource (lib "") (part "Unknown_300_330"))
    )
    (comp (ref "D7")
      (value "S2BA-13-F")
      (fields (field (name "BOM_Supplier Part") "C150463"))
      (libsource (lib "") (part "Unknown_770_310"))
    )
    (comp (ref "H1")
      (value "VFAN0_SELECTOR")
      (fields
        (field (name "BOM_Manufacturer Part") "Header2.54mm 1*3P")
        (field (name "BOM_Supplier Part") "C49257")
      )
      (libsource (lib "") (part "Unknown_360_245"))
    )
    (comp (ref "H2")
      (value "VFAN1_SELECTOR")
      (fields
        (field (name "BOM_Manufacturer Part") "Header2.54mm 1*3P")
        (field (name "BOM_Supplier Part") "C49257")
      )
      (libsource (lib "") (part "Unknown_830_225"))
    )
    (comp (ref "LED11")
      (value "LED-Green(0603)")
      (fields
        (field (name "BOM_Manufacturer Part") "FC-DA1608UGK-520D10")
        (field (name "BOM_Supplier Part") "C84267")
      )
      (libsource (lib "") (part "Unknown_185_495"))
    )
    (comp (ref "LED12")
      (value "LED-Green(0603)")
      (fields
        (field (name "BOM_Manufacturer Part") "FC-DA1608UGK-520D10")
        (field (name "BOM_Supplier Part") "C84267")
      )
      (libsource (lib "") (part "Unknown_655_475"))
    )
    (comp (ref "P6")
      (value "FAN_0 HEAD")
      (fields
        (field (name "BOM_Manufacturer Part") "2.54mm 1*2P")
        (field (name "BOM_Supplier Part") "C36717")
      )
      (libsource (lib "") (part "Unknown_425_380"))
    )
    (comp (ref "P7")
      (value "FAN_1 HEAD")
      (fields
        (field (name "BOM_Manufacturer Part") "2.54mm 1*2P")
        (field (name "BOM_Supplier Part") "C36717")
      )
      (libsource (lib "") (part "Unknown_895_360"))
    )
    (comp (ref "Q5") (value "BUK9Y14-40B") (libsource (lib "") (part "PH7030L")))
    (comp (ref "Q6") (value "BUK9Y14-40B") (libsource (lib "") (part "PH7030L")))
    (comp (ref "R26") (value "1K") (libsource (lib "") (part "Res_0603(1/10W)_EU_1")))
    (comp (ref "R27") (value "22R") (libsource (lib "") (part "Res_0603(1/10W)_EU")))
    (comp (ref "R28") (value "100K") (libsource (lib "") (part "Res_0603(1/10W)_EU")))
    (comp (ref "R29") (value "100K") (libsource (lib "") (part "Res_0603(1/10W)_EU")))
    (comp (ref "R30") (value "22R") (libsource (lib "") (part "Res_0603(1/10W)_EU")))
    (comp (ref "R31") (value "1K") (libsource (lib "") (part "Res_0603(1/10W)_EU_1")))
    (comp (ref "U8")
      (value "FAN0")
      (fields (field (name "BOM_Manufacturer Part") "2-pin terminal"))
      (libsource (lib "") (part "Unknown_385_310"))
    )
    (comp (ref "U9")
      (value "FAN1")
      (fields (field (name "BOM_Manufacturer Part") "2-pin terminal"))
      (libsource (lib "") (part "Unknown_855_290"))
    )
    (comp (ref "C9")
      (value "100uF")
      (fields
        (field (name "BOM_Manufacturer Part") "EEEFT1V101AP")
        (field (name "BOM_Supplier Part") "C128464")
      )
      (libsource (lib "") (part "EEEFT1V101AP"))
    )
    (comp (ref "D8")
      (value "S2BA-13-F")
      (fields (field (name "BOM_Supplier Part") "C150463"))
      (libsource (lib "") (part "Unknown_250_180"))
    )
    (comp (ref "D9")
      (value "40V 4A")
      (fields
        (field (name "BOM_Manufacturer Part") "SSB44-E3/52T")
        (field (name "BOM_Supplier Part") "SSB44-E3/52TGICT-ND")
      )
      (libsource (lib "") (part "Unknown_650_375"))
    )
    (comp (ref "D10")
      (value "40V 4A")
      (fields
        (field (name "BOM_Manufacturer Part") "SSB44-E3/52T")
        (field (name "BOM_Supplier Part") "SSB44-E3/52TGICT-ND")
      )
      (libsource (lib "") (part "Unknown_650_420"))
    )
    (comp (ref "D11")
      (value "S2BA-13-F")
      (fields (field (name "BOM_Supplier Part") "C150463"))
      (libsource (lib "") (part "Unknown_205_400"))
    )
    (comp (ref "F1") (value "BED FUSE") (libsource (lib "") (part "Unknown_205_150")))
    (comp (ref "F2") (value "BED FUSE") (libsource (lib "") (part "Unknown_175_355")))
    (comp (ref "J1") (value "JUMPER_1X3") (libsource (lib "") (part "Unknown_900_410")))
    (comp (ref "P1")
      (value "PWR")
      (fields
        (field (name "BOM_Manufacturer Part") "2.54mm 1*2P")
        (field (name "BOM_Supplier Part") "C36717")
      )
      (libsource (lib "") (part "Unknown_370_165"))
    )
    (comp (ref "P2")
      (value "12V")
      (fields
        (field (name "BOM_Manufacturer Part") "2.54mm 1*2P")
        (field (name "BOM_Supplier Part") "C36717")
      )
      (libsource (lib "") (part "Unknown_490_165"))
    )
    (comp (ref "P3")
      (value "5V")
      (fields
        (field (name "BOM_Manufacturer Part") "2.54mm 1*2P")
        (field (name "BOM_Supplier Part") "C36717")
      )
      (libsource (lib "") (part "Unknown_600_165"))
    )
    (comp (ref "P4")
      (value "3V3")
      (fields
        (field (name "BOM_Manufacturer Part") "2.54mm 1*2P")
        (field (name "BOM_Supplier Part") "C36717")
      )
      (libsource (lib "") (part "Unknown_705_165"))
    )
    (comp (ref "U10")
      (value "HB")
      (fields (field (name "BOM_Manufacturer Part") "2-pin terminal"))
      (libsource (lib "") (part "Unknown_120_175"))
    )
    (comp (ref "U15")
      (value "MAIN-PWR")
      (fields (field (name "BOM_Manufacturer Part") "2-pin terminal"))
      (libsource (lib "") (part "Unknown_115_365"))
    )
    (comp (ref "C22")
      (value "100uF")
      (fields
        (field (name "BOM_Manufacturer Part") "EEEFT1V101AP")
        (field (name "BOM_Supplier Part") "C128464")
      )
      (libsource (lib "") (part "EEEFT1V101AP"))
    )
    (comp (ref "C23")
      (value "100uF")
      (fields
        (field (name "BOM_Manufacturer Part") "EEEFT1V101AP")
        (field (name "BOM_Supplier Part") "C128464")
      )
      (libsource (lib "") (part "EEEFT1V101AP"))
    )
    (comp (ref "C24")
      (value "100uF")
      (fields
        (field (name "BOM_Manufacturer Part") "EEEFT1V101AP")
        (field (name "BOM_Supplier Part") "C128464")
      )
      (libsource (lib "") (part "EEEFT1V101AP"))
    )
    (comp (ref "C25")
      (value "100uF")
      (fields
        (field (name "BOM_Manufacturer Part") "EEEFT1V101AP")
        (field (name "BOM_Supplier Part") "C128464")
      )
      (libsource (lib "") (part "EEEFT1V101AP"))
    )
    (comp (ref "C26")
      (value "100uF")
      (fields
        (field (name "BOM_Manufacturer Part") "EEEFT1V101AP")
        (field (name "BOM_Supplier Part") "C128464")
      )
      (libsource (lib "") (part "EEEFT1V101AP"))
    )
    (comp (ref "C27")
      (value "100uF")
      (fields
        (field (name "BOM_Manufacturer Part") "EEEFT1V101AP")
        (field (name "BOM_Supplier Part") "C128464")
      )
      (libsource (lib "") (part "EEEFT1V101AP"))
    )
    (comp (ref "E0_MOT_A")
      (value "Header-Male-2.54_1x4_C59481")
      (fields
        (field (name "BOM_Manufacturer Part") "Headers  Pins 1*4P")
        (field (name "BOM_Supplier Part") "C59481")
      )
      (libsource (lib "") (part "Unknown_550_985"))
    )
    (comp (ref "E1_MOT_A")
      (value "Header-Male-2.54_1x4_C59481")
      (fields
        (field (name "BOM_Manufacturer Part") "Headers  Pins 1*4P")
        (field (name "BOM_Supplier Part") "C59481")
      )
      (libsource (lib "") (part "Unknown_1250_960"))
    )
    (comp (ref "E2_MOT_A")
      (value "Header-Male-2.54_1x4_C59481")
      (fields
        (field (name "BOM_Manufacturer Part") "Headers  Pins 1*4P")
        (field (name "BOM_Supplier Part") "C59481")
      )
      (libsource (lib "") (part "Unknown_1920_945"))
    )
    (comp (ref "H5")
      (value "X-MS1")
      (fields
        (field (name "BOM_Manufacturer Part") "Header2.54mm 1*3P")
        (field (name "BOM_Supplier Part") "C49257")
      )
      (libsource (lib "") (part "Unknown_215_265"))
    )
    (comp (ref "H6")
      (value "X_MS2")
      (fields
        (field (name "BOM_Manufacturer Part") "Header2.54mm 1*3P")
        (field (name "BOM_Supplier Part") "C49257")
      )
      (libsource (lib "") (part "Unknown_210_345"))
    )
    (comp (ref "H7")
      (value "X_MS3")
      (fields
        (field (name "BOM_Manufacturer Part") "Header2.54mm 1*3P")
        (field (name "BOM_Supplier Part") "C49257")
      )
      (libsource (lib "") (part "Unknown_190_430"))
    )
    (comp (ref "H8")
      (value "X_RST")
      (fields
        (field (name "BOM_Manufacturer Part") "Header2.54mm 1*3P")
        (field (name "BOM_Supplier Part") "C49257")
      )
      (libsource (lib "") (part "Unknown_160_530"))
    )
    (comp (ref "H9")
      (value "Y_RST")
      (fields
        (field (name "BOM_Manufacturer Part") "Header2.54mm 1*3P")
        (field (name "BOM_Supplier Part") "C49257")
      )
      (libsource (lib "") (part "Unknown_865_545"))
    )
    (comp (ref "H10")
      (value "Y_MS3")
      (fields
        (field (name "BOM_Manufacturer Part") "Header2.54mm 1*3P")
        (field (name "BOM_Supplier Part") "C49257")
      )
      (libsource (lib "") (part "Unknown_895_445"))
    )
    (comp (ref "H11")
      (value "Y_MS2")
      (fields
        (field (name "BOM_Manufacturer Part") "Header2.54mm 1*3P")
        (field (name "BOM_Supplier Part") "C49257")
      )
      (libsource (lib "") (part "Unknown_915_360"))
    )
    (comp (ref "H12")
      (value "Y-MS1")
      (fields
        (field (name "BOM_Manufacturer Part") "Header2.54mm 1*3P")
        (field (name "BOM_Supplier Part") "C49257")
      )
      (libsource (lib "") (part "Unknown_920_280"))
    )
    (comp (ref "H13")
      (value "Z-MS1")
      (fields
        (field (name "BOM_Manufacturer Part") "Header2.54mm 1*3P")
        (field (name "BOM_Supplier Part") "C49257")
      )
      (libsource (lib "") (part "Unknown_1550_270"))
    )
    (comp (ref "H14")
      (value "Z_MS2")
      (fields
        (field (name "BOM_Manufacturer Part") "Header2.54mm 1*3P")
        (field (name "BOM_Supplier Part") "C49257")
      )
      (libsource (lib "") (part "Unknown_1545_350"))
    )
    (comp (ref "H15")
      (value "Z_MS3")
      (fields
        (field (name "BOM_Manufacturer Part") "Header2.54mm 1*3P")
        (field (name "BOM_Supplier Part") "C49257")
      )
      (libsource (lib "") (part "Unknown_1525_435"))
    )
    (comp (ref "H16")
      (value "Z_RST")
      (fields
        (field (name "BOM_Manufacturer Part") "Header2.54mm 1*3P")
        (field (name "BOM_Supplier Part") "C49257")
      )
      (libsource (lib "") (part "Unknown_1495_535"))
    )
    (comp (ref "H17")
      (value "E0-MS1")
      (fields
        (field (name "BOM_Manufacturer Part") "Header2.54mm 1*3P")
        (field (name "BOM_Supplier Part") "C49257")
      )
      (libsource (lib "") (part "Unknown_230_890"))
    )
    (comp (ref "H18")
      (value "E0_MS2")
      (fields
        (field (name "BOM_Manufacturer Part") "Header2.54mm 1*3P")
        (field (name "BOM_Supplier Part") "C49257")
      )
      (libsource (lib "") (part "Unknown_225_970"))
    )
    (comp (ref "H19")
      (value "E0_MS3")
      (fields
        (field (name "BOM_Manufacturer Part") "Header2.54mm 1*3P")
        (field (name "BOM_Supplier Part") "C49257")
      )
      (libsource (lib "") (part "Unknown_205_1055"))
    )
    (comp (ref "H20")
      (value "E0_RST")
      (fields
        (field (name "BOM_Manufacturer Part") "Header2.54mm 1*3P")
        (field (name "BOM_Supplier Part") "C49257")
      )
      (libsource (lib "") (part "Unknown_175_1155"))
    )
    (comp (ref "H21")
      (value "E1-MS1")
      (fields
        (field (name "BOM_Manufacturer Part") "Header2.54mm 1*3P")
        (field (name "BOM_Supplier Part") "C49257")
      )
      (libsource (lib "") (part "Unknown_930_865"))
    )
    (comp (ref "H22")
      (value "E1_MS2")
      (fields
        (field (name "BOM_Manufacturer Part") "Header2.54mm 1*3P")
        (field (name "BOM_Supplier Part") "C49257")
      )
      (libsource (lib "") (part "Unknown_925_945"))
    )
    (comp (ref "H23")
      (value "E1_MS3")
      (fields
        (field (name "BOM_Manufacturer Part") "Header2.54mm 1*3P")
        (field (name "BOM_Supplier Part") "C49257")
      )
      (libsource (lib "") (part "Unknown_905_1030"))
    )
    (comp (ref "H24")
      (value "E1_RST")
      (fields
        (field (name "BOM_Manufacturer Part") "Header2.54mm 1*3P")
        (field (name "BOM_Supplier Part") "C49257")
      )
      (libsource (lib "") (part "Unknown_875_1130"))
    )
    (comp (ref "H25")
      (value "E2-MS1")
      (fields
        (field (name "BOM_Manufacturer Part") "Header2.54mm 1*3P")
        (field (name "BOM_Supplier Part") "C49257")
      )
      (libsource (lib "") (part "Unknown_1600_850"))
    )
    (comp (ref "H26")
      (value "E2_MS2")
      (fields
        (field (name "BOM_Manufacturer Part") "Header2.54mm 1*3P")
        (field (name "BOM_Supplier Part") "C49257")
      )
      (libsource (lib "") (part "Unknown_1595_930"))
    )
    (comp (ref "H27")
      (value "E2_MS3")
      (fields
        (field (name "BOM_Manufacturer Part") "Header2.54mm 1*3P")
        (field (name "BOM_Supplier Part") "C49257")
      )
      (libsource (lib "") (part "Unknown_1575_1015"))
    )
    (comp (ref "H28")
      (value "E2_RST")
      (fields
        (field (name "BOM_Manufacturer Part") "Header2.54mm 1*3P")
        (field (name "BOM_Supplier Part") "C49257")
      )
      (libsource (lib "") (part "Unknown_1545_1115"))
    )
    (comp (ref "R13") (value "100K") (libsource (lib "") (part "Res_0603(1/10W)_EU")))
    (comp (ref "R38") (value "10K") (libsource (lib "") (part "Res_0603(1/10W)_EU")))
    (comp (ref "R39") (value "10K") (libsource (lib "") (part "Res_0603(1/10W)_EU")))
    (comp (ref "R40") (value "10K") (libsource (lib "") (part "Res_0603(1/10W)_EU")))
    (comp (ref "R41") (value "10K") (libsource (lib "") (part "Res_0603(1/10W)_EU")))
    (comp (ref "R42") (value "10K") (libsource (lib "") (part "Res_0603(1/10W)_EU")))
    (comp (ref "R43") (value "10K") (libsource (lib "") (part "Res_0603(1/10W)_EU")))
    (comp (ref "R51") (value "100K") (libsource (lib "") (part "Res_0603(1/10W)_EU")))
    (comp (ref "R72") (value "100K") (libsource (lib "") (part "Res_0603(1/10W)_EU")))
    (comp (ref "R80") (value "100K") (libsource (lib "") (part "Res_0603(1/10W)_EU")))
    (comp (ref "R81") (value "100K") (libsource (lib "") (part "Res_0603(1/10W)_EU")))
    (comp (ref "R84") (value "100K") (libsource (lib "") (part "Res_0603(1/10W)_EU")))
    (comp (ref "U23")
      (value "X")
      (fields (field (name "BOM_Manufacturer Part") "A4988") (field (name "BOM_Supplier Part") "34059"))
      (libsource (lib "") (part "Unknown_425_375"))
    )
    (comp (ref "U24")
      (value "Y")
      (fields (field (name "BOM_Manufacturer Part") "A4988") (field (name "BOM_Supplier Part") "34059"))
      (libsource (lib "") (part "Unknown_1130_390"))
    )
    (comp (ref "U25")
      (value "Z")
      (fields (field (name "BOM_Manufacturer Part") "A4988") (field (name "BOM_Supplier Part") "34059"))
      (libsource (lib "") (part "Unknown_1760_380"))
    )
    (comp (ref "U26")
      (value "E0")
      (fields (field (name "BOM_Manufacturer Part") "A4988") (field (name "BOM_Supplier Part") "34059"))
      (libsource (lib "") (part "Unknown_440_1000"))
    )
    (comp (ref "U27")
      (value "E1")
      (fields (field (name "BOM_Manufacturer Part") "A4988") (field (name "BOM_Supplier Part") "34059"))
      (libsource (lib "") (part "Unknown_1140_975"))
    )
    (comp (ref "U28")
      (value "E2")
      (fields (field (name "BOM_Manufacturer Part") "A4988") (field (name "BOM_Supplier Part") "34059"))
      (libsource (lib "") (part "Unknown_1810_960"))
    )
    (comp (ref "X_MOT_A")
      (value "Header-Male-2.54_1x4_C59481")
      (fields
        (field (name "BOM_Manufacturer Part") "Headers  Pins 1*4P")
        (field (name "BOM_Supplier Part") "C59481")
      )
      (libsource (lib "") (part "Unknown_665_360"))
    )
    (comp (ref "Y_MOT_A")
      (value "Header-Male-2.54_1x4_C59481")
      (fields
        (field (name "BOM_Manufacturer Part") "Headers  Pins 1*4P")
        (field (name "BOM_Supplier Part") "C59481")
      )
      (libsource (lib "") (part "Unknown_1240_375"))
    )
    (comp (ref "Z_MOT_A")
      (value "Header-Male-2.54_1x4_C59481")
      (fields
        (field (name "BOM_Manufacturer Part") "Headers  Pins 1*4P")
        (field (name "BOM_Supplier Part") "C59481")
      )
      (libsource (lib "") (part "Unknown_1870_365"))
    )
    (comp (ref "C10")
      (value "4.7uF")
      (fields
        (field (name "BOM_Manufacturer Part") "C1210X475K101T")
        (field (name "BOM_Supplier Part") "C337978")
      )
      (libsource (lib "") (part "C1210X475K101T"))
    )
    (comp (ref "C11")
      (value "100nF")
      (fields
        (field (name "BOM_Manufacturer Part") "CGA3E3X8R1H104KT0Y0N")
        (field (name "BOM_Supplier Part") "C342825")
      )
      (libsource (lib "") (part "CGA3E3X8R1H104KT0Y0N_2"))
    )
    (comp (ref "C12")
      (value "4.7uF")
      (fields (field (name "BOM_Supplier Part") "445-1604-1-ND"))
      (libsource (lib "") (part "Unknown_450_155"))
    )
    (comp (ref "C13")
      (value "100uF")
      (fields
        (field (name "BOM_Manufacturer Part") "EEEFT1V101AP")
        (field (name "BOM_Supplier Part") "C128464")
      )
      (libsource (lib "") (part "EEEFT1V101AP"))
    )
    (comp (ref "C14")
      (value "4.7uF")
      (fields (field (name "BOM_Supplier Part") "445-1604-1-ND"))
      (libsource (lib "") (part "Unknown_755_330"))
    )
    (comp (ref "C15")
      (value "4.7uF")
      (fields (field (name "BOM_Supplier Part") "445-1604-1-ND"))
      (libsource (lib "") (part "Unknown_935_330"))
    )
    (comp (ref "C16")
      (value "100nF")
      (fields
        (field (name "BOM_Manufacturer Part") "CGA3E3X8R1H104KT0Y0N")
        (field (name "BOM_Supplier Part") "C342825")
      )
      (libsource (lib "") (part "CGA3E3X8R1H104KT0Y0N_1"))
    )
    (comp (ref "C17")
      (value "100nF")
      (fields
        (field (name "BOM_Manufacturer Part") "CGA3E3X8R1H104KT0Y0N")
        (field (name "BOM_Supplier Part") "C342825")
      )
      (libsource (lib "") (part "CGA3E3X8R1H104KT0Y0N_1"))
    )
    (comp (ref "C18")
      (value "4.7uF")
      (fields
        (field (name "BOM_Manufacturer Part") "C1210X475K101T")
        (field (name "BOM_Supplier Part") "C337978")
      )
      (libsource (lib "") (part "C1210X475K101T"))
    )
    (comp (ref "C19")
      (value "100nF")
      (fields
        (field (name "BOM_Manufacturer Part") "CGA3E3X8R1H104KT0Y0N")
        (field (name "BOM_Supplier Part") "C342825")
      )
      (libsource (lib "") (part "CGA3E3X8R1H104KT0Y0N"))
    )
    (comp (ref "C20")
      (value "4.7uF")
      (fields
        (field (name "BOM_Manufacturer Part") "C1210X475K101T")
        (field (name "BOM_Supplier Part") "C337978")
      )
      (libsource (lib "") (part "C1210X475K101T"))
    )
    (comp (ref "C21")
      (value "100uF")
      (fields
        (field (name "BOM_Manufacturer Part") "EEEFT1V101AP")
        (field (name "BOM_Supplier Part") "C128464")
      )
      (libsource (lib "") (part "EEEFT1V101AP"))
    )
    (comp (ref "D12")
      (value "SS24FL")
      (fields (field (name "BOM_Supplier Part") "C111630"))
      (libsource (lib "") (part "Unknown_105_200"))
    )
    (comp (ref "D13")
      (value "SS24FL")
      (fields (field (name "BOM_Supplier Part") "C111630"))
      (libsource (lib "") (part "Unknown_555_105"))
    )
    (comp (ref "D14")
      (value "SS24FL")
      (fields (field (name "BOM_Supplier Part") "C111630"))
      (libsource (lib "") (part "Unknown_625_105"))
    )
    (comp (ref "D15")
      (value "40V 4A")
      (fields
        (field (name "BOM_Manufacturer Part") "SSB44-E3/52T")
        (field (name "BOM_Supplier Part") "SSB44-E3/52TGICT-ND")
      )
      (libsource (lib "") (part "Unknown_435_530"))
    )
    (comp (ref "F3")
      (value "200mA")
      (fields
        (field (name "BOM_Manufacturer Part") "0ZCM0020FF2G")
        (field (name "BOM_Supplier Part") "507-1821-1-ND")
      )
      (libsource (lib "") (part "Unknown_695_105"))
    )
    (comp (ref "L1")
      (value "33uH")
      (fields
        (field (name "BOM_Manufacturer Part") "SRN6045TA-330M")
        (field (name "BOM_Supplier Part") "SRN6045TA-330MCT-ND")
      )
      (libsource (lib "") (part "Unknown_335_105"))
    )
    (comp (ref "L2")
      (value "SRN6045TA-4R7M")
      (fields (field (name "BOM_Supplier Part") "SRN6045TA-4R7MCT-ND"))
      (libsource (lib "") (part "Unknown_500_455"))
    )
    (comp (ref "R32") (value "54.9K") (libsource (lib "") (part "Res_0603(1/10W)_EU")))
    (comp (ref "R33") (value "10K") (libsource (lib "") (part "Res_0603(1/10W)_EU")))
    (comp (ref "R34") (value "10K") (libsource (lib "") (part "Res_0603(1/10W)_EU")))
    (comp (ref "R35") (value "54.9K") (libsource (lib "") (part "Res_0603(1/10W)_EU")))
    (comp (ref "R36") (value "140k") (libsource (lib "") (part "Res_0603(1/10W)_EU")))
    (comp (ref "R37") (value "10k") (libsource (lib "") (part "Res_0603(1/10W)_EU")))
    (comp (ref "U16")
      (value "AOZ1282CI")
      (fields (field (name "BOM_Supplier Part") "C111916"))
      (libsource (lib "") (part "Unknown_215_125"))
    )
    (comp (ref "U17")
      (value "AP2112K-3.3TRG1")
      (fields (field (name "BOM_Supplier Part") "C51118"))
      (libsource (lib "") (part "Unknown_850_295"))
    )
    (comp (ref "U18")
      (value "AOZ1284PI")
      (fields (field (name "BOM_Supplier Part") "C48060"))
      (libsource (lib "") (part "Unknown_290_450"))
    )
    (comp (ref "C28") (value "0u1") (libsource (lib "") (part "Unknown_462_190")))
    (comp (ref "C29") (value "0u01") (libsource (lib "") (part "Unknown_302_260")))
    (comp (ref "C58") (value "2u2") (libsource (lib "") (part "Unknown_217_510")))
    (comp (ref "C73") (value "10u") (libsource (lib "") (part "Unknown_687_365")))
    (comp (ref "C74") (value "10u") (libsource (lib "") (part "Unknown_667_365")))
    (comp (ref "C82") (value "0u1") (libsource (lib "") (part "Unknown_117_280")))
    (comp (ref "C83") (value "DNP 47p") (libsource (lib "") (part "Unknown_1015_165")))
    (comp (ref "D17") (value "USB") (libsource (lib "") (part "Unknown_142_160")))
    (comp (ref "J15") (value "uSDHC") (libsource (lib "") (part "Unknown_287_460")))
    (comp (ref "J22") (value "USB") (libsource (lib "") (part "Unknown_252_225")))
    (comp (ref "L7") (value "4n7h") (libsource (lib "") (part "Unknown_755_345")))
    (comp (ref "R44") (value "470R") (libsource (lib "") (part "Unknown_722_140")))
    (comp (ref "R45") (value "47K") (libsource (lib "") (part "Unknown_107_280")))
    (comp (ref "R46") (value "27K") (libsource (lib "") (part "Unknown_142_255")))
    (comp (ref "R47") (value "2K2") (libsource (lib "") (part "Unknown_1007_275")))
    (comp (ref "R48") (value "220R") (libsource (lib "") (part "Unknown_117_415")))
    (comp (ref "R49") (value "220R") (libsource (lib "") (part "Unknown_117_425")))
    (comp (ref "R50") (value "220R") (libsource (lib "") (part "Unknown_117_435")))
    (comp (ref "R52") (value "4K7") (libsource (lib "") (part "Unknown_662_230")))
    (comp (ref "R53") (value "2K2") (libsource (lib "") (part "Unknown_755_165")))
    (comp (ref "R54") (value "27R 1%") (libsource (lib "") (part "Unknown_132_200")))
    (comp (ref "R55") (value "27R 1%") (libsource (lib "") (part "Unknown_132_215")))
    (comp (ref "R60") (value "2K2") (libsource (lib "") (part "Unknown_192_160")))
    (comp (ref "R63") (value "10K") (libsource (lib "") (part "Unknown_222_390")))
    (comp (ref "R64") (value "10K") (libsource (lib "") (part "Unknown_242_390")))
    (comp (ref "R68") (value "100R") (libsource (lib "") (part "Unknown_117_455")))
    (comp (ref "R73") (value "DNP 47K") (libsource (lib "") (part "Unknown_142_390")))
    (comp (ref "R74") (value "DNP 47K") (libsource (lib "") (part "Unknown_162_390")))
    (comp (ref "R75") (value "DNP 47K") (libsource (lib "") (part "Unknown_182_390")))
    (comp (ref "R76") (value "DNP 47K") (libsource (lib "") (part "Unknown_202_390")))
    (comp (ref "R77") (value "220R") (libsource (lib "") (part "Unknown_117_465")))
    (comp (ref "R78") (value "220R") (libsource (lib "") (part "Unknown_117_475")))
    (comp (ref "R79") (value "220R") (libsource (lib "") (part "Unknown_117_485")))
    (comp (ref "R82") (value "0R DNP") (libsource (lib "") (part "Unknown_412_315")))
    (comp (ref "R99") (value "2K2") (libsource (lib "") (part "Unknown_1007_305")))
    (comp (ref "R100") (value "47R") (libsource (lib "") (part "Unknown_755_275")))
    (comp (ref "R101") (value "47R") (libsource (lib "") (part "Unknown_755_290")))
    (comp (ref "R102") (value "2K2") (libsource (lib "") (part "Unknown_1017_215")))
    (comp (ref "R103") (value "470R") (libsource (lib "") (part "Unknown_1017_230")))
    (comp (ref "R105") (value "47R") (libsource (lib "") (part "Unknown_755_305")))
    (comp (ref "U29") (value "74HC74") (libsource (lib "") (part "Unknown_532_270")))
    (comp (ref "U30") (value "ESP-07/12") (libsource (lib "") (part "Unknown_887_285")))
  )
  (nets
    (net (code "1") (name "+3V3") (class "Default")
      (node (ref "C1") (pin "2") (pinfunction "2_2") (pintype "unspecified"))
      (node (ref "C15") (pin "1") (pinfunction "1_1") (pintype "unspecified"))
      (node (ref "C31") (pin "2") (pinfunction "2_2") (pintype "unspecified"))
      (node (ref "C32") (pin "2") (pinfunction "2_2") (pintype "unspecified"))
      (node (ref "C33") (pin "2") (pinfunction "2_2") (pintype "unspecified"))
      (node (ref "C34") (pin "2") (pinfunction "2_2") (pintype "unspecified"))
      (node (ref "C36") (pin "2") (pinfunction "2_2") (pintype "unspecified"))
      (node (ref "C37") (pin "2") (pinfunction "2_2") (pintype "unspecified"))
      (node (ref "C38") (pin "2") (pinfunction "2_2") (pintype "unspecified"))
      (node (ref "C39") (pin "2") (pinfunction "2_2") (pintype "input"))
      (node (ref "C40") (pin "2") (pinfunction "2_2") (pintype "input"))
      (node (ref "C58") (pin "1") (pintype "unspecified"))
      (node (ref "C7") (pin "2") (pinfunction "2_2") (pintype "unspecified"))
      (node (ref "C73") (pin "1") (pintype "unspecified"))
      (node (ref "C74") (pin "1") (pintype "unspecified"))
      (node (ref "J1") (pin "1") (pinfunction "1_1") (pintype "unspecified"))
      (node (ref "J15") (pin "4") (pinfunction "VDD_4") (pintype "bidirectional"))
      (node (ref "J21") (pin "1") (pinfunction "VDD_1") (pintype "bidirectional"))
      (node (ref "JP1") (pin "1") (pinfunction "1_1") (pintype "unspecified"))
      (node (ref "L5") (pin "2") (pinfunction "B_2") (pintype "unspecified"))
      (node (ref "L7") (pin "1") (pinfunction "A_1") (pintype "unspecified"))
      (node (ref "LED5") (pin "1") (pinfunction "+_1") (pintype "unspecified"))
      (node (ref "P4") (pin "2") (pinfunction "2_2") (pintype "input"))
      (node (ref "R106") (pin "2") (pintype "unspecified"))
      (node (ref "R11") (pin "2") (pinfunction "2_2") (pintype "unspecified"))
      (node (ref "R12") (pin "2") (pinfunction "2_2") (pintype "unspecified"))
      (node (ref "R57") (pin "1") (pintype "unspecified"))
      (node (ref "R58") (pin "1") (pintype "unspecified"))
      (node (ref "R59") (pin "1") (pintype "unspecified"))
      (node (ref "R63") (pin "2") (pintype "unspecified"))
      (node (ref "R64") (pin "2") (pintype "unspecified"))
      (node (ref "R73") (pin "2") (pintype "unspecified"))
      (node (ref "R74") (pin "2") (pintype "unspecified"))
      (node (ref "R75") (pin "2") (pintype "unspecified"))
      (node (ref "R76") (pin "2") (pintype "unspecified"))
      (node (ref "U1") (pin "134") (pinfunction "VDDIO_134") (pintype "input"))
      (node (ref "U1") (pin "143") (pinfunction "VDDIO_143") (pintype "input"))
      (node (ref "U1") (pin "30") (pinfunction "VDDIO_30") (pintype "input"))
      (node (ref "U1") (pin "43") (pinfunction "VDDIO_43") (pintype "input"))
      (node (ref "U1") (pin "5") (pinfunction "VDDIN_5") (pintype "input"))
      (node (ref "U1") (pin "72") (pinfunction "VDDIO_72") (pintype "input"))
      (node (ref "U1") (pin "80") (pinfunction "VDDIO_80") (pintype "input"))
      (node (ref "U1") (pin "96") (pinfunction "VDDIO_96") (pintype "input"))
      (node (ref "U17") (pin "5") (pinfunction "OUT_5") (pintype "unspecified"))
      (node (ref "U2") (pin "4") (pinfunction "VCC_4") (pintype "unspecified"))
      (node (ref "U29") (pin "14") (pinfunction "VCC_14") (pintype "bidirectional"))
      (node (ref "X+") (pin "3") (pinfunction "3_3") (pintype "unspecified"))
      (node (ref "X-") (pin "3") (pinfunction "3_3") (pintype "unspecified"))
      (node (ref "Y+") (pin "3") (pinfunction "3_3") (pintype "unspecified"))
      (node (ref "Y-") (pin "3") (pinfunction "3_3") (pintype "unspecified"))
      (node (ref "Z+") (pin "3") (pinfunction "3_3") (pintype "unspecified"))
      (node (ref "Z-") (pin "3") (pinfunction "3_3") (pintype "unspecified"))
    )
    (net (code "2") (name "+5V") (class "Default")
      (node (ref "C14") (pin "1") (pinfunction "1_1") (pintype "unspecified"))
      (node (ref "C8") (pin "2") (pinfunction "2_2") (pintype "input"))
      (node (ref "D10") (pin "2") (pinfunction "A_2") (pintype "unspecified"))
      (node (ref "D13") (pin "1") (pinfunction "C_1") (pintype "unspecified"))
      (node (ref "D14") (pin "1") (pinfunction "C_1") (pintype "unspecified"))
      (node (ref "ENC_1") (pin "4") (pinfunction "4_4") (pintype "unspecified"))
      (node (ref "ENC_2") (pin "4") (pinfunction "4_4") (pintype "unspecified"))
      (node (ref "ENC_3") (pin "4") (pinfunction "4_4") (pintype "unspecified"))
      (node (ref "ENC_4") (pin "4") (pinfunction "4_4") (pintype "unspecified"))
      (node (ref "EXP1") (pin "10") (pinfunction "10_10") (pintype "unspecified"))
      (node (ref "EXP3") (pin "13") (pinfunction "13_13") (pintype "unspecified"))
      (node (ref "J1") (pin "3") (pinfunction "3_3") (pintype "unspecified"))
      (node (ref "LED4") (pin "1") (pinfunction "+_1") (pintype "unspecified"))
      (node (ref "P3") (pin "2") (pinfunction "2_2") (pintype "input"))
      (node (ref "U17") (pin "1") (pinfunction "VIN_1") (pintype "unspecified"))
      (node (ref "U17") (pin "3") (pinfunction "EN_3") (pintype "unspecified"))
      (node (ref "U6") (pin "1") (pinfunction "NC_1") (pintype "unspecified"))
    )
    (net (code "3") (name "+12V") (class "Default")
      (node (ref "C20") (pin "1") (pinfunction "1_1") (pintype "unspecified"))
      (node (ref "C21") (pin "1") (pinfunction "1_1") (pintype "input"))
      (node (ref "EXP3") (pin "14") (pinfunction "14_14") (pintype "unspecified"))
      (node (ref "H1") (pin "3") (pinfunction "3_3") (pintype "input"))
      (node (ref "H2") (pin "3") (pinfunction "3_3") (pintype "input"))
      (node (ref "H3") (pin "3") (pinfunction "3_3") (pintype "input"))
      (node (ref "L2") (pin "2") (pinfunction "2_2") (pintype "bidirectional"))
      (node (ref "LED1") (pin "1") (pinfunction "+_1") (pintype "unspecified"))
      (node (ref "P2") (pin "2") (pinfunction "2_2") (pintype "input"))
      (node (ref "R36") (pin "2") (pinfunction "2_2") (pintype "unspecified"))
    )
    (net (code "4") (name "+DRV") (class "Default")
      (node (ref "H10") (pin "3") (pinfunction "3_3") (pintype "input"))
      (node (ref "H11") (pin "3") (pinfunction "3_3") (pintype "input"))
      (node (ref "H12") (pin "3") (pinfunction "3_3") (pintype "input"))
      (node (ref "H13") (pin "3") (pinfunction "3_3") (pintype "input"))
      (node (ref "H14") (pin "3") (pinfunction "3_3") (pintype "input"))
      (node (ref "H15") (pin "3") (pinfunction "3_3") (pintype "input"))
      (node (ref "H17") (pin "3") (pinfunction "3_3") (pintype "input"))
      (node (ref "H18") (pin "3") (pinfunction "3_3") (pintype "input"))
      (node (ref "H19") (pin "3") (pinfunction "3_3") (pintype "input"))
      (node (ref "H21") (pin "3") (pinfunction "3_3") (pintype "input"))
      (node (ref "H22") (pin "3") (pinfunction "3_3") (pintype "input"))
      (node (ref "H23") (pin "3") (pinfunction "3_3") (pintype "input"))
      (node (ref "H25") (pin "3") (pinfunction "3_3") (pintype "input"))
      (node (ref "H26") (pin "3") (pinfunction "3_3") (pintype "input"))
      (node (ref "H27") (pin "3") (pinfunction "3_3") (pintype "input"))
      (node (ref "H5") (pin "3") (pinfunction "3_3") (pintype "input"))
      (node (ref "H6") (pin "3") (pinfunction "3_3") (pintype "input"))
      (node (ref "H7") (pin "3") (pinfunction "3_3") (pintype "input"))
      (node (ref "J1") (pin "2") (pinfunction "2_2") (pintype "unspecified"))
      (node (ref "R38") (pin "2") (pinfunction "2_2") (pintype "unspecified"))
      (node (ref "R39") (pin "2") (pinfunction "2_2") (pintype "unspecified"))
      (node (ref "R40") (pin "2") (pinfunction "2_2") (pintype "unspecified"))
      (node (ref "R41") (pin "2") (pinfunction "2_2") (pintype "unspecified"))
      (node (ref "R42") (pin "2") (pinfunction "2_2") (pintype "unspecified"))
      (node (ref "R43") (pin "2") (pinfunction "2_2") (pintype "unspecified"))
      (node (ref "U23") (pin "10") (pinfunction "VDD_10") (pintype "unspecified"))
      (node (ref "U24") (pin "10") (pinfunction "VDD_10") (pintype "unspecified"))
      (node (ref "U25") (pin "10") (pinfunction "VDD_10") (pintype "unspecified"))
      (node (ref "U26") (pin "10") (pinfunction "VDD_10") (pintype "unspecified"))
      (node (ref "U27") (pin "10") (pinfunction "VDD_10") (pintype "unspecified"))
      (node (ref "U28") (pin "10") (pinfunction "VDD_10") (pintype "unspecified"))
    )
    (net (code "5") (name "5V_DCDC") (class "Default")
      (node (ref "C12") (pin "1") (pinfunction "1_1") (pintype "unspecified"))
      (node (ref "C13") (pin "1") (pinfunction "1_1") (pintype "input"))
      (node (ref "D13") (pin "2") (pinfunction "A_2") (pintype "unspecified"))
      (node (ref "L1") (pin "2") (pinfunction "2_2") (pintype "unspecified"))
      (node (ref "R2") (pin "2") (pinfunction "2_2") (pintype "unspecified"))
      (node (ref "R32") (pin "2") (pinfunction "2_2") (pintype "unspecified"))
      (node (ref "U18") (pin "8") (pinfunction "EN_8") (pintype "unspecified"))
    )
    (net (code "6") (name "A10") (class "Default")
      (node (ref "EXP3") (pin "7") (pinfunction "7_7") (pintype "unspecified"))
    )
    (net (code "7") (name "ADVREF") (class "Default")
      (node (ref "C41") (pin "2") (pinfunction "2_2") (pintype "unspecified"))
      (node (ref "L5") (pin "1") (pinfunction "A_1") (pintype "unspecified"))
      (node (ref "R61") (pin "2") (pintype "unspecified"))
      (node (ref "R62") (pin "2") (pintype "unspecified"))
      (node (ref "R69") (pin "2") (pintype "unspecified"))
      (node (ref "R7") (pin "2") (pintype "unspecified"))
      (node (ref "R8") (pin "2") (pintype "unspecified"))
      (node (ref "U1") (pin "9") (pinfunction "ADVREF_9") (pintype "input"))
    )
    (net (code "8") (name "BEEPER") (class "Default")
      (node (ref "EXP1") (pin "1") (pinfunction "1_1") (pintype "unspecified"))
    )
    (net (code "9") (name "BTN_EN1") (class "Default")
      (node (ref "EXP2") (pin "5") (pinfunction "5_5") (pintype "unspecified"))
    )
    (net (code "10") (name "BTN_EN2") (class "Default")
      (node (ref "EXP2") (pin "3") (pinfunction "3_3") (pintype "unspecified"))
    )
    (net (code "11") (name "BTN_ENC") (class "Default")
      (node (ref "EXP1") (pin "2") (pinfunction "2_2") (pintype "unspecified"))
      (node (ref "U1") (pin "48") (pinfunction "PC7_48") (pintype "input"))
    )
    (net (code "12") (name "CS3") (class "Default")
      (node (ref "U1") (pin "117") (pinfunction "PC19_117") (pintype "input"))
    )
    (net (code "13") (name "CS4") (class "Default")
      (node (ref "U1") (pin "120") (pinfunction "PC20_120") (pintype "input"))
    )
    (net (code "14") (name "DDM") (class "Default")
      (node (ref "R55") (pin "2") (pintype "unspecified"))
      (node (ref "U1") (pin "136") (pinfunction "DDM_136") (pintype "input"))
    )
    (net (code "15") (name "DDP") (class "Default")
      (node (ref "R54") (pin "2") (pintype "unspecified"))
      (node (ref "U1") (pin "137") (pinfunction "DDP_137") (pintype "input"))
    )
    (net (code "16") (name "E0-CS") (class "Default")
      (node (ref "H19") (pin "1") (pinfunction "1_1") (pintype "input"))
      (node (ref "U1") (pin "55") (pinfunction "PD24_55") (pintype "input"))
    )
    (net (code "17") (name "E0-DIR") (class "Default")
      (node (ref "U1") (pin "99") (pinfunction "PA1_99") (pintype "input"))
      (node (ref "U26") (pin "8") (pinfunction "DIR_8") (pintype "unspecified"))
    )
    (net (code "18") (name "E0-EN") (class "Default")
      (node (ref "R41") (pin "1") (pinfunction "1_1") (pintype "unspecified"))
      (node (ref "U1") (pin "103") (pinfunction "PC17_103") (pintype "input"))
      (node (ref "U26") (pin "1") (pinfunction "EN_1") (pintype "unspecified"))
    )
    (net (code "19") (name "E0-SLP") (class "Default")
      (node (ref "H20") (pin "3") (pinfunction "3_3") (pintype "input"))
      (node (ref "U26") (pin "6") (pinfunction "SLP_6") (pintype "unspecified"))
    )
    (net (code "20") (name "E0-STEP") (class "Default")
      (node (ref "U1") (pin "125") (pinfunction "PD5_125") (pintype "input"))
      (node (ref "U26") (pin "7") (pinfunction "STEP_7") (pintype "unspecified"))
    )
    (net (code "21") (name "E1-CS") (class "Default")
      (node (ref "H23") (pin "1") (pinfunction "1_1") (pintype "input"))
      (node (ref "U1") (pin "52") (pinfunction "PD25_52") (pintype "input"))
    )
    (net (code "22") (name "E1-DIR") (class "Default")
      (node (ref "U1") (pin "110") (pinfunction "PD9_110") (pintype "input"))
      (node (ref "U27") (pin "8") (pinfunction "DIR_8") (pintype "unspecified"))
    )
    (net (code "23") (name "E1-EN") (class "Default")
      (node (ref "R42") (pin "1") (pinfunction "1_1") (pintype "unspecified"))
      (node (ref "U1") (pin "133") (pinfunction "PC25_133") (pintype "input"))
      (node (ref "U27") (pin "1") (pinfunction "EN_1") (pintype "unspecified"))
    )
    (net (code "24") (name "E1-SLP") (class "Default")
      (node (ref "H24") (pin "3") (pinfunction "3_3") (pintype "input"))
      (node (ref "U27") (pin "6") (pinfunction "SLP_6") (pintype "unspecified"))
    )
    (net (code "25") (name "E1-STEP") (class "Default")
      (node (ref "U1") (pin "126") (pinfunction "PD4_126") (pintype "input"))
      (node (ref "U27") (pin "7") (pinfunction "STEP_7") (pintype "unspecified"))
    )
    (net (code "26") (name "E2-CS") (class "Default")
      (node (ref "H27") (pin "1") (pinfunction "1_1") (pintype "input"))
      (node (ref "U1") (pin "53") (pinfunction "PD26_53") (pintype "input"))
    )
    (net (code "27") (name "E2-DIR") (class "Default")
      (node (ref "U1") (pin "71") (pinfunction "PD28_71") (pintype "input"))
      (node (ref "U28") (pin "8") (pinfunction "DIR_8") (pintype "unspecified"))
    )
    (net (code "28") (name "E2-EN") (class "Default")
      (node (ref "R43") (pin "1") (pinfunction "1_1") (pintype "unspecified"))
      (node (ref "U1") (pin "57") (pinfunction "PD23_57") (pintype "input"))
      (node (ref "U28") (pin "1") (pinfunction "EN_1") (pintype "unspecified"))
    )
    (net (code "29") (name "E2-SLP") (class "Default")
      (node (ref "H28") (pin "3") (pinfunction "3_3") (pintype "input"))
      (node (ref "U28") (pin "6") (pinfunction "SLP_6") (pintype "unspecified"))
    )
    (net (code "30") (name "E2-STEP") (class "Default")
      (node (ref "U1") (pin "131") (pinfunction "PD2_131") (pintype "input"))
      (node (ref "U28") (pin "7") (pinfunction "STEP_7") (pintype "unspecified"))
    )
    (net (code "31") (name "ERASE") (class "Default")
      (node (ref "JP1") (pin "2") (pinfunction "2_2") (pintype "unspecified"))
      (node (ref "U1") (pin "87") (pinfunction "ERASE_87") (pintype "input"))
    )
    (net (code "32") (name "ESP_DATA_RDY") (class "Default")
      (node (ref "R47") (pin "2") (pintype "unspecified"))
      (node (ref "U1") (pin "2") (pinfunction "PD31_2") (pintype "input"))
    )
    (net (code "33") (name "ESP_EN") (class "Default")
      (node (ref "R52") (pin "1") (pintype "unspecified"))
      (node (ref "U1") (pin "28") (pinfunction "PE5_28") (pintype "input"))
      (node (ref "U30") (pin "3") (pinfunction "CH_PD/EN_3") (pintype "input"))
    )
    (net (code "34") (name "ESP_RST") (class "Default")
      (node (ref "R44") (pin "2") (pintype "unspecified"))
      (node (ref "U1") (pin "27") (pinfunction "PE4_27") (pintype "input"))
    )
    (net (code "35") (name "FAN_0") (class "Default")
      (node (ref "R26") (pin "2") (pinfunction "2_2") (pintype "unspecified"))
      (node (ref "R27") (pin "2") (pinfunction "2_2") (pintype "unspecified"))
      (node (ref "R28") (pin "2") (pinfunction "2_2") (pintype "unspecified"))
      (node (ref "U1") (pin "49") (pinfunction "TIOA1_49") (pintype "input"))
    )
    (net (code "36") (name "FAN_1") (class "Default")
      (node (ref "R29") (pin "2") (pinfunction "2_2") (pintype "unspecified"))
      (node (ref "R30") (pin "2") (pinfunction "2_2") (pintype "unspecified"))
      (node (ref "R31") (pin "2") (pinfunction "2_2") (pintype "unspecified"))
      (node (ref "U1") (pin "58") (pinfunction "TIOA6_58") (pintype "input"))
    )
    (net (code "37") (name "FB1") (class "Default")
      (node (ref "R32") (pin "1") (pinfunction "1_1") (pintype "unspecified"))
      (node (ref "R33") (pin "2") (pinfunction "2_2") (pintype "unspecified"))
      (node (ref "U16") (pin "3") (pinfunction "FB_3") (pintype "unspecified"))
    )
    (net (code "38") (name "FB2") (class "Default")
      (node (ref "R36") (pin "1") (pinfunction "1_1") (pintype "unspecified"))
      (node (ref "R37") (pin "2") (pinfunction "2_2") (pintype "unspecified"))
      (node (ref "U18") (pin "6") (pinfunction "FB_6") (pintype "unspecified"))
    )
    (net (code "39") (name "GND") (class "Default")
      (node (ref "C1") (pin "1") (pinfunction "1_1") (pintype "unspecified"))
      (node (ref "C10") (pin "2") (pinfunction "2_2") (pintype "unspecified"))
      (node (ref "C12") (pin "2") (pinfunction "2_2") (pintype "unspecified"))
      (node (ref "C13") (pin "2") (pinfunction "2_2") (pintype "input"))
      (node (ref "C14") (pin "2") (pinfunction "2_2") (pintype "unspecified"))
      (node (ref "C15") (pin "2") (pinfunction "2_2") (pintype "unspecified"))
      (node (ref "C16") (pin "1") (pinfunction "1_1") (pintype "unspecified"))
      (node (ref "C17") (pin "1") (pinfunction "1_1") (pintype "unspecified"))
      (node (ref "C18") (pin "2") (pinfunction "2_2") (pintype "unspecified"))
      (node (ref "C20") (pin "2") (pinfunction "2_2") (pintype "unspecified"))
      (node (ref "C21") (pin "2") (pinfunction "2_2") (pintype "input"))
      (node (ref "C22") (pin "2") (pinfunction "2_2") (pintype "input"))
      (node (ref "C23") (pin "2") (pinfunction "2_2") (pintype "input"))
      (node (ref "C24") (pin "2") (pinfunction "2_2") (pintype "input"))
      (node (ref "C25") (pin "2") (pinfunction "2_2") (pintype "input"))
      (node (ref "C26") (pin "2") (pinfunction "2_2") (pintype "input"))
      (node (ref "C27") (pin "2") (pinfunction "2_2") (pintype "input"))
      (node (ref "C28") (pin "2") (pintype "unspecified"))
      (node (ref "C29") (pin "2") (pintype "unspecified"))
      (node (ref "C30") (pin "1") (pinfunction "1_1") (pintype "unspecified"))
      (node (ref "C31") (pin "1") (pinfunction "1_1") (pintype "unspecified"))
      (node (ref "C32") (pin "1") (pinfunction "1_1") (pintype "unspecified"))
      (node (ref "C33") (pin "1") (pinfunction "1_1") (pintype "unspecified"))
      (node (ref "C34") (pin "1") (pinfunction "1_1") (pintype "unspecified"))
      (node (ref "C35") (pin "1") (pinfunction "1_1") (pintype "unspecified"))
      (node (ref "C36") (pin "1") (pinfunction "1_1") (pintype "unspecified"))
      (node (ref "C37") (pin "1") (pinfunction "1_1") (pintype "unspecified"))
      (node (ref "C38") (pin "1") (pinfunction "1_1") (pintype "unspecified"))
      (node (ref "C39") (pin "1") (pinfunction "1_1") (pintype "input"))
      (node (ref "C40") (pin "1") (pinfunction "1_1") (pintype "input"))
      (node (ref "C41") (pin "1") (pinfunction "1_1") (pintype "unspecified"))
      (node (ref "C42") (pin "1") (pinfunction "1_1") (pintype "input"))
      (node (ref "C43") (pin "1") (pinfunction "1_1") (pintype "input"))
      (node (ref "C44") (pin "2") (pintype "unspecified"))
      (node (ref "C45") (pin "2") (pintype "unspecified"))
      (node (ref "C46") (pin "1") (pinfunction "1_1") (pintype "unspecified"))
      (node (ref "C47") (pin "1") (pinfunction "1_1") (pintype "unspecified"))
      (node (ref "C48") (pin "1") (pinfunction "1_1") (pintype "unspecified"))
      (node (ref "C49") (pin "1") (pinfunction "1_1") (pintype "unspecified"))
      (node (ref "C50") (pin "1") (pinfunction "1_1") (pintype "unspecified"))
      (node (ref "C51") (pin "1") (pinfunction "1_1") (pintype "unspecified"))
      (node (ref "C52") (pin "2") (pinfunction "2_2") (pintype "input"))
      (node (ref "C53") (pin "1") (pinfunction "1_1") (pintype "input"))
      (node (ref "C54") (pin "2") (pintype "unspecified"))
      (node (ref "C55") (pin "2") (pintype "unspecified"))
      (node (ref "C56") (pin "2") (pintype "unspecified"))
      (node (ref "C58") (pin "2") (pintype "unspecified"))
      (node (ref "C59") (pin "2") (pintype "unspecified"))
      (node (ref "C60") (pin "2") (pintype "unspecified"))
      (node (ref "C7") (pin "1") (pinfunction "1_1") (pintype "unspecified"))
      (node (ref "C73") (pin "2") (pintype "unspecified"))
      (node (ref "C74") (pin "2") (pintype "unspecified"))
      (node (ref "C8") (pin "1") (pinfunction "1_1") (pintype "input"))
      (node (ref "C82") (pin "2") (pintype "unspecified"))
      (node (ref "C83") (pin "2") (pintype "unspecified"))
      (node (ref "C9") (pin "2") (pinfunction "2_2") (pintype "input"))
      (node (ref "D11") (pin "2") (pinfunction "A_2") (pintype "unspecified"))
      (node (ref "D12") (pin "2") (pinfunction "A_2") (pintype "unspecified"))
      (node (ref "D15") (pin "2") (pinfunction "A_2") (pintype "unspecified"))
      (node (ref "D8") (pin "2") (pinfunction "A_2") (pintype "unspecified"))
      (node (ref "ENC_1") (pin "3") (pinfunction "3_3") (pintype "unspecified"))
      (node (ref "ENC_2") (pin "3") (pinfunction "3_3") (pintype "unspecified"))
      (node (ref "ENC_3") (pin "3") (pinfunction "3_3") (pintype "unspecified"))
      (node (ref "ENC_4") (pin "3") (pinfunction "3_3") (pintype "unspecified"))
      (node (ref "EXP1") (pin "9") (pinfunction "9_9") (pintype "unspecified"))
      (node (ref "EXP2") (pin "9") (pinfunction "9_9") (pintype "unspecified"))
      (node (ref "EXP3") (pin "11") (pinfunction "11_11") (pintype "unspecified"))
      (node (ref "EXP3") (pin "12") (pinfunction "12_12") (pintype "unspecified"))
      (node (ref "F4") (pin "2") (pinfunction "2_2") (pintype "unspecified"))
      (node (ref "J15") (pin "6") (pinfunction "GND_6") (pintype "bidirectional"))
      (node (ref "J15") (pin "G") (pinfunction "GND_G") (pintype "bidirectional"))
      (node (ref "J21") (pin "3") (pinfunction "GND_3") (pintype "bidirectional"))
      (node (ref "J21") (pin "5") (pinfunction "GND_5") (pintype "bidirectional"))
      (node (ref "J21") (pin "9") (pinfunction "GND_9") (pintype "bidirectional"))
      (node (ref "J22") (pin "5") (pinfunction "GND_5") (pintype "bidirectional"))
      (node (ref "LED10") (pin "2") (pinfunction "-_2") (pintype "unspecified"))
      (node (ref "LED11") (pin "2") (pinfunction "-_2") (pintype "unspecified"))
      (node (ref "LED12") (pin "2") (pinfunction "-_2") (pintype "unspecified"))
      (node (ref "LED2") (pin "2") (pinfunction "-_2") (pintype "unspecified"))
      (node (ref "LED3") (pin "2") (pinfunction "-_2") (pintype "unspecified"))
      (node (ref "LED6") (pin "2") (pinfunction "-_2") (pintype "unspecified"))
      (node (ref "LED7") (pin "2") (pinfunction "-_2") (pintype "unspecified"))
      (node (ref "LED8") (pin "2") (pinfunction "-_2") (pintype "unspecified"))
      (node (ref "LED9") (pin "2") (pinfunction "-_2") (pintype "unspecified"))
      (node (ref "P1") (pin "1") (pinfunction "1_1") (pintype "input"))
      (node (ref "P10") (pin "2") (pinfunction "2_2") (pintype "unspecified"))
      (node (ref "P11") (pin "2") (pinfunction "2_2") (pintype "unspecified"))
      (node (ref "P12") (pin "2") (pinfunction "2_2") (pintype "unspecified"))
      (node (ref "P13") (pin "2") (pinfunction "2_2") (pintype "unspecified"))
      (node (ref "P2") (pin "1") (pinfunction "1_1") (pintype "input"))
      (node (ref "P3") (pin "1") (pinfunction "1_1") (pintype "input"))
      (node (ref "P4") (pin "1") (pinfunction "1_1") (pintype "input"))
      (node (ref "P8") (pin "2") (pinfunction "2_2") (pintype "input"))
      (node (ref "P9") (pin "2") (pinfunction "2_2") (pintype "unspecified"))
      (node (ref "Q1") (pin "1") (pinfunction "S_1") (pintype "unspecified"))
      (node (ref "Q1") (pin "2") (pinfunction "S_2") (pintype "unspecified"))
      (node (ref "Q1") (pin "3") (pinfunction "S_3") (pintype "unspecified"))
      (node (ref "Q2") (pin "1") (pinfunction "S_1") (pintype "unspecified"))
      (node (ref "Q2") (pin "2") (pinfunction "S_2") (pintype "unspecified"))
      (node (ref "Q2") (pin "3") (pinfunction "S_3") (pintype "unspecified"))
      (node (ref "Q3") (pin "1") (pinfunction "S_1") (pintype "unspecified"))
      (node (ref "Q3") (pin "2") (pinfunction "S_2") (pintype "unspecified"))
      (node (ref "Q3") (pin "3") (pinfunction "S_3") (pintype "unspecified"))
      (node (ref "Q4") (pin "1") (pinfunction "S_1") (pintype "unspecified"))
      (node (ref "Q4") (pin "2") (pinfunction "S_2") (pintype "unspecified"))
      (node (ref "Q4") (pin "3") (pinfunction "S_3") (pintype "unspecified"))
      (node (ref "Q5") (pin "1") (pinfunction "S_1") (pintype "unspecified"))
      (node (ref "Q5") (pin "2") (pinfunction "S_2") (pintype "unspecified"))
      (node (ref "Q5") (pin "3") (pinfunction "S_3") (pintype "unspecified"))
      (node (ref "Q6") (pin "1") (pinfunction "S_1") (pintype "unspecified"))
      (node (ref "Q6") (pin "2") (pinfunction "S_2") (pintype "unspecified"))
      (node (ref "Q6") (pin "3") (pinfunction "S_3") (pintype "unspecified"))
      (node (ref "R1") (pin "1") (pinfunction "1_1") (pintype "unspecified"))
      (node (ref "R13") (pin "1") (pinfunction "1_1") (pintype "unspecified"))
      (node (ref "R16") (pin "1") (pinfunction "1_1") (pintype "unspecified"))
      (node (ref "R17") (pin "1") (pinfunction "1_1") (pintype "unspecified"))
      (node (ref "R20") (pin "1") (pinfunction "1_1") (pintype "unspecified"))
      (node (ref "R24") (pin "1") (pinfunction "1_1") (pintype "unspecified"))
      (node (ref "R28") (pin "1") (pinfunction "1_1") (pintype "unspecified"))
      (node (ref "R29") (pin "1") (pinfunction "1_1") (pintype "unspecified"))
      (node (ref "R33") (pin "1") (pinfunction "1_1") (pintype "unspecified"))
      (node (ref "R34") (pin "1") (pinfunction "1_1") (pintype "unspecified"))
      (node (ref "R37") (pin "1") (pinfunction "1_1") (pintype "unspecified"))
      (node (ref "R4") (pin "1") (pinfunction "1_1") (pintype "unspecified"))
      (node (ref "R45") (pin "2") (pintype "unspecified"))
      (node (ref "R5") (pin "1") (pinfunction "1_1") (pintype "unspecified"))
      (node (ref "R51") (pin "1") (pinfunction "1_1") (pintype "unspecified"))
      (node (ref "R52") (pin "2") (pintype "unspecified"))
      (node (ref "R53") (pin "2") (pintype "unspecified"))
      (node (ref "R60") (pin "2") (pintype "unspecified"))
      (node (ref "R72") (pin "1") (pinfunction "1_1") (pintype "unspecified"))
      (node (ref "R80") (pin "1") (pinfunction "1_1") (pintype "unspecified"))
      (node (ref "R81") (pin "1") (pinfunction "1_1") (pintype "unspecified"))
      (node (ref "R84") (pin "1") (pinfunction "1_1") (pintype "unspecified"))
      (node (ref "S1") (pin "1") (pintype "bidirectional"))
      (node (ref "S1") (pin "2") (pintype "bidirectional"))
      (node (ref "U1") (pin "104") (pinfunction "JTAGSEL_104") (pintype "input"))
      (node (ref "U1") (pin "115") (pinfunction "GND_115") (pintype "input"))
      (node (ref "U1") (pin "135") (pinfunction "GND_135") (pintype "input"))
      (node (ref "U1") (pin "138") (pinfunction "GND_138") (pintype "input"))
      (node (ref "U1") (pin "44") (pinfunction "GND_44") (pintype "input"))
      (node (ref "U1") (pin "61") (pinfunction "GND_61") (pintype "input"))
      (node (ref "U1") (pin "8") (pinfunction "GND_8") (pintype "input"))
      (node (ref "U1") (pin "85") (pinfunction "TEST_85") (pintype "input"))
      (node (ref "U1") (pin "95") (pinfunction "GND_95") (pintype "input"))
      (node (ref "U10") (pin "1") (pinfunction "1_1") (pintype "unspecified"))
      (node (ref "U15") (pin "1") (pinfunction "1_1") (pintype "unspecified"))
      (node (ref "U16") (pin "2") (pinfunction "GND_2") (pintype "unspecified"))
      (node (ref "U17") (pin "2") (pinfunction "GND_2") (pintype "unspecified"))
      (node (ref "U18") (pin "3") (pinfunction "GND_3") (pintype "unspecified"))
      (node (ref "U2") (pin "2") (pinfunction "GND_2") (pintype "unspecified"))
      (node (ref "U2") (pin "5") (pinfunction "WP_5") (pintype "unspecified"))
      (node (ref "U23") (pin "15") (pinfunction "GND_15") (pintype "unspecified"))
      (node (ref "U23") (pin "9") (pinfunction "GND_9") (pintype "unspecified"))
      (node (ref "U24") (pin "15") (pinfunction "GND_15") (pintype "unspecified"))
      (node (ref "U24") (pin "9") (pinfunction "GND_9") (pintype "unspecified"))
      (node (ref "U25") (pin "15") (pinfunction "GND_15") (pintype "unspecified"))
      (node (ref "U25") (pin "9") (pinfunction "GND_9") (pintype "unspecified"))
      (node (ref "U26") (pin "15") (pinfunction "GND_15") (pintype "unspecified"))
      (node (ref "U26") (pin "9") (pinfunction "GND_9") (pintype "unspecified"))
      (node (ref "U27") (pin "15") (pinfunction "GND_15") (pintype "unspecified"))
      (node (ref "U27") (pin "9") (pinfunction "GND_9") (pintype "unspecified"))
      (node (ref "U28") (pin "15") (pinfunction "GND_15") (pintype "unspecified"))
      (node (ref "U28") (pin "9") (pinfunction "GND_9") (pintype "unspecified"))
      (node (ref "U29") (pin "7") (pinfunction "GND_7") (pintype "bidirectional"))
      (node (ref "U30") (pin "9") (pinfunction "GND_9") (pintype "bidirectional"))
      (node (ref "U6") (pin "3") (pinfunction "GND_3") (pintype "unspecified"))
      (node (ref "X+") (pin "2") (pinfunction "2_2") (pintype "unspecified"))
      (node (ref "X-") (pin "2") (pinfunction "2_2") (pintype "unspecified"))
      (node (ref "X2") (pin "2") (pinfunction "2_2") (pintype "unspecified"))
      (node (ref "X2") (pin "4") (pinfunction "4_4") (pintype "unspecified"))
      (node (ref "Y+") (pin "2") (pinfunction "2_2") (pintype "unspecified"))
      (node (ref "Y-") (pin "2") (pinfunction "2_2") (pintype "unspecified"))
      (node (ref "Z+") (pin "2") (pinfunction "2_2") (pintype "unspecified"))
      (node (ref "Z-") (pin "2") (pinfunction "2_2") (pintype "unspecified"))
    )
    (net (code "40") (name "HB") (class "Default")
      (node (ref "R23") (pin "2") (pinfunction "2_2") (pintype "unspecified"))
      (node (ref "R24") (pin "2") (pinfunction "2_2") (pintype "unspecified"))
      (node (ref "R25") (pin "1") (pinfunction "1_1") (pintype "unspecified"))
      (node (ref "U1") (pin "23") (pinfunction "PWML0_23") (pintype "input"))
    )
    (net (code "41") (name "HE_0") (class "Default")
      (node (ref "R14") (pin "2") (pinfunction "2_2") (pintype "unspecified"))
      (node (ref "R15") (pin "2") (pinfunction "2_2") (pintype "unspecified"))
      (node (ref "R16") (pin "2") (pinfunction "2_2") (pintype "unspecified"))
      (node (ref "U1") (pin "22") (pinfunction "PWML1_22") (pintype "input"))
    )
    (net (code "42") (name "HE_1") (class "Default")
      (node (ref "R17") (pin "2") (pinfunction "2_2") (pintype "unspecified"))
      (node (ref "R18") (pin "2") (pinfunction "2_2") (pintype "unspecified"))
      (node (ref "R19") (pin "2") (pinfunction "2_2") (pintype "unspecified"))
      (node (ref "U1") (pin "45") (pinfunction "PWML2_45") (pintype "input"))
    )
    (net (code "43") (name "HE_2") (class "Default")
      (node (ref "R20") (pin "2") (pinfunction "2_2") (pintype "unspecified"))
      (node (ref "R21") (pin "2") (pinfunction "2_2") (pintype "unspecified"))
      (node (ref "R22") (pin "2") (pinfunction "2_2") (pintype "unspecified"))
      (node (ref "U1") (pin "40") (pinfunction "PWML3_40") (pintype "input"))
    )
    (net (code "44") (name "KILL") (class "Default")
      (node (ref "EXP2") (pin "10") (pinfunction "10_10") (pintype "unspecified"))
      (node (ref "U1") (pin "124") (pinfunction "PC22_124") (pintype "input"))
    )
    (net (code "45") (name "LCD_D4") (class "Default")
      (node (ref "EXP1") (pin "5") (pinfunction "5_5") (pintype "unspecified"))
      (node (ref "U1") (pin "63") (pinfunction "PD21_63") (pintype "input"))
    )
    (net (code "46") (name "LCD_D5") (class "Default")
      (node (ref "EXP1") (pin "6") (pinfunction "6_6") (pintype "unspecified"))
      (node (ref "U1") (pin "65") (pinfunction "PD20_65") (pintype "input"))
    )
    (net (code "47") (name "LCD_D6") (class "Default")
      (node (ref "EXP1") (pin "7") (pinfunction "7_7") (pintype "unspecified"))
      (node (ref "U1") (pin "67") (pinfunction "PD19_67") (pintype "input"))
    )
    (net (code "48") (name "LCD_D7") (class "Default")
      (node (ref "EXP1") (pin "8") (pinfunction "8_8") (pintype "unspecified"))
      (node (ref "U1") (pin "69") (pinfunction "PD18_69") (pintype "input"))
    )
    (net (code "49") (name "LCD_ENA") (class "Default")
      (node (ref "EXP1") (pin "3") (pinfunction "3_3") (pintype "unspecified"))
      (node (ref "U1") (pin "59") (pinfunction "PA25_59") (pintype "input"))
    )
    (net (code "50") (name "LCD_RS") (class "Default")
      (node (ref "EXP1") (pin "4") (pinfunction "4_4") (pintype "unspecified"))
      (node (ref "U1") (pin "76") (pinfunction "PC28_76") (pintype "input"))
    )
    (net (code "51") (name "LED") (class "Default")
      (node (ref "R6") (pin "2") (pinfunction "2_2") (pintype "unspecified"))
      (node (ref "U1") (pin "47") (pinfunction "PD27_47") (pintype "input"))
    )
    (net (code "52") (name "MCCDA") (class "Default")
      (node (ref "R50") (pin "2") (pintype "unspecified"))
      (node (ref "U1") (pin "112") (pinfunction "MCCDA_112") (pintype "input"))
    )
    (net (code "53") (name "MCCK") (class "Default")
      (node (ref "R68") (pin "2") (pintype "unspecified"))
      (node (ref "U1") (pin "129") (pinfunction "MCCK_129") (pintype "input"))
    )
    (net (code "54") (name "MCDA0") (class "Default")
      (node (ref "R77") (pin "2") (pintype "unspecified"))
      (node (ref "U1") (pin "116") (pinfunction "MCDA0_116") (pintype "input"))
    )
    (net (code "55") (name "MCDA1") (class "Default")
      (node (ref "R78") (pin "2") (pintype "unspecified"))
      (node (ref "U1") (pin "118") (pinfunction "MCDA1_118") (pintype "input"))
    )
    (net (code "56") (name "MCDA2") (class "Default")
      (node (ref "R48") (pin "2") (pintype "unspecified"))
      (node (ref "U1") (pin "62") (pinfunction "MCDA2_62") (pintype "input"))
    )
    (net (code "57") (name "MCDA3") (class "Default")
      (node (ref "R49") (pin "2") (pintype "unspecified"))
      (node (ref "U1") (pin "70") (pinfunction "MCDA3_70") (pintype "input"))
    )
    (net (code "58") (name "MISO") (class "Default")
      (node (ref "R101") (pin "2") (pintype "unspecified"))
      (node (ref "U1") (pin "68") (pinfunction "MISO_68") (pintype "input"))
    )
    (net (code "59") (name "MOSI") (class "Default")
      (node (ref "R105") (pin "2") (pintype "unspecified"))
      (node (ref "U1") (pin "42") (pinfunction "MOSI_42") (pintype "input"))
    )
    (net (code "60") (name "NPCS0") (class "Default")
      (node (ref "R99") (pin "2") (pintype "unspecified"))
      (node (ref "U1") (pin "64") (pinfunction "NPCS0_64") (pintype "input"))
      (node (ref "U29") (pin "1") (pinfunction "1CLR_1") (pintype "input"))
    )
    (net (code "61") (name "Net-(C17-Pad2)") (class "Default")
      (node (ref "C17") (pin "2") (pinfunction "2_2") (pintype "unspecified"))
      (node (ref "R35") (pin "1") (pinfunction "1_1") (pintype "unspecified"))
    )
    (net (code "62") (name "Net-(C29-Pad1)") (class "Default")
      (node (ref "C29") (pin "1") (pintype "unspecified"))
      (node (ref "J22") (pin "CE") (pinfunction "CE_CE") (pintype "bidirectional"))
    )
    (net (code "63") (name "Net-(C43-Pad2)") (class "Default")
      (node (ref "C43") (pin "2") (pinfunction "2_2") (pintype "input"))
      (node (ref "R56") (pin "2") (pintype "unspecified"))
    )
    (net (code "64") (name "Net-(D2-A)") (class "Default")
      (node (ref "D2") (pin "2") (pinfunction "A_2") (pintype "unspecified"))
      (node (ref "Q1") (pin "MB") (pinfunction "D_MB") (pintype "unspecified"))
      (node (ref "U3") (pin "2") (pinfunction "2_2") (pintype "unspecified"))
    )
    (net (code "65") (name "Net-(D3-A)") (class "Default")
      (node (ref "D3") (pin "2") (pinfunction "A_2") (pintype "unspecified"))
      (node (ref "Q2") (pin "MB") (pinfunction "D_MB") (pintype "unspecified"))
      (node (ref "U4") (pin "2") (pinfunction "2_2") (pintype "unspecified"))
    )
    (net (code "66") (name "Net-(D4-A)") (class "Default")
      (node (ref "D4") (pin "2") (pinfunction "A_2") (pintype "unspecified"))
      (node (ref "Q3") (pin "MB") (pinfunction "D_MB") (pintype "unspecified"))
      (node (ref "U5") (pin "2") (pinfunction "2_2") (pintype "unspecified"))
    )
    (net (code "67") (name "Net-(D4-C)") (class "Default")
      (node (ref "D4") (pin "1") (pinfunction "C_1") (pintype "unspecified"))
      (node (ref "H3") (pin "2") (pinfunction "2_2") (pintype "input"))
      (node (ref "U5") (pin "1") (pinfunction "1_1") (pintype "unspecified"))
    )
    (net (code "68") (name "Net-(D5-A)") (class "Default")
      (node (ref "D5") (pin "2") (pinfunction "A_2") (pintype "unspecified"))
      (node (ref "Q4") (pin "MB") (pinfunction "D_MB") (pintype "unspecified"))
      (node (ref "U7") (pin "2") (pinfunction "2_2") (pintype "unspecified"))
    )
    (net (code "69") (name "Net-(D6-A)") (class "Default")
      (node (ref "D6") (pin "2") (pinfunction "A_2") (pintype "unspecified"))
      (node (ref "P6") (pin "2") (pinfunction "2_2") (pintype "input"))
      (node (ref "Q5") (pin "MB") (pinfunction "D_MB") (pintype "unspecified"))
      (node (ref "U8") (pin "2") (pinfunction "2_2") (pintype "unspecified"))
    )
    (net (code "70") (name "Net-(D6-C)") (class "Default")
      (node (ref "D6") (pin "1") (pinfunction "C_1") (pintype "unspecified"))
      (node (ref "H1") (pin "2") (pinfunction "2_2") (pintype "input"))
      (node (ref "P6") (pin "1") (pinfunction "1_1") (pintype "input"))
      (node (ref "U8") (pin "1") (pinfunction "1_1") (pintype "unspecified"))
    )
    (net (code "71") (name "Net-(D7-A)") (class "Default")
      (node (ref "D7") (pin "2") (pinfunction "A_2") (pintype "unspecified"))
      (node (ref "P7") (pin "2") (pinfunction "2_2") (pintype "input"))
      (node (ref "Q6") (pin "MB") (pinfunction "D_MB") (pintype "unspecified"))
      (node (ref "U9") (pin "2") (pinfunction "2_2") (pintype "unspecified"))
    )
    (net (code "72") (name "Net-(D7-C)") (class "Default")
      (node (ref "D7") (pin "1") (pinfunction "C_1") (pintype "unspecified"))
      (node (ref "H2") (pin "2") (pinfunction "2_2") (pintype "input"))
      (node (ref "P7") (pin "1") (pinfunction "1_1") (pintype "input"))
      (node (ref "U9") (pin "1") (pinfunction "1_1") (pintype "unspecified"))
    )
    (net (code "73") (name "Net-(D12-C)") (class "Default")
      (node (ref "C11") (pin "1") (pinfunction "1_1") (pintype "unspecified"))
      (node (ref "D12") (pin "1") (pinfunction "C_1") (pintype "unspecified"))
      (node (ref "L1") (pin "1") (pinfunction "1_1") (pintype "unspecified"))
      (node (ref "U16") (pin "6") (pinfunction "LX_6") (pintype "unspecified"))
    )
    (net (code "74") (name "Net-(D14-A)") (class "Default")
      (node (ref "D14") (pin "2") (pinfunction "A_2") (pintype "unspecified"))
      (node (ref "F3") (pin "1") (pinfunction "1_1") (pintype "unspecified"))
    )
    (net (code "75") (name "Net-(D15-K)") (class "Default")
      (node (ref "C19") (pin "1") (pinfunction "1_1") (pintype "unspecified"))
      (node (ref "D15") (pin "1") (pinfunction "K_1") (pintype "unspecified"))
      (node (ref "L2") (pin "1") (pinfunction "1_1") (pintype "bidirectional"))
      (node (ref "U18") (pin "1") (pinfunction "LX_1") (pintype "unspecified"))
    )
    (net (code "76") (name "Net-(D17-K)") (class "Default")
      (node (ref "D17") (pin "2") (pinfunction "K_2") (pintype "unspecified"))
      (node (ref "R60") (pin "1") (pintype "unspecified"))
    )
    (net (code "77") (name "Net-(D25-K)") (class "Default")
      (node (ref "C35") (pin "2") (pinfunction "2_2") (pintype "unspecified"))
      (node (ref "D25") (pin "1") (pinfunction "K_1") (pintype "unspecified"))
      (node (ref "S1") (pin "3") (pintype "bidirectional"))
      (node (ref "S1") (pin "4") (pintype "bidirectional"))
    )
    (net (code "78") (name "Net-(F1-Pad1)") (class "Default")
      (node (ref "F1") (pin "1") (pintype "unspecified"))
      (node (ref "U10") (pin "2") (pinfunction "2_2") (pintype "unspecified"))
    )
    (net (code "79") (name "Net-(F2-Pad1)") (class "Default")
      (node (ref "F2") (pin "1") (pintype "unspecified"))
      (node (ref "U15") (pin "2") (pinfunction "2_2") (pintype "unspecified"))
    )
    (net (code "80") (name "Net-(J15-CLK)") (class "Default")
      (node (ref "J15") (pin "5") (pinfunction "CLK_5") (pintype "input"))
      (node (ref "R68") (pin "1") (pintype "unspecified"))
    )
    (net (code "81") (name "Net-(J15-CMD)") (class "Default")
      (node (ref "J15") (pin "3") (pinfunction "CMD_3") (pintype "input"))
      (node (ref "R50") (pin "1") (pintype "unspecified"))
      (node (ref "R63") (pin "1") (pintype "unspecified"))
    )
    (net (code "82") (name "Net-(J15-Card_Detect)") (class "Default")
      (node (ref "J15") (pin "9") (pinfunction "Card_Detect_9") (pintype "unspecified"))
      (node (ref "R64") (pin "1") (pintype "unspecified"))
      (node (ref "R79") (pin "1") (pintype "unspecified"))
    )
    (net (code "83") (name "Net-(J15-DAT0{slash}DO)") (class "Default")
      (node (ref "J15") (pin "7") (pinfunction "DAT0/DO_7") (pintype "bidirectional"))
      (node (ref "R75") (pin "1") (pintype "unspecified"))
      (node (ref "R77") (pin "1") (pintype "unspecified"))
    )
    (net (code "84") (name "Net-(J15-DAT1)") (class "Default")
      (node (ref "J15") (pin "8") (pinfunction "DAT1_8") (pintype "bidirectional"))
      (node (ref "R76") (pin "1") (pintype "unspecified"))
      (node (ref "R78") (pin "1") (pintype "unspecified"))
    )
    (net (code "85") (name "Net-(J15-DAT2)") (class "Default")
      (node (ref "J15") (pin "1") (pinfunction "DAT2_1") (pintype "bidirectional"))
      (node (ref "R48") (pin "1") (pintype "unspecified"))
      (node (ref "R73") (pin "1") (pintype "unspecified"))
    )
    (net (code "86") (name "Net-(J15-DAT3)") (class "Default")
      (node (ref "J15") (pin "2") (pinfunction "DAT3_2") (pintype "bidirectional"))
      (node (ref "R49") (pin "1") (pintype "unspecified"))
      (node (ref "R74") (pin "1") (pintype "unspecified"))
    )
    (net (code "87") (name "Net-(J22-DN)") (class "Default")
      (node (ref "J22") (pin "2") (pinfunction "DN_2") (pintype "bidirectional"))
      (node (ref "R55") (pin "1") (pintype "unspecified"))
    )
    (net (code "88") (name "Net-(J22-DP)") (class "Default")
      (node (ref "J22") (pin "3") (pinfunction "DP_3") (pintype "bidirectional"))
      (node (ref "R54") (pin "1") (pintype "unspecified"))
    )
    (net (code "89") (name "Net-(L6-B)") (class "Default")
      (node (ref "C42") (pin "2") (pinfunction "2_2") (pintype "input"))
      (node (ref "L6") (pin "2") (pinfunction "B_2") (pintype "unspecified"))
      (node (ref "R56") (pin "1") (pintype "unspecified"))
      (node (ref "U1") (pin "139") (pinfunction "VDDPLL_139") (pintype "input"))
    )
    (net (code "90") (name "Net-(L7-B)") (class "Default")
      (node (ref "L7") (pin "2") (pinfunction "B_2") (pintype "unspecified"))
      (node (ref "U30") (pin "8") (pinfunction "VCC_8") (pintype "bidirectional"))
    )
    (net (code "91") (name "Net-(LED1--)") (class "Default")
      (node (ref "LED1") (pin "2") (pinfunction "-_2") (pintype "unspecified"))
      (node (ref "R1") (pin "2") (pinfunction "2_2") (pintype "unspecified"))
    )
    (net (code "92") (name "Net-(LED2-+)") (class "Default")
      (node (ref "LED2") (pin "1") (pinfunction "+_1") (pintype "unspecified"))
      (node (ref "R2") (pin "1") (pinfunction "1_1") (pintype "unspecified"))
    )
    (net (code "93") (name "Net-(LED3-+)") (class "Default")
      (node (ref "LED3") (pin "1") (pinfunction "+_1") (pintype "unspecified"))
      (node (ref "R3") (pin "1") (pinfunction "1_1") (pintype "unspecified"))
    )
    (net (code "94") (name "Net-(LED4--)") (class "Default")
      (node (ref "LED4") (pin "2") (pinfunction "-_2") (pintype "unspecified"))
      (node (ref "R4") (pin "2") (pinfunction "2_2") (pintype "unspecified"))
    )
    (net (code "95") (name "Net-(LED5--)") (class "Default")
      (node (ref "LED5") (pin "2") (pinfunction "-_2") (pintype "unspecified"))
      (node (ref "R5") (pin "2") (pinfunction "2_2") (pintype "unspecified"))
    )
    (net (code "96") (name "Net-(LED6-+)") (class "Default")
      (node (ref "LED6") (pin "1") (pinfunction "+_1") (pintype "unspecified"))
      (node (ref "R6") (pin "1") (pinfunction "1_1") (pintype "unspecified"))
    )
    (net (code "97") (name "Net-(LED7-+)") (class "Default")
      (node (ref "LED7") (pin "1") (pinfunction "+_1") (pintype "unspecified"))
      (node (ref "R14") (pin "1") (pinfunction "1_1") (pintype "unspecified"))
    )
    (net (code "98") (name "Net-(LED8-+)") (class "Default")
      (node (ref "LED8") (pin "1") (pinfunction "+_1") (pintype "unspecified"))
      (node (ref "R19") (pin "1") (pinfunction "1_1") (pintype "unspecified"))
    )
    (net (code "99") (name "Net-(LED9-+)") (class "Default")
      (node (ref "LED9") (pin "1") (pinfunction "+_1") (pintype "unspecified"))
      (node (ref "R22") (pin "1") (pinfunction "1_1") (pintype "unspecified"))
    )
    (net (code "100") (name "Net-(LED10-+)") (class "Default")
      (node (ref "LED10") (pin "1") (pinfunction "+_1") (pintype "unspecified"))
      (node (ref "R25") (pin "2") (pinfunction "2_2") (pintype "unspecified"))
    )
    (net (code "101") (name "Net-(LED11-+)") (class "Default")
      (node (ref "LED11") (pin "1") (pinfunction "+_1") (pintype "unspecified"))
      (node (ref "R26") (pin "1") (pinfunction "1_1") (pintype "unspecified"))
    )
    (net (code "102") (name "Net-(LED12-+)") (class "Default")
      (node (ref "LED12") (pin "1") (pinfunction "+_1") (pintype "unspecified"))
      (node (ref "R31") (pin "1") (pinfunction "1_1") (pintype "unspecified"))
    )
    (net (code "103") (name "Net-(Q1-G)") (class "Default")
      (node (ref "Q1") (pin "4") (pinfunction "G_4") (pintype "unspecified"))
      (node (ref "R15") (pin "1") (pinfunction "1_1") (pintype "unspecified"))
    )
    (net (code "104") (name "Net-(Q2-G)") (class "Default")
      (node (ref "Q2") (pin "4") (pinfunction "G_4") (pintype "unspecified"))
      (node (ref "R18") (pin "1") (pinfunction "1_1") (pintype "unspecified"))
    )
    (net (code "105") (name "Net-(Q3-G)") (class "Default")
      (node (ref "Q3") (pin "4") (pinfunction "G_4") (pintype "unspecified"))
      (node (ref "R21") (pin "1") (pinfunction "1_1") (pintype "unspecified"))
    )
    (net (code "106") (name "Net-(Q4-G)") (class "Default")
      (node (ref "Q4") (pin "4") (pinfunction "G_4") (pintype "unspecified"))
      (node (ref "U6") (pin "5") (pinfunction "VCC_5") (pintype "unspecified"))
    )
    (net (code "107") (name "Net-(Q5-G)") (class "Default")
      (node (ref "Q5") (pin "4") (pinfunction "G_4") (pintype "unspecified"))
      (node (ref "R27") (pin "1") (pinfunction "1_1") (pintype "unspecified"))
    )
    (net (code "108") (name "Net-(Q6-G)") (class "Default")
      (node (ref "Q6") (pin "4") (pinfunction "G_4") (pintype "unspecified"))
      (node (ref "R30") (pin "1") (pinfunction "1_1") (pintype "unspecified"))
    )
    (net (code "109") (name "Net-(U1-TWCK0)") (class "Default")
      (node (ref "R10") (pin "2") (pinfunction "2_2") (pintype "unspecified"))
      (node (ref "U1") (pin "77") (pinfunction "TWCK0_77") (pintype "input"))
    )
    (net (code "110") (name "Net-(U1-TWD0)") (class "Default")
      (node (ref "R9") (pin "2") (pinfunction "2_2") (pintype "unspecified"))
      (node (ref "U1") (pin "91") (pinfunction "TWD0_91") (pintype "input"))
    )
    (net (code "111") (name "Net-(U1-XIN)") (class "Default")
      (node (ref "C44") (pin "1") (pintype "unspecified"))
      (node (ref "U1") (pin "142") (pinfunction "XIN_142") (pintype "input"))
      (node (ref "X2") (pin "3") (pinfunction "3_3") (pintype "unspecified"))
    )
    (net (code "112") (name "Net-(U1-XOUT)") (class "Default")
      (node (ref "C45") (pin "1") (pintype "unspecified"))
      (node (ref "U1") (pin "141") (pinfunction "XOUT_141") (pintype "input"))
      (node (ref "X2") (pin "1") (pinfunction "1_1") (pintype "unspecified"))
    )
    (net (code "113") (name "Net-(U6-A)") (class "Default")
      (node (ref "R23") (pin "1") (pinfunction "1_1") (pintype "unspecified"))
      (node (ref "U6") (pin "2") (pinfunction "A_2") (pintype "unspecified"))
    )
    (net (code "114") (name "Net-(U16-BST)") (class "Default")
      (node (ref "C11") (pin "2") (pinfunction "2_2") (pintype "unspecified"))
      (node (ref "U16") (pin "1") (pinfunction "BST_1") (pintype "unspecified"))
    )
    (net (code "115") (name "Net-(U18-BST)") (class "Default")
      (node (ref "C19") (pin "2") (pinfunction "2_2") (pintype "unspecified"))
      (node (ref "U18") (pin "2") (pinfunction "BST_2") (pintype "unspecified"))
    )
    (net (code "116") (name "Net-(U18-COMP)") (class "Default")
      (node (ref "R35") (pin "2") (pinfunction "2_2") (pintype "unspecified"))
      (node (ref "U18") (pin "5") (pinfunction "COMP_5") (pintype "unspecified"))
    )
    (net (code "117") (name "Net-(U18-FSW)") (class "Default")
      (node (ref "R34") (pin "2") (pinfunction "2_2") (pintype "unspecified"))
      (node (ref "U18") (pin "4") (pinfunction "FSW_4") (pintype "unspecified"))
    )
    (net (code "118") (name "Net-(U18-SS)") (class "Default")
      (node (ref "C16") (pin "2") (pinfunction "2_2") (pintype "unspecified"))
      (node (ref "U18") (pin "7") (pinfunction "SS_7") (pintype "unspecified"))
    )
    (net (code "119") (name "Net-(U23-1A)") (class "Default")
      (node (ref "U23") (pin "12") (pinfunction "1A_12") (pintype "unspecified"))
      (node (ref "X_MOT_A") (pin "3") (pinfunction "3_3") (pintype "unspecified"))
    )
    (net (code "120") (name "Net-(U23-1B)") (class "Default")
      (node (ref "U23") (pin "11") (pinfunction "1B_11") (pintype "unspecified"))
      (node (ref "X_MOT_A") (pin "4") (pinfunction "4_4") (pintype "unspecified"))
    )
    (net (code "121") (name "Net-(U23-2A)") (class "Default")
      (node (ref "U23") (pin "13") (pinfunction "2A_13") (pintype "unspecified"))
      (node (ref "X_MOT_A") (pin "2") (pinfunction "2_2") (pintype "unspecified"))
    )
    (net (code "122") (name "Net-(U23-2B)") (class "Default")
      (node (ref "U23") (pin "14") (pinfunction "2B_14") (pintype "unspecified"))
      (node (ref "X_MOT_A") (pin "1") (pinfunction "1_1") (pintype "unspecified"))
    )
    (net (code "123") (name "Net-(U23-MS1)") (class "Default")
      (node (ref "H5") (pin "2") (pinfunction "2_2") (pintype "input"))
      (node (ref "R13") (pin "2") (pinfunction "2_2") (pintype "unspecified"))
      (node (ref "U23") (pin "2") (pinfunction "MS1_2") (pintype "unspecified"))
    )
    (net (code "124") (name "Net-(U23-MS2)") (class "Default")
      (node (ref "H6") (pin "2") (pinfunction "2_2") (pintype "input"))
      (node (ref "U23") (pin "3") (pinfunction "MS2_3") (pintype "unspecified"))
    )
    (net (code "125") (name "Net-(U23-MS3)") (class "Default")
      (node (ref "H7") (pin "2") (pinfunction "2_2") (pintype "input"))
      (node (ref "U23") (pin "4") (pinfunction "MS3_4") (pintype "unspecified"))
    )
    (net (code "126") (name "Net-(U23-RST)") (class "Default")
      (node (ref "H8") (pin "2") (pinfunction "2_2") (pintype "input"))
      (node (ref "U23") (pin "5") (pinfunction "RST_5") (pintype "unspecified"))
    )
    (net (code "127") (name "Net-(U24-1A)") (class "Default")
      (node (ref "U24") (pin "12") (pinfunction "1A_12") (pintype "unspecified"))
      (node (ref "Y_MOT_A") (pin "3") (pinfunction "3_3") (pintype "unspecified"))
    )
    (net (code "128") (name "Net-(U24-1B)") (class "Default")
      (node (ref "U24") (pin "11") (pinfunction "1B_11") (pintype "unspecified"))
      (node (ref "Y_MOT_A") (pin "4") (pinfunction "4_4") (pintype "unspecified"))
    )
    (net (code "129") (name "Net-(U24-2A)") (class "Default")
      (node (ref "U24") (pin "13") (pinfunction "2A_13") (pintype "unspecified"))
      (node (ref "Y_MOT_A") (pin "2") (pinfunction "2_2") (pintype "unspecified"))
    )
    (net (code "130") (name "Net-(U24-2B)") (class "Default")
      (node (ref "U24") (pin "14") (pinfunction "2B_14") (pintype "unspecified"))
      (node (ref "Y_MOT_A") (pin "1") (pinfunction "1_1") (pintype "unspecified"))
    )
    (net (code "131") (name "Net-(U24-MS1)") (class "Default")
      (node (ref "H12") (pin "2") (pinfunction "2_2") (pintype "input"))
      (node (ref "R51") (pin "2") (pinfunction "2_2") (pintype "unspecified"))
      (node (ref "U24") (pin "2") (pinfunction "MS1_2") (pintype "unspecified"))
    )
    (net (code "132") (name "Net-(U24-MS2)") (class "Default")
      (node (ref "H11") (pin "2") (pinfunction "2_2") (pintype "input"))
      (node (ref "U24") (pin "3") (pinfunction "MS2_3") (pintype "unspecified"))
    )
    (net (code "133") (name "Net-(U24-MS3)") (class "Default")
      (node (ref "H10") (pin "2") (pinfunction "2_2") (pintype "input"))
      (node (ref "U24") (pin "4") (pinfunction "MS3_4") (pintype "unspecified"))
    )
    (net (code "134") (name "Net-(U24-RST)") (class "Default")
      (node (ref "H9") (pin "2") (pinfunction "2_2") (pintype "input"))
      (node (ref "U24") (pin "5") (pinfunction "RST_5") (pintype "unspecified"))
    )
    (net (code "135") (name "Net-(U25-1A)") (class "Default")
      (node (ref "U25") (pin "12") (pinfunction "1A_12") (pintype "unspecified"))
      (node (ref "Z_MOT_A") (pin "3") (pinfunction "3_3") (pintype "unspecified"))
    )
    (net (code "136") (name "Net-(U25-1B)") (class "Default")
      (node (ref "U25") (pin "11") (pinfunction "1B_11") (pintype "unspecified"))
      (node (ref "Z_MOT_A") (pin "4") (pinfunction "4_4") (pintype "unspecified"))
    )
    (net (code "137") (name "Net-(U25-2A)") (class "Default")
      (node (ref "U25") (pin "13") (pinfunction "2A_13") (pintype "unspecified"))
      (node (ref "Z_MOT_A") (pin "2") (pinfunction "2_2") (pintype "unspecified"))
    )
    (net (code "138") (name "Net-(U25-2B)") (class "Default")
      (node (ref "U25") (pin "14") (pinfunction "2B_14") (pintype "unspecified"))
      (node (ref "Z_MOT_A") (pin "1") (pinfunction "1_1") (pintype "unspecified"))
    )
    (net (code "139") (name "Net-(U25-MS1)") (class "Default")
      (node (ref "H13") (pin "2") (pinfunction "2_2") (pintype "input"))
      (node (ref "R72") (pin "2") (pinfunction "2_2") (pintype "unspecified"))
      (node (ref "U25") (pin "2") (pinfunction "MS1_2") (pintype "unspecified"))
    )
    (net (code "140") (name "Net-(U25-MS2)") (class "Default")
      (node (ref "H14") (pin "2") (pinfunction "2_2") (pintype "input"))
      (node (ref "U25") (pin "3") (pinfunction "MS2_3") (pintype "unspecified"))
    )
    (net (code "141") (name "Net-(U25-MS3)") (class "Default")
      (node (ref "H15") (pin "2") (pinfunction "2_2") (pintype "input"))
      (node (ref "U25") (pin "4") (pinfunction "MS3_4") (pintype "unspecified"))
    )
    (net (code "142") (name "Net-(U25-RST)") (class "Default")
      (node (ref "H16") (pin "2") (pinfunction "2_2") (pintype "input"))
      (node (ref "U25") (pin "5") (pinfunction "RST_5") (pintype "unspecified"))
    )
    (net (code "143") (name "Net-(U26-1A)") (class "Default")
      (node (ref "E0_MOT_A") (pin "3") (pinfunction "3_3") (pintype "unspecified"))
      (node (ref "U26") (pin "12") (pinfunction "1A_12") (pintype "unspecified"))
    )
    (net (code "144") (name "Net-(U26-1B)") (class "Default")
      (node (ref "E0_MOT_A") (pin "4") (pinfunction "4_4") (pintype "unspecified"))
      (node (ref "U26") (pin "11") (pinfunction "1B_11") (pintype "unspecified"))
    )
    (net (code "145") (name "Net-(U26-2A)") (class "Default")
      (node (ref "E0_MOT_A") (pin "2") (pinfunction "2_2") (pintype "unspecified"))
      (node (ref "U26") (pin "13") (pinfunction "2A_13") (pintype "unspecified"))
    )
    (net (code "146") (name "Net-(U26-2B)") (class "Default")
      (node (ref "E0_MOT_A") (pin "1") (pinfunction "1_1") (pintype "unspecified"))
      (node (ref "U26") (pin "14") (pinfunction "2B_14") (pintype "unspecified"))
    )
    (net (code "147") (name "Net-(U26-MS1)") (class "Default")
      (node (ref "H17") (pin "2") (pinfunction "2_2") (pintype "input"))
      (node (ref "R80") (pin "2") (pinfunction "2_2") (pintype "unspecified"))
      (node (ref "U26") (pin "2") (pinfunction "MS1_2") (pintype "unspecified"))
    )
    (net (code "148") (name "Net-(U26-MS2)") (class "Default")
      (node (ref "H18") (pin "2") (pinfunction "2_2") (pintype "input"))
      (node (ref "U26") (pin "3") (pinfunction "MS2_3") (pintype "unspecified"))
    )
    (net (code "149") (name "Net-(U26-MS3)") (class "Default")
      (node (ref "H19") (pin "2") (pinfunction "2_2") (pintype "input"))
      (node (ref "U26") (pin "4") (pinfunction "MS3_4") (pintype "unspecified"))
    )
    (net (code "150") (name "Net-(U26-RST)") (class "Default")
      (node (ref "H20") (pin "2") (pinfunction "2_2") (pintype "input"))
      (node (ref "U26") (pin "5") (pinfunction "RST_5") (pintype "unspecified"))
    )
    (net (code "151") (name "Net-(U27-1A)") (class "Default")
      (node (ref "E1_MOT_A") (pin "3") (pinfunction "3_3") (pintype "unspecified"))
      (node (ref "U27") (pin "12") (pinfunction "1A_12") (pintype "unspecified"))
    )
    (net (code "152") (name "Net-(U27-1B)") (class "Default")
      (node (ref "E1_MOT_A") (pin "4") (pinfunction "4_4") (pintype "unspecified"))
      (node (ref "U27") (pin "11") (pinfunction "1B_11") (pintype "unspecified"))
    )
    (net (code "153") (name "Net-(U27-2A)") (class "Default")
      (node (ref "E1_MOT_A") (pin "2") (pinfunction "2_2") (pintype "unspecified"))
      (node (ref "U27") (pin "13") (pinfunction "2A_13") (pintype "unspecified"))
    )
    (net (code "154") (name "Net-(U27-2B)") (class "Default")
      (node (ref "E1_MOT_A") (pin "1") (pinfunction "1_1") (pintype "unspecified"))
      (node (ref "U27") (pin "14") (pinfunction "2B_14") (pintype "unspecified"))
    )
    (net (code "155") (name "Net-(U27-MS1)") (class "Default")
      (node (ref "H21") (pin "2") (pinfunction "2_2") (pintype "input"))
      (node (ref "R81") (pin "2") (pinfunction "2_2") (pintype "unspecified"))
      (node (ref "U27") (pin "2") (pinfunction "MS1_2") (pintype "unspecified"))
    )
    (net (code "156") (name "Net-(U27-MS2)") (class "Default")
      (node (ref "H22") (pin "2") (pinfunction "2_2") (pintype "input"))
      (node (ref "U27") (pin "3") (pinfunction "MS2_3") (pintype "unspecified"))
    )
    (net (code "157") (name "Net-(U27-MS3)") (class "Default")
      (node (ref "H23") (pin "2") (pinfunction "2_2") (pintype "input"))
      (node (ref "U27") (pin "4") (pinfunction "MS3_4") (pintype "unspecified"))
    )
    (net (code "158") (name "Net-(U27-RST)") (class "Default")
      (node (ref "H24") (pin "2") (pinfunction "2_2") (pintype "input"))
      (node (ref "U27") (pin "5") (pinfunction "RST_5") (pintype "unspecified"))
    )
    (net (code "159") (name "Net-(U28-1A)") (class "Default")
      (node (ref "E2_MOT_A") (pin "3") (pinfunction "3_3") (pintype "unspecified"))
      (node (ref "U28") (pin "12") (pinfunction "1A_12") (pintype "unspecified"))
    )
    (net (code "160") (name "Net-(U28-1B)") (class "Default")
      (node (ref "E2_MOT_A") (pin "4") (pinfunction "4_4") (pintype "unspecified"))
      (node (ref "U28") (pin "11") (pinfunction "1B_11") (pintype "unspecified"))
    )
    (net (code "161") (name "Net-(U28-2A)") (class "Default")
      (node (ref "E2_MOT_A") (pin "2") (pinfunction "2_2") (pintype "unspecified"))
      (node (ref "U28") (pin "13") (pinfunction "2A_13") (pintype "unspecified"))
    )
    (net (code "162") (name "Net-(U28-2B)") (class "Default")
      (node (ref "E2_MOT_A") (pin "1") (pinfunction "1_1") (pintype "unspecified"))
      (node (ref "U28") (pin "14") (pinfunction "2B_14") (pintype "unspecified"))
    )
    (net (code "163") (name "Net-(U28-MS1)") (class "Default")
      (node (ref "H25") (pin "2") (pinfunction "2_2") (pintype "input"))
      (node (ref "R84") (pin "2") (pinfunction "2_2") (pintype "unspecified"))
      (node (ref "U28") (pin "2") (pinfunction "MS1_2") (pintype "unspecified"))
    )
    (net (code "164") (name "Net-(U28-MS2)") (class "Default")
      (node (ref "H26") (pin "2") (pinfunction "2_2") (pintype "input"))
      (node (ref "U28") (pin "3") (pinfunction "MS2_3") (pintype "unspecified"))
    )
    (net (code "165") (name "Net-(U28-MS3)") (class "Default")
      (node (ref "H27") (pin "2") (pinfunction "2_2") (pintype "input"))
      (node (ref "U28") (pin "4") (pinfunction "MS3_4") (pintype "unspecified"))
    )
    (net (code "166") (name "Net-(U28-RST)") (class "Default")
      (node (ref "H28") (pin "2") (pinfunction "2_2") (pintype "input"))
      (node (ref "U28") (pin "5") (pinfunction "RST_5") (pintype "unspecified"))
    )
    (net (code "167") (name "Net-(U29-1D)") (class "Default")
      (node (ref "C28") (pin "1") (pintype "unspecified"))
      (node (ref "U29") (pin "10") (pinfunction "2PRE_10") (pintype "input"))
      (node (ref "U29") (pin "11") (pinfunction "2CLK_11") (pintype "input"))
      (node (ref "U29") (pin "12") (pinfunction "2D_12") (pintype "input"))
      (node (ref "U29") (pin "13") (pinfunction "2CLR_13") (pintype "input"))
      (node (ref "U29") (pin "2") (pinfunction "1D_2") (pintype "input"))
      (node (ref "U29") (pin "4") (pinfunction "1PRE_4") (pintype "input"))
    )
    (net (code "168") (name "Net-(U30-GPIO0)") (class "Default")
      (node (ref "R47") (pin "1") (pintype "unspecified"))
      (node (ref "U30") (pin "12") (pinfunction "GPIO0_12") (pintype "bidirectional"))
    )
    (net (code "169") (name "Net-(U30-GPIO4)") (class "Default")
      (node (ref "R82") (pin "2") (pintype "unspecified"))
      (node (ref "U29") (pin "5") (pinfunction "1Q_5") (pintype "output"))
      (node (ref "U30") (pin "13") (pinfunction "GPIO4_13") (pintype "input"))
    )
    (net (code "170") (name "Net-(U30-GPIO12)") (class "Default")
      (node (ref "R101") (pin "1") (pintype "unspecified"))
      (node (ref "U30") (pin "6") (pinfunction "GPIO12_6") (pintype "bidirectional"))
    )
    (net (code "171") (name "Net-(U30-GPIO13)") (class "Default")
      (node (ref "R105") (pin "1") (pintype "unspecified"))
      (node (ref "U30") (pin "7") (pinfunction "GPIO13_7") (pintype "bidirectional"))
    )
    (net (code "172") (name "Net-(U30-GPIO14)") (class "Default")
      (node (ref "R100") (pin "1") (pintype "unspecified"))
      (node (ref "U30") (pin "5") (pinfunction "GPIO14_5") (pintype "bidirectional"))
    )
    (net (code "173") (name "Net-(U30-GPIO15)") (class "Default")
      (node (ref "R99") (pin "1") (pintype "unspecified"))
      (node (ref "U30") (pin "10") (pinfunction "GPIO15_10") (pintype "bidirectional"))
    )
    (net (code "174") (name "Net-(U30-REST)") (class "Default")
      (node (ref "R44") (pin "1") (pintype "unspecified"))
      (node (ref "R53") (pin "1") (pintype "unspecified"))
      (node (ref "U30") (pin "1") (pinfunction "REST_1") (pintype "bidirectional"))
    )
    (net (code "175") (name "Net-(U30-RXD0)") (class "Default")
      (node (ref "C83") (pin "1") (pintype "unspecified"))
      (node (ref "R103") (pin "1") (pintype "unspecified"))
      (node (ref "U30") (pin "15") (pinfunction "RXD0_15") (pintype "input"))
    )
    (net (code "176") (name "Net-(U30-TXD0)") (class "Default")
      (node (ref "R102") (pin "1") (pintype "unspecified"))
      (node (ref "U30") (pin "16") (pinfunction "TXD0_16") (pintype "bidirectional"))
    )
    (net (code "177") (name "PB4{slash}TDI") (class "Default")
      (node (ref "J21") (pin "8") (pinfunction "TDI_8") (pintype "bidirectional"))
      (node (ref "R57") (pin "2") (pintype "unspecified"))
      (node (ref "U1") (pin "105") (pinfunction "PB4/TDI_105") (pintype "input"))
    )
    (net (code "178") (name "PB5{slash}TDO") (class "Default")
      (node (ref "J21") (pin "6") (pinfunction "TDO_6") (pintype "bidirectional"))
      (node (ref "U1") (pin "109") (pinfunction "PB5/TDO_109") (pintype "input"))
    )
    (net (code "179") (name "PB6{slash}TMS") (class "Default")
      (node (ref "J21") (pin "2") (pinfunction "TMS_2") (pintype "bidirectional"))
      (node (ref "R59") (pin "2") (pintype "unspecified"))
      (node (ref "U1") (pin "79") (pinfunction "PB6/TMS_79") (pintype "input"))
    )
    (net (code "180") (name "PB7{slash}TCK") (class "Default")
      (node (ref "J21") (pin "4") (pinfunction "TCK_4") (pintype "bidirectional"))
      (node (ref "R58") (pin "2") (pintype "unspecified"))
      (node (ref "R83") (pin "2") (pintype "unspecified"))
      (node (ref "U1") (pin "89") (pinfunction "PB7/TCK_89") (pintype "input"))
    )
    (net (code "181") (name "PD30") (class "Default")
      (node (ref "EXP3") (pin "1") (pinfunction "1_1") (pintype "unspecified"))
      (node (ref "U1") (pin "34") (pinfunction "PD30_34") (pintype "input"))
    )
    (net (code "182") (name "PS_ON") (class "Default")
      (node (ref "P8") (pin "1") (pinfunction "1_1") (pintype "input"))
      (node (ref "U1") (pin "132") (pinfunction "PD1_132") (pintype "input"))
    )
    (net (code "183") (name "PWM_1") (class "Default")
      (node (ref "EXP3") (pin "10") (pinfunction "10_10") (pintype "unspecified"))
    )
    (net (code "184") (name "PWM_2") (class "Default")
      (node (ref "EXP3") (pin "9") (pinfunction "9_9") (pintype "unspecified"))
    )
    (net (code "185") (name "RESET") (class "Default")
      (node (ref "D25") (pin "2") (pinfunction "A_2") (pintype "unspecified"))
      (node (ref "EXP2") (pin "8") (pinfunction "8_8") (pintype "unspecified"))
      (node (ref "J21") (pin "10") (pinfunction "*RST_10") (pintype "bidirectional"))
      (node (ref "R106") (pin "1") (pintype "unspecified"))
      (node (ref "U1") (pin "83") (pinfunction "NRST_83") (pintype "input"))
    )
    (net (code "186") (name "SAM_TFR_RDY") (class "Default")
      (node (ref "R82") (pin "1") (pintype "unspecified"))
      (node (ref "U1") (pin "60") (pinfunction "PD22_60") (pintype "input"))
      (node (ref "U29") (pin "3") (pinfunction "1CLK_3") (pintype "input"))
    )
    (net (code "187") (name "SCL") (class "Default")
      (node (ref "ENC_1") (pin "1") (pinfunction "1_1") (pintype "unspecified"))
      (node (ref "ENC_2") (pin "1") (pinfunction "1_1") (pintype "unspecified"))
      (node (ref "ENC_3") (pin "1") (pinfunction "1_1") (pintype "unspecified"))
      (node (ref "ENC_4") (pin "1") (pinfunction "1_1") (pintype "unspecified"))
      (node (ref "EXP3") (pin "6") (pinfunction "6_6") (pintype "unspecified"))
      (node (ref "R11") (pin "1") (pinfunction "1_1") (pintype "unspecified"))
      (node (ref "R9") (pin "1") (pinfunction "1_1") (pintype "unspecified"))
      (node (ref "U2") (pin "1") (pinfunction "SCL_1") (pintype "unspecified"))
    )
    (net (code "188") (name "SDA") (class "Default")
      (node (ref "ENC_1") (pin "2") (pinfunction "2_2") (pintype "unspecified"))
      (node (ref "ENC_2") (pin "2") (pinfunction "2_2") (pintype "unspecified"))
      (node (ref "ENC_3") (pin "2") (pinfunction "2_2") (pintype "unspecified"))
      (node (ref "ENC_4") (pin "2") (pinfunction "2_2") (pintype "unspecified"))
      (node (ref "EXP3") (pin "5") (pinfunction "5_5") (pintype "unspecified"))
      (node (ref "R10") (pin "1") (pinfunction "1_1") (pintype "unspecified"))
      (node (ref "R12") (pin "1") (pinfunction "1_1") (pintype "unspecified"))
      (node (ref "U2") (pin "3") (pinfunction "SDA_3") (pintype "unspecified"))
    )
    (net (code "189") (name "SD_CD") (class "Default")
      (node (ref "R79") (pin "2") (pintype "unspecified"))
      (node (ref "U1") (pin "122") (pinfunction "PC21_122") (pintype "input"))
    )
    (net (code "190") (name "SD_CSEL") (class "Default")
      (node (ref "EXP2") (pin "4") (pinfunction "4_4") (pintype "unspecified"))
    )
    (net (code "191") (name "SD_DET") (class "Default")
      (node (ref "EXP2") (pin "7") (pinfunction "7_7") (pintype "unspecified"))
    )
    (net (code "192") (name "SPCK") (class "Default")
      (node (ref "R100") (pin "2") (pintype "unspecified"))
      (node (ref "U1") (pin "51") (pinfunction "SPCK_51") (pintype "input"))
    )
    (net (code "193") (name "SPI0_CS0") (class "Default")
      (node (ref "U1") (pin "130") (pinfunction "PC24/TIOB3_130") (pintype "input"))
    )
    (net (code "194") (name "SPI0_CS1") (class "Default")
      (node (ref "U1") (pin "26") (pinfunction "CTS0_26") (pintype "input"))
    )
    (net (code "195") (name "SPI0_CS2") (class "Default")
      (node (ref "U1") (pin "111") (pinfunction "PC18_111") (pintype "input"))
    )
    (net (code "196") (name "SPI0_MISO") (class "Default")
      (node (ref "U1") (pin "21") (pinfunction "RXD0_21") (pintype "input"))
    )
    (net (code "197") (name "SPI0_MOSI") (class "Default")
      (node (ref "U1") (pin "20") (pinfunction "TXD0_20") (pintype "input"))
    )
    (net (code "198") (name "SPI0_SCK") (class "Default")
      (node (ref "U1") (pin "144") (pinfunction "SCK0/DAC0_144") (pintype "input"))
    )
    (net (code "199") (name "SPI1_MISO") (class "Default")
      (node (ref "EXP2") (pin "1") (pinfunction "1_1") (pintype "unspecified"))
      (node (ref "H16") (pin "1") (pinfunction "1_1") (pintype "input"))
      (node (ref "H20") (pin "1") (pinfunction "1_1") (pintype "input"))
      (node (ref "H24") (pin "1") (pinfunction "1_1") (pintype "input"))
      (node (ref "H28") (pin "1") (pinfunction "1_1") (pintype "input"))
      (node (ref "H8") (pin "1") (pinfunction "1_1") (pintype "input"))
      (node (ref "H9") (pin "1") (pinfunction "1_1") (pintype "input"))
      (node (ref "U1") (pin "32") (pinfunction "RXD1_32") (pintype "input"))
    )
    (net (code "200") (name "SPI1_MOSI") (class "Default")
      (node (ref "EXP2") (pin "6") (pinfunction "6_6") (pintype "unspecified"))
      (node (ref "H12") (pin "1") (pinfunction "1_1") (pintype "input"))
      (node (ref "H13") (pin "1") (pinfunction "1_1") (pintype "input"))
      (node (ref "H17") (pin "1") (pinfunction "1_1") (pintype "input"))
      (node (ref "H21") (pin "1") (pinfunction "1_1") (pintype "input"))
      (node (ref "H25") (pin "1") (pinfunction "1_1") (pintype "input"))
      (node (ref "H5") (pin "1") (pinfunction "1_1") (pintype "input"))
      (node (ref "U1") (pin "37") (pinfunction "TXD1_37") (pintype "input"))
    )
    (net (code "201") (name "SPI1_SCK") (class "Default")
      (node (ref "EXP2") (pin "2") (pinfunction "2_2") (pintype "unspecified"))
      (node (ref "H11") (pin "1") (pinfunction "1_1") (pintype "input"))
      (node (ref "H14") (pin "1") (pinfunction "1_1") (pintype "input"))
      (node (ref "H18") (pin "1") (pinfunction "1_1") (pintype "input"))
      (node (ref "H22") (pin "1") (pinfunction "1_1") (pintype "input"))
      (node (ref "H26") (pin "1") (pinfunction "1_1") (pintype "input"))
      (node (ref "H6") (pin "1") (pinfunction "1_1") (pintype "input"))
      (node (ref "U1") (pin "46") (pinfunction "SCK1_46") (pintype "input"))
    )
    (net (code "202") (name "THERM0") (class "Default")
      (node (ref "C54") (pin "1") (pintype "unspecified"))
      (node (ref "R67") (pin "2") (pintype "unspecified"))
      (node (ref "U1") (pin "15") (pinfunction "AFE0_AD10_15") (pintype "input"))
    )
    (net (code "203") (name "THERM1") (class "Default")
      (node (ref "C55") (pin "1") (pintype "unspecified"))
      (node (ref "R66") (pin "2") (pintype "unspecified"))
      (node (ref "U1") (pin "16") (pinfunction "AFE0_AD9_16") (pintype "input"))
    )
    (net (code "204") (name "THERM2") (class "Default")
      (node (ref "C56") (pin "1") (pintype "unspecified"))
      (node (ref "R65") (pin "2") (pintype "unspecified"))
      (node (ref "U1") (pin "17") (pinfunction "AFE0_AD8_17") (pintype "input"))
    )
    (net (code "205") (name "THERM3") (class "Default")
      (node (ref "C59") (pin "1") (pintype "unspecified"))
      (node (ref "R70") (pin "2") (pintype "unspecified"))
      (node (ref "U1") (pin "18") (pinfunction "AFE0_AD7_18") (pintype "input"))
    )
    (net (code "206") (name "THERM4") (class "Default")
      (node (ref "C60") (pin "1") (pintype "unspecified"))
      (node (ref "R71") (pin "2") (pintype "unspecified"))
      (node (ref "U1") (pin "19") (pinfunction "AFE0_AD6_19") (pintype "input"))
    )
    (net (code "207") (name "THERMIN0") (class "Default")
      (node (ref "P13") (pin "1") (pinfunction "1_1") (pintype "unspecified"))
      (node (ref "R67") (pin "1") (pintype "unspecified"))
      (node (ref "R8") (pin "1") (pintype "unspecified"))
    )
    (net (code "208") (name "THERMIN1") (class "Default")
      (node (ref "P9") (pin "1") (pinfunction "1_1") (pintype "unspecified"))
      (node (ref "R61") (pin "1") (pintype "unspecified"))
      (node (ref "R66") (pin "1") (pintype "unspecified"))
    )
    (net (code "209") (name "THERMIN2") (class "Default")
      (node (ref "P10") (pin "1") (pinfunction "1_1") (pintype "unspecified"))
      (node (ref "R62") (pin "1") (pintype "unspecified"))
      (node (ref "R65") (pin "1") (pintype "unspecified"))
    )
    (net (code "210") (name "THERMIN3") (class "Default")
      (node (ref "P11") (pin "1") (pinfunction "1_1") (pintype "unspecified"))
      (node (ref "R7") (pin "1") (pintype "unspecified"))
      (node (ref "R70") (pin "1") (pintype "unspecified"))
    )
    (net (code "211") (name "THERMIN4") (class "Default")
      (node (ref "P12") (pin "1") (pinfunction "1_1") (pintype "unspecified"))
      (node (ref "R69") (pin "1") (pintype "unspecified"))
      (node (ref "R71") (pin "1") (pintype "unspecified"))
    )
    (net (code "212") (name "URXD0") (class "Default")
      (node (ref "EXP3") (pin "3") (pinfunction "3_3") (pintype "unspecified"))
      (node (ref "U1") (pin "75") (pinfunction "URXD0_75") (pintype "input"))
    )
    (net (code "213") (name "URXD1") (class "Default")
      (node (ref "EXP3") (pin "8") (pinfunction "8_8") (pintype "unspecified"))
      (node (ref "R102") (pin "2") (pintype "unspecified"))
      (node (ref "U1") (pin "73") (pinfunction "URXD1_73") (pintype "input"))
    )
    (net (code "214") (name "USBVCC") (class "Default")
      (node (ref "F3") (pin "2") (pinfunction "2_2") (pintype "unspecified"))
      (node (ref "R3") (pin "2") (pinfunction "2_2") (pintype "unspecified"))
    )
    (net (code "215") (name "USB_PWR_MON") (class "Default")
      (node (ref "C82") (pin "1") (pintype "unspecified"))
      (node (ref "R45") (pin "1") (pintype "unspecified"))
      (node (ref "R46") (pin "2") (pintype "unspecified"))
      (node (ref "U1") (pin "54") (pinfunction "PC6_54") (pintype "input"))
    )
    (net (code "216") (name "UTXD0") (class "Default")
      (node (ref "EXP3") (pin "4") (pinfunction "4_4") (pintype "unspecified"))
      (node (ref "U1") (pin "66") (pinfunction "UTXD0_66") (pintype "input"))
    )
    (net (code "217") (name "UTXD1") (class "Default")
      (node (ref "EXP3") (pin "2") (pinfunction "2_2") (pintype "unspecified"))
      (node (ref "R103") (pin "2") (pintype "unspecified"))
      (node (ref "U1") (pin "114") (pinfunction "UTXD1_114") (pintype "input"))
    )
    (net (code "218") (name "VBUS") (class "Default")
      (node (ref "D17") (pin "1") (pinfunction "A_1") (pintype "unspecified"))
      (node (ref "J22") (pin "1") (pinfunction "VBUS_1") (pintype "bidirectional"))
      (node (ref "R46") (pin "1") (pintype "unspecified"))
    )
    (net (code "219") (name "VDDCORE") (class "Default")
      (node (ref "C30") (pin "2") (pinfunction "2_2") (pintype "unspecified"))
      (node (ref "C46") (pin "2") (pinfunction "2_2") (pintype "unspecified"))
      (node (ref "C47") (pin "2") (pinfunction "2_2") (pintype "unspecified"))
      (node (ref "C48") (pin "2") (pinfunction "2_2") (pintype "unspecified"))
      (node (ref "C49") (pin "2") (pinfunction "2_2") (pintype "unspecified"))
      (node (ref "C50") (pin "2") (pinfunction "2_2") (pintype "unspecified"))
      (node (ref "C51") (pin "2") (pinfunction "2_2") (pintype "unspecified"))
      (node (ref "C52") (pin "1") (pinfunction "1_1") (pintype "input"))
      (node (ref "C53") (pin "2") (pinfunction "2_2") (pintype "input"))
      (node (ref "L6") (pin "1") (pinfunction "A_1") (pintype "unspecified"))
      (node (ref "U1") (pin "107") (pinfunction "VDDCORE_107") (pintype "input"))
      (node (ref "U1") (pin "123") (pinfunction "VDDCORE_123") (pintype "input"))
      (node (ref "U1") (pin "29") (pinfunction "VDDCORE_29") (pintype "input"))
      (node (ref "U1") (pin "3") (pinfunction "VDDOUT_3") (pintype "input"))
      (node (ref "U1") (pin "33") (pinfunction "VDDCORE_33") (pintype "input"))
      (node (ref "U1") (pin "50") (pinfunction "VDDCORE_50") (pintype "input"))
      (node (ref "U1") (pin "81") (pinfunction "VDDCORE_81") (pintype "input"))
    )
    (net (code "220") (name "VIN1") (class "Default")
      (node (ref "C10") (pin "1") (pinfunction "1_1") (pintype "unspecified"))
      (node (ref "C18") (pin "1") (pinfunction "1_1") (pintype "unspecified"))
      (node (ref "C9") (pin "1") (pinfunction "1_1") (pintype "input"))
      (node (ref "D11") (pin "1") (pinfunction "C_1") (pintype "unspecified"))
      (node (ref "D2") (pin "1") (pinfunction "C_1") (pintype "unspecified"))
      (node (ref "D3") (pin "1") (pinfunction "C_1") (pintype "unspecified"))
      (node (ref "D9") (pin "2") (pinfunction "A_2") (pintype "unspecified"))
      (node (ref "F2") (pin "2") (pintype "unspecified"))
      (node (ref "H1") (pin "1") (pinfunction "1_1") (pintype "input"))
      (node (ref "H2") (pin "1") (pinfunction "1_1") (pintype "input"))
      (node (ref "H3") (pin "1") (pinfunction "1_1") (pintype "input"))
      (node (ref "P1") (pin "2") (pinfunction "2_2") (pintype "input"))
      (node (ref "U16") (pin "4") (pinfunction "EN_4") (pintype "unspecified"))
      (node (ref "U16") (pin "5") (pinfunction "VIN_5") (pintype "unspecified"))
      (node (ref "U18") (pin "9") (pinfunction "VIN_9") (pintype "unspecified"))
      (node (ref "U3") (pin "1") (pinfunction "1_1") (pintype "unspecified"))
      (node (ref "U4") (pin "1") (pinfunction "1_1") (pintype "unspecified"))
    )
    (net (code "221") (name "VIN2") (class "Default")
      (node (ref "D5") (pin "1") (pinfunction "C_1") (pintype "unspecified"))
      (node (ref "D8") (pin "1") (pinfunction "C_1") (pintype "unspecified"))
      (node (ref "F1") (pin "2") (pintype "unspecified"))
      (node (ref "U7") (pin "1") (pinfunction "1_1") (pintype "unspecified"))
    )
    (net (code "222") (name "VMOT") (class "Default")
      (node (ref "C22") (pin "1") (pinfunction "1_1") (pintype "input"))
      (node (ref "C23") (pin "1") (pinfunction "1_1") (pintype "input"))
      (node (ref "C24") (pin "1") (pinfunction "1_1") (pintype "input"))
      (node (ref "C25") (pin "1") (pinfunction "1_1") (pintype "input"))
      (node (ref "C26") (pin "1") (pinfunction "1_1") (pintype "input"))
      (node (ref "C27") (pin "1") (pinfunction "1_1") (pintype "input"))
      (node (ref "D10") (pin "1") (pinfunction "K_1") (pintype "unspecified"))
      (node (ref "D9") (pin "1") (pinfunction "K_1") (pintype "unspecified"))
      (node (ref "U23") (pin "16") (pinfunction "VMOT_16") (pintype "unspecified"))
      (node (ref "U24") (pin "16") (pinfunction "VMOT_16") (pintype "unspecified"))
      (node (ref "U25") (pin "16") (pinfunction "VMOT_16") (pintype "unspecified"))
      (node (ref "U26") (pin "16") (pinfunction "VMOT_16") (pintype "unspecified"))
      (node (ref "U27") (pin "16") (pinfunction "VMOT_16") (pintype "unspecified"))
      (node (ref "U28") (pin "16") (pinfunction "VMOT_16") (pintype "unspecified"))
    )
    (net (code "223") (name "VSSA") (class "Default")
      (node (ref "F4") (pin "1") (pinfunction "1_1") (pintype "unspecified"))
      (node (ref "R83") (pin "1") (pintype "unspecified"))
    )
    (net (code "224") (name "X-CS") (class "Default")
      (node (ref "H7") (pin "1") (pinfunction "1_1") (pintype "input"))
      (node (ref "U1") (pin "78") (pinfunction "PD16_78") (pintype "input"))
    )
    (net (code "225") (name "X-DIR") (class "Default")
      (node (ref "U1") (pin "98") (pinfunction "PD11_98") (pintype "input"))
      (node (ref "U23") (pin "8") (pinfunction "DIR_8") (pintype "unspecified"))
    )
    (net (code "226") (name "X-EN") (class "Default")
      (node (ref "R38") (pin "1") (pinfunction "1_1") (pintype "unspecified"))
      (node (ref "U1") (pin "84") (pinfunction "PD14_84") (pintype "input"))
      (node (ref "U23") (pin "1") (pinfunction "EN_1") (pintype "unspecified"))
    )
    (net (code "227") (name "X-MAX") (class "Default")
      (node (ref "U1") (pin "101") (pinfunction "PD10_101") (pintype "input"))
      (node (ref "X+") (pin "1") (pinfunction "1_1") (pintype "unspecified"))
    )
    (net (code "228") (name "X-MIN") (class "Default")
      (node (ref "U1") (pin "97") (pinfunction "PC14_97") (pintype "input"))
      (node (ref "X-") (pin "1") (pinfunction "1_1") (pintype "unspecified"))
    )
    (net (code "229") (name "X-SLP") (class "Default")
      (node (ref "H8") (pin "3") (pinfunction "3_3") (pintype "input"))
      (node (ref "U23") (pin "6") (pinfunction "SLP_6") (pintype "unspecified"))
    )
    (net (code "230") (name "X-STEP") (class "Default")
      (node (ref "U1") (pin "121") (pinfunction "PD6_121") (pintype "input"))
      (node (ref "U23") (pin "7") (pinfunction "STEP_7") (pintype "unspecified"))
    )
    (net (code "231") (name "Y-CS") (class "Default")
      (node (ref "H10") (pin "1") (pinfunction "1_1") (pintype "input"))
      (node (ref "U1") (pin "128") (pinfunction "PD3_128") (pintype "input"))
    )
    (net (code "232") (name "Y-DIR") (class "Default")
      (node (ref "U1") (pin "92") (pinfunction "PD12_92") (pintype "input"))
      (node (ref "U24") (pin "8") (pinfunction "DIR_8") (pintype "unspecified"))
    )
    (net (code "233") (name "Y-EN") (class "Default")
      (node (ref "R39") (pin "1") (pinfunction "1_1") (pintype "unspecified"))
      (node (ref "U1") (pin "86") (pinfunction "PC9_86") (pintype "input"))
      (node (ref "U24") (pin "1") (pinfunction "EN_1") (pintype "unspecified"))
    )
    (net (code "234") (name "Y-MAX") (class "Default")
      (node (ref "U1") (pin "100") (pinfunction "PC16_100") (pintype "input"))
      (node (ref "Y+") (pin "1") (pinfunction "1_1") (pintype "unspecified"))
    )
    (net (code "235") (name "Y-MIN") (class "Default")
      (node (ref "U1") (pin "93") (pinfunction "PA2_93") (pintype "input"))
      (node (ref "Y-") (pin "1") (pinfunction "1_1") (pintype "unspecified"))
    )
    (net (code "236") (name "Y-SLP") (class "Default")
      (node (ref "H9") (pin "3") (pinfunction "3_3") (pintype "input"))
      (node (ref "U24") (pin "6") (pinfunction "SLP_6") (pintype "unspecified"))
    )
    (net (code "237") (name "Y-STEP") (class "Default")
      (node (ref "U1") (pin "119") (pinfunction "PD7_119") (pintype "input"))
      (node (ref "U24") (pin "7") (pinfunction "STEP_7") (pintype "unspecified"))
    )
    (net (code "238") (name "Z-CS") (class "Default")
      (node (ref "H15") (pin "1") (pinfunction "1_1") (pintype "input"))
      (node (ref "U1") (pin "106") (pinfunction "PD15_106") (pintype "input"))
    )
    (net (code "239") (name "Z-DIR") (class "Default")
      (node (ref "U1") (pin "88") (pinfunction "PD13_88") (pintype "input"))
      (node (ref "U25") (pin "8") (pinfunction "DIR_8") (pintype "unspecified"))
    )
    (net (code "240") (name "Z-EN") (class "Default")
      (node (ref "R40") (pin "1") (pinfunction "1_1") (pintype "unspecified"))
      (node (ref "U1") (pin "90") (pinfunction "PC10_90") (pintype "input"))
      (node (ref "U25") (pin "1") (pinfunction "EN_1") (pintype "unspecified"))
    )
    (net (code "241") (name "Z-MAX") (class "Default")
      (node (ref "U1") (pin "4") (pinfunction "PE0_4") (pintype "input"))
      (node (ref "Z+") (pin "1") (pinfunction "1_1") (pintype "unspecified"))
    )
    (net (code "242") (name "Z-MIN") (class "Default")
      (node (ref "U1") (pin "108") (pinfunction "PD29_108") (pintype "input"))
      (node (ref "Z-") (pin "1") (pinfunction "1_1") (pintype "unspecified"))
    )
    (net (code "243") (name "Z-SLP") (class "Default")
      (node (ref "H16") (pin "3") (pinfunction "3_3") (pintype "input"))
      (node (ref "U25") (pin "6") (pinfunction "SLP_6") (pintype "unspecified"))
    )
    (net (code "244") (name "Z-STEP") (class "Default")
      (node (ref "U1") (pin "113") (pinfunction "PD8_113") (pintype "input"))
      (node (ref "U25") (pin "7") (pinfunction "STEP_7") (pintype "unspecified"))
    )
    (net (code "245") (name "unconnected-(J21-NC{slash}RTCK-Pad7)") (class "Default")
      (node (ref "J21") (pin "7") (pinfunction "NC/RTCK_7") (pintype "unspecified+no_connect"))
    )
    (net (code "246") (name "unconnected-(J22-ID-Pad4)") (class "Default")
      (node (ref "J22") (pin "4") (pinfunction "ID_4") (pintype "bidirectional+no_connect"))
    )
    (net (code "247") (name "unconnected-(U1-AFE0_AD1-Pad24)") (class "Default")
      (node (ref "U1") (pin "24") (pinfunction "AFE0_AD1_24") (pintype "input"))
    )
    (net (code "248") (name "unconnected-(U1-AFE0_AD11-Pad14)") (class "Default")
      (node (ref "U1") (pin "14") (pinfunction "AFE0_AD11_14") (pintype "input"))
    )
    (net (code "249") (name "unconnected-(U1-AFE0_AD13-Pad12)") (class "Default")
      (node (ref "U1") (pin "12") (pinfunction "AFE0_AD13_12") (pintype "input"))
    )
    (net (code "250") (name "unconnected-(U1-AFE0_AD14-Pad11)") (class "Default")
      (node (ref "U1") (pin "11") (pinfunction "AFE0_AD14_11") (pintype "input"))
    )
    (net (code "251") (name "unconnected-(U1-AFE1_AD4-Pad38)") (class "Default")
      (node (ref "U1") (pin "38") (pinfunction "AFE1_AD4_38") (pintype "input"))
    )
    (net (code "252") (name "unconnected-(U1-DAC1-Pad140)") (class "Default")
      (node (ref "U1") (pin "140") (pinfunction "DAC1_140") (pintype "input"))
    )
    (net (code "253") (name "unconnected-(U1-PA7{slash}XIN32-Pad35)") (class "Default")
      (node (ref "U1") (pin "35") (pinfunction "PA7/XIN32_35") (pintype "input"))
    )
    (net (code "254") (name "unconnected-(U1-PA8{slash}XOUT32-Pad36)") (class "Default")
      (node (ref "U1") (pin "36") (pinfunction "PA8/XOUT32_36") (pintype "input"))
    )
    (net (code "255") (name "unconnected-(U1-PA17{slash}AFE0_AD0-Pad25)") (class "Default")
      (node (ref "U1") (pin "25") (pinfunction "PA17/AFE0_AD0_25") (pintype "input"))
    )
    (net (code "256") (name "unconnected-(U1-PB3{slash}AFE1_AD1-Pad31)") (class "Default")
      (node (ref "U1") (pin "31") (pinfunction "PB3/AFE1_AD1_31") (pintype "input"))
    )
    (net (code "257") (name "unconnected-(U1-PC2-Pad39)") (class "Default")
      (node (ref "U1") (pin "39") (pinfunction "PC2_39") (pintype "input"))
    )
    (net (code "258") (name "unconnected-(U1-PC4{slash}AFE1_AD7-Pad41)") (class "Default")
      (node (ref "U1") (pin "41") (pinfunction "PC4/AFE1_AD7_41") (pintype "input"))
    )
    (net (code "259") (name "unconnected-(U1-PD0-Pad1)") (class "Default")
      (node (ref "U1") (pin "1") (pinfunction "PD0_1") (pintype "input"))
    )
    (net (code "260") (name "unconnected-(U1-PD17-Pad74)") (class "Default")
      (node (ref "U1") (pin "74") (pinfunction "PD17_74") (pintype "input"))
    )
    (net (code "261") (name "unconnected-(U1-PE1-Pad6)") (class "Default")
      (node (ref "U1") (pin "6") (pinfunction "PE1_6") (pintype "input"))
    )
    (net (code "262") (name "unconnected-(U1-PE2-Pad7)") (class "Default")
      (node (ref "U1") (pin "7") (pinfunction "PE2_7") (pintype "input"))
    )
    (net (code "263") (name "unconnected-(U1-PE3-Pad10)") (class "Default")
      (node (ref "U1") (pin "10") (pinfunction "PE3_10") (pintype "input"))
    )
    (net (code "264") (name "unconnected-(U1-RTS1-Pad56)") (class "Default")
      (node (ref "U1") (pin "56") (pinfunction "RTS1_56") (pintype "input"))
    )
    (net (code "265") (name "unconnected-(U1-TIOA0-Pad102)") (class "Default")
      (node (ref "U1") (pin "102") (pinfunction "TIOA0_102") (pintype "input"))
    )
    (net (code "266") (name "unconnected-(U1-TIOA4-Pad13)") (class "Default")
      (node (ref "U1") (pin "13") (pinfunction "TIOA4_13") (pintype "input"))
    )
    (net (code "267") (name "unconnected-(U1-TIOA4-Pad127)") (class "Default")
      (node (ref "U1") (pin "127") (pinfunction "TIOA4_127") (pintype "input"))
    )
    (net (code "268") (name "unconnected-(U1-TIOA7-Pad82)") (class "Default")
      (node (ref "U1") (pin "82") (pinfunction "TIOA7_82") (pintype "input"))
    )
    (net (code "269") (name "unconnected-(U1-TIOA8-Pad94)") (class "Default")
      (node (ref "U1") (pin "94") (pinfunction "TIOA8_94") (pintype "input"))
    )
    (net (code "270") (name "unconnected-(U6-Y-Pad4)") (class "Default")
      (node (ref "U6") (pin "4") (pinfunction "Y_4") (pintype "unspecified"))
    )
    (net (code "271") (name "unconnected-(U17-NC-Pad4)") (class "Default")
      (node (ref "U17") (pin "4") (pinfunction "NC_4") (pintype "unspecified+no_connect"))
    )
    (net (code "272") (name "unconnected-(U29-1Q-Pad6)") (class "Default")
      (node (ref "U29") (pin "6") (pinfunction "1Q_6") (pintype "output+no_connect"))
    )
    (net (code "273") (name "unconnected-(U29-2Q-Pad8)") (class "Default")
      (node (ref "U29") (pin "8") (pinfunction "2Q_8") (pintype "output+no_connect"))
    )
    (net (code "274") (name "unconnected-(U29-2Q-Pad9)") (class "Default")
      (node (ref "U29") (pin "9") (pinfunction "2Q_9") (pintype "output+no_connect"))
    )
    (net (code "275") (name "unconnected-(U30-ADC-Pad2)") (class "Default")
      (node (ref "U30") (pin "2") (pinfunction "ADC_2") (pintype "unspecified"))
    )
    (net (code "276") (name "unconnected-(U30-GPIO2-Pad11)") (class "Default")
      (node (ref "U30") (pin "11") (pinfunction "GPIO2_11") (pintype "bidirectional"))
    )
    (net (code "277") (name "unconnected-(U30-GPIO5-Pad14)") (class "Default")
      (node (ref "U30") (pin "14") (pinfunction "GPIO5_14") (pintype "bidirectional"))
    )
    (net (code "278") (name "unconnected-(U30-GPIO16-Pad4)") (class "Default")
      (node (ref "U30") (pin "4") (pinfunction "GPIO16_4") (pintype "unspecified"))
    )
  )
)
